# SMPS.net
KiCad netlist of a schematic drawn in Altium Designer
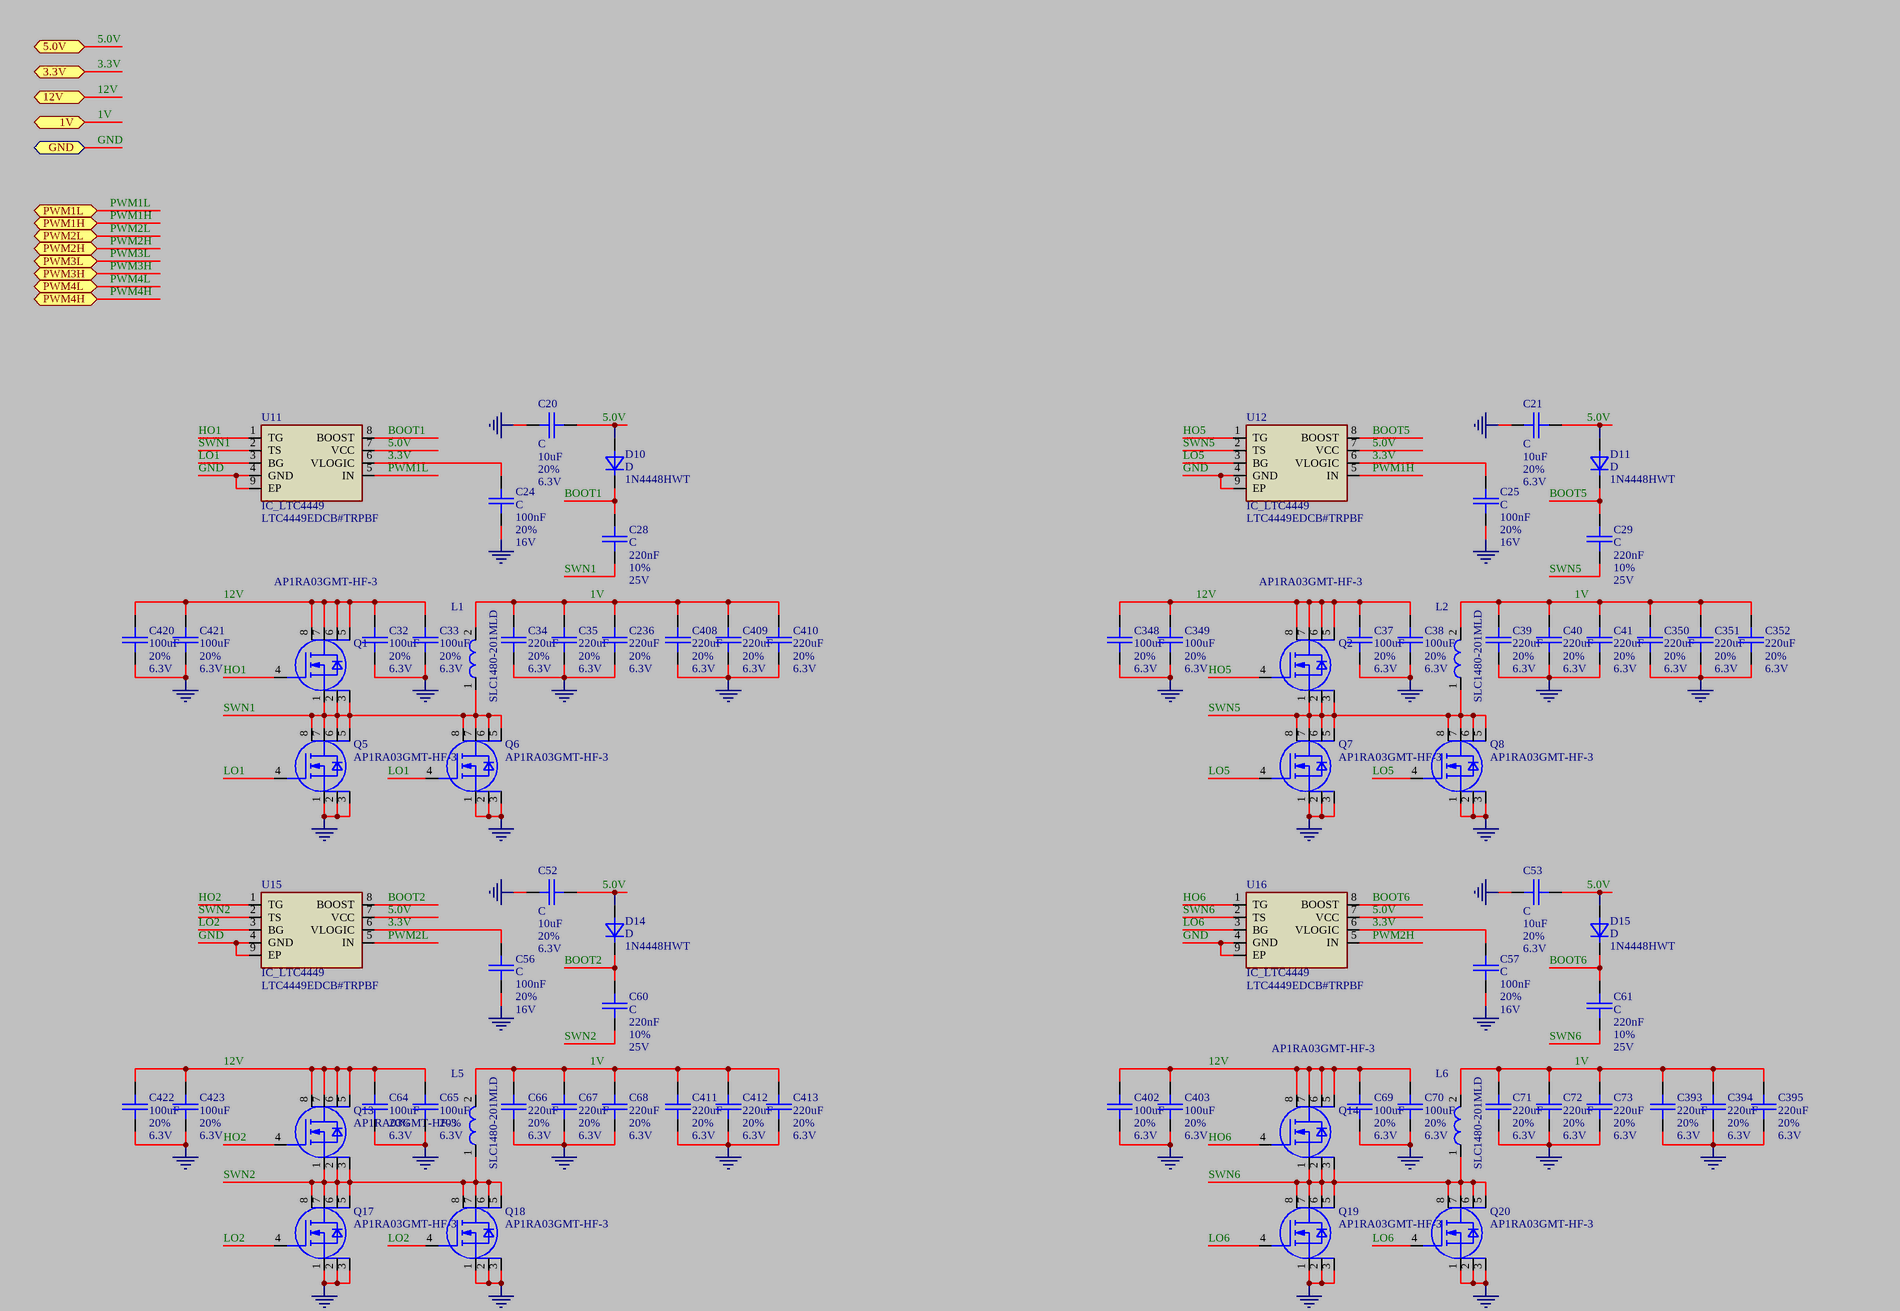
[diagram p0: SMPS.SchDoc, top left]
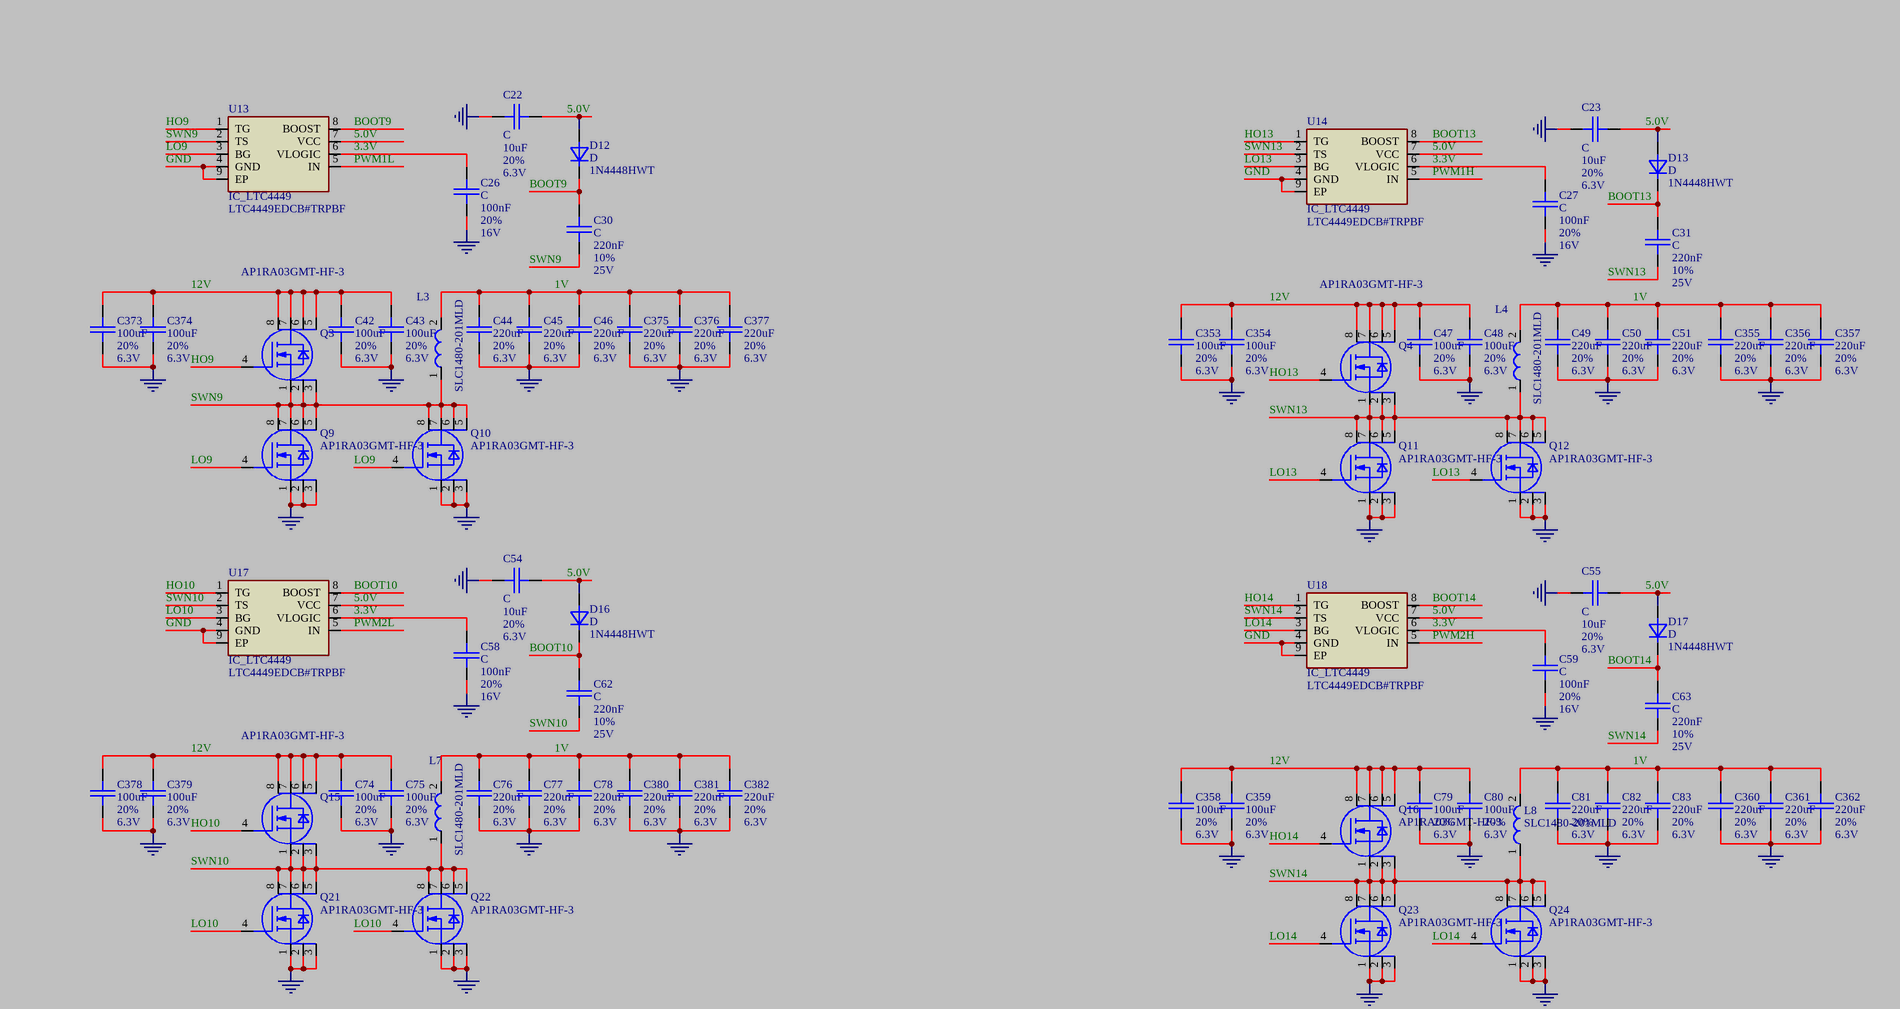
[diagram p1: SMPS.SchDoc, top right]
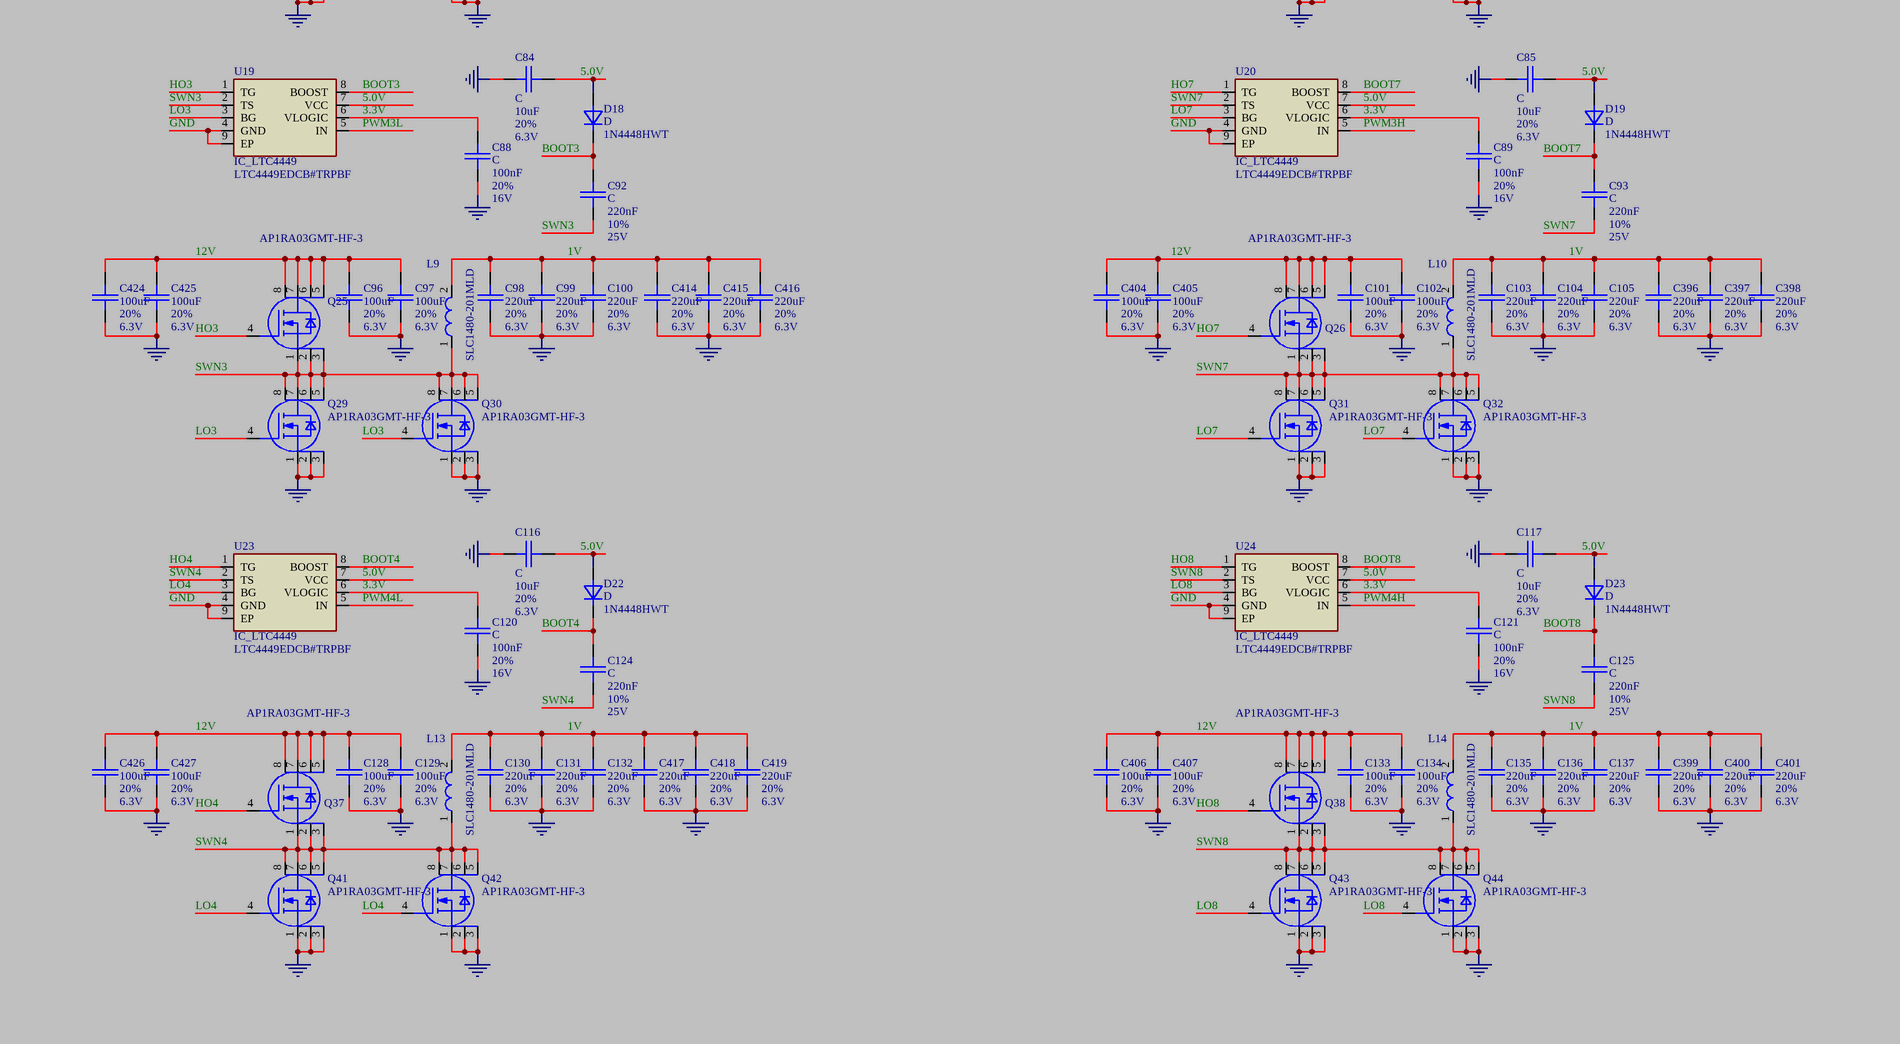
[diagram p2: SMPS.SchDoc, bottom left]
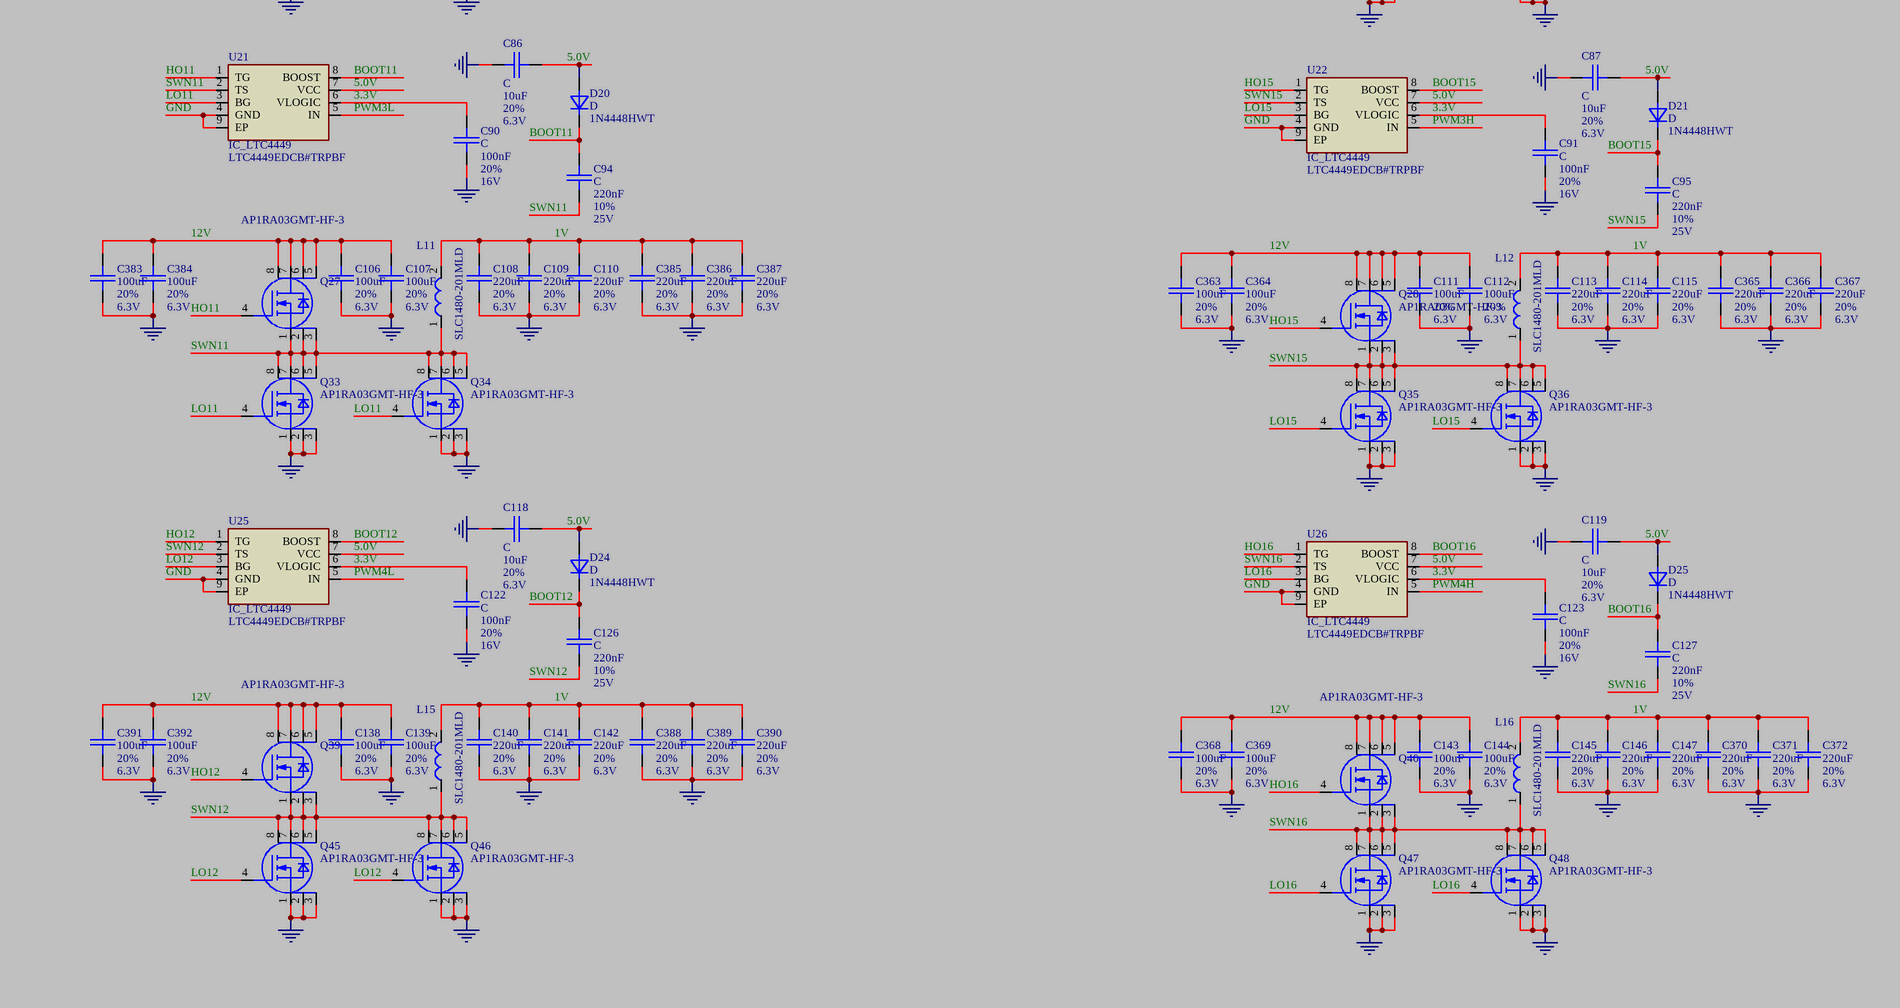
[diagram p3: SMPS.SchDoc, bottom right]

(export (version "E")
  (design (tool "Eeschema 10.0.6"))
  (components
    (comp (ref "C20")
      (value "C")
      (footprint "SMD_0603_CAPC1608X95N")
      (fields
        (field (name "DB_PART_NUMBER") "CAP000043646")
        (field (name "DB_VALUE") "10uF")
        (field (name "DB_TOLERANCE") "20%")
        (field (name "DB_VOLTAGE") "6.3V")
        (field (name "DB_MANUFACTURER_PART") "KEMET    C0603C106M9PAC")
      )
      (libsource (lib "Database_Libs1") (part "C"))
    )
    (comp (ref "C21")
      (value "C")
      (footprint "SMD_0603_CAPC1608X95N")
      (fields
        (field (name "DB_PART_NUMBER") "CAP000043646")
        (field (name "DB_VALUE") "10uF")
        (field (name "DB_TOLERANCE") "20%")
        (field (name "DB_VOLTAGE") "6.3V")
        (field (name "DB_MANUFACTURER_PART") "KEMET    C0603C106M9PAC")
      )
      (libsource (lib "Database_Libs1") (part "C"))
    )
    (comp (ref "C22")
      (value "C")
      (footprint "SMD_0603_CAPC1608X95N")
      (fields
        (field (name "DB_PART_NUMBER") "CAP000043646")
        (field (name "DB_VALUE") "10uF")
        (field (name "DB_TOLERANCE") "20%")
        (field (name "DB_VOLTAGE") "6.3V")
        (field (name "DB_MANUFACTURER_PART") "KEMET    C0603C106M9PAC")
      )
      (libsource (lib "Database_Libs1") (part "C"))
    )
    (comp (ref "C23")
      (value "C")
      (footprint "SMD_0603_CAPC1608X95N")
      (fields
        (field (name "DB_PART_NUMBER") "CAP000043646")
        (field (name "DB_VALUE") "10uF")
        (field (name "DB_TOLERANCE") "20%")
        (field (name "DB_VOLTAGE") "6.3V")
        (field (name "DB_MANUFACTURER_PART") "KEMET    C0603C106M9PAC")
      )
      (libsource (lib "Database_Libs1") (part "C"))
    )
    (comp (ref "C24")
      (value "C")
      (footprint "SMD_0402_CAPC1005X55N")
      (fields
        (field (name "DB_PART_NUMBER") "CAP000022751")
        (field (name "DB_VALUE") "100nF")
        (field (name "DB_TOLERANCE") "20%")
        (field (name "DB_VOLTAGE") "16V")
        (field (name "DB_MANUFACTURER_PART") "KEMET    C0402F104M4RAC")
      )
      (libsource (lib "Database_Libs1") (part "C"))
    )
    (comp (ref "C25")
      (value "C")
      (footprint "SMD_0402_CAPC1005X55N")
      (fields
        (field (name "DB_PART_NUMBER") "CAP000022751")
        (field (name "DB_VALUE") "100nF")
        (field (name "DB_TOLERANCE") "20%")
        (field (name "DB_VOLTAGE") "16V")
        (field (name "DB_MANUFACTURER_PART") "KEMET    C0402F104M4RAC")
      )
      (libsource (lib "Database_Libs1") (part "C"))
    )
    (comp (ref "C26")
      (value "C")
      (footprint "SMD_0402_CAPC1005X55N")
      (fields
        (field (name "DB_PART_NUMBER") "CAP000022751")
        (field (name "DB_VALUE") "100nF")
        (field (name "DB_TOLERANCE") "20%")
        (field (name "DB_VOLTAGE") "16V")
        (field (name "DB_MANUFACTURER_PART") "KEMET    C0402F104M4RAC")
      )
      (libsource (lib "Database_Libs1") (part "C"))
    )
    (comp (ref "C27")
      (value "C")
      (footprint "SMD_0402_CAPC1005X55N")
      (fields
        (field (name "DB_PART_NUMBER") "CAP000022751")
        (field (name "DB_VALUE") "100nF")
        (field (name "DB_TOLERANCE") "20%")
        (field (name "DB_VOLTAGE") "16V")
        (field (name "DB_MANUFACTURER_PART") "KEMET    C0402F104M4RAC")
      )
      (libsource (lib "Database_Libs1") (part "C"))
    )
    (comp (ref "C28")
      (value "C")
      (footprint "SMD_0603_CAPC1608X95N")
      (fields
        (field (name "DB_PART_NUMBER") "CAP000022968")
        (field (name "DB_VALUE") "220nF")
        (field (name "DB_TOLERANCE") "10%")
        (field (name "DB_VOLTAGE") "25V")
        (field (name "DB_MANUFACTURER_PART") "KEMET    C0603F224K3RAC")
      )
      (libsource (lib "Database_Libs1") (part "C"))
    )
    (comp (ref "C29")
      (value "C")
      (footprint "SMD_0603_CAPC1608X95N")
      (fields
        (field (name "DB_PART_NUMBER") "CAP000022968")
        (field (name "DB_VALUE") "220nF")
        (field (name "DB_TOLERANCE") "10%")
        (field (name "DB_VOLTAGE") "25V")
        (field (name "DB_MANUFACTURER_PART") "KEMET    C0603F224K3RAC")
      )
      (libsource (lib "Database_Libs1") (part "C"))
    )
    (comp (ref "C30")
      (value "C")
      (footprint "SMD_0603_CAPC1608X95N")
      (fields
        (field (name "DB_PART_NUMBER") "CAP000022968")
        (field (name "DB_VALUE") "220nF")
        (field (name "DB_TOLERANCE") "10%")
        (field (name "DB_VOLTAGE") "25V")
        (field (name "DB_MANUFACTURER_PART") "KEMET    C0603F224K3RAC")
      )
      (libsource (lib "Database_Libs1") (part "C"))
    )
    (comp (ref "C31")
      (value "C")
      (footprint "SMD_0603_CAPC1608X95N")
      (fields
        (field (name "DB_PART_NUMBER") "CAP000022968")
        (field (name "DB_VALUE") "220nF")
        (field (name "DB_TOLERANCE") "10%")
        (field (name "DB_VOLTAGE") "25V")
        (field (name "DB_MANUFACTURER_PART") "KEMET    C0603F224K3RAC")
      )
      (libsource (lib "Database_Libs1") (part "C"))
    )
    (comp (ref "C32")
      (value "C")
      (footprint "SMD_1210_CAPC3225X270N")
      (fields
        (field (name "DB_PART_NUMBER") "CAP000043701")
        (field (name "DB_VALUE") "100uF")
        (field (name "DB_TOLERANCE") "20%")
        (field (name "DB_VOLTAGE") "6.3V")
        (field (name "DB_MANUFACTURER_PART") "KEMET    C1210C107M9PAC")
      )
      (libsource (lib "Database_Libs1") (part "C"))
    )
    (comp (ref "C33")
      (value "C")
      (footprint "SMD_1210_CAPC3225X270N")
      (fields
        (field (name "DB_PART_NUMBER") "CAP000043701")
        (field (name "DB_VALUE") "100uF")
        (field (name "DB_TOLERANCE") "20%")
        (field (name "DB_VOLTAGE") "6.3V")
        (field (name "DB_MANUFACTURER_PART") "KEMET    C1210C107M9PAC")
      )
      (libsource (lib "Database_Libs1") (part "C"))
    )
    (comp (ref "C34")
      (value "C")
      (footprint "SMD_1210_CAPC3225X279N")
      (fields
        (field (name "DB_PART_NUMBER") "CAP000047355")
        (field (name "DB_VALUE") "220uF")
        (field (name "DB_TOLERANCE") "20%")
        (field (name "DB_VOLTAGE") "6.3V")
        (field (name "DB_MANUFACTURER_PART") "SAMSUNG    CL32A227MQVNNNE")
        (field (name "DB_APPROVED_BY") "VSN")
      )
      (libsource (lib "Database_Libs1") (part "C"))
    )
    (comp (ref "C35")
      (value "C")
      (footprint "SMD_1210_CAPC3225X279N")
      (fields
        (field (name "DB_PART_NUMBER") "CAP000047355")
        (field (name "DB_VALUE") "220uF")
        (field (name "DB_TOLERANCE") "20%")
        (field (name "DB_VOLTAGE") "6.3V")
        (field (name "DB_MANUFACTURER_PART") "SAMSUNG    CL32A227MQVNNNE")
        (field (name "DB_APPROVED_BY") "VSN")
      )
      (libsource (lib "Database_Libs1") (part "C"))
    )
    (comp (ref "C37")
      (value "C")
      (footprint "SMD_1210_CAPC3225X270N")
      (fields
        (field (name "DB_PART_NUMBER") "CAP000043701")
        (field (name "DB_VALUE") "100uF")
        (field (name "DB_TOLERANCE") "20%")
        (field (name "DB_VOLTAGE") "6.3V")
        (field (name "DB_MANUFACTURER_PART") "KEMET    C1210C107M9PAC")
      )
      (libsource (lib "Database_Libs1") (part "C"))
    )
    (comp (ref "C38")
      (value "C")
      (footprint "SMD_1210_CAPC3225X270N")
      (fields
        (field (name "DB_PART_NUMBER") "CAP000043701")
        (field (name "DB_VALUE") "100uF")
        (field (name "DB_TOLERANCE") "20%")
        (field (name "DB_VOLTAGE") "6.3V")
        (field (name "DB_MANUFACTURER_PART") "KEMET    C1210C107M9PAC")
      )
      (libsource (lib "Database_Libs1") (part "C"))
    )
    (comp (ref "C39")
      (value "C")
      (footprint "SMD_1210_CAPC3225X279N")
      (fields
        (field (name "DB_PART_NUMBER") "CAP000047355")
        (field (name "DB_VALUE") "220uF")
        (field (name "DB_TOLERANCE") "20%")
        (field (name "DB_VOLTAGE") "6.3V")
        (field (name "DB_MANUFACTURER_PART") "SAMSUNG    CL32A227MQVNNNE")
        (field (name "DB_APPROVED_BY") "VSN")
      )
      (libsource (lib "Database_Libs1") (part "C"))
    )
    (comp (ref "C40")
      (value "C")
      (footprint "SMD_1210_CAPC3225X279N")
      (fields
        (field (name "DB_PART_NUMBER") "CAP000047355")
        (field (name "DB_VALUE") "220uF")
        (field (name "DB_TOLERANCE") "20%")
        (field (name "DB_VOLTAGE") "6.3V")
        (field (name "DB_MANUFACTURER_PART") "SAMSUNG    CL32A227MQVNNNE")
        (field (name "DB_APPROVED_BY") "VSN")
      )
      (libsource (lib "Database_Libs1") (part "C"))
    )
    (comp (ref "C41")
      (value "C")
      (footprint "SMD_1210_CAPC3225X279N")
      (fields
        (field (name "DB_PART_NUMBER") "CAP000047355")
        (field (name "DB_VALUE") "220uF")
        (field (name "DB_TOLERANCE") "20%")
        (field (name "DB_VOLTAGE") "6.3V")
        (field (name "DB_MANUFACTURER_PART") "SAMSUNG    CL32A227MQVNNNE")
        (field (name "DB_APPROVED_BY") "VSN")
      )
      (libsource (lib "Database_Libs1") (part "C"))
    )
    (comp (ref "C42")
      (value "C")
      (footprint "SMD_1210_CAPC3225X270N")
      (fields
        (field (name "DB_PART_NUMBER") "CAP000043701")
        (field (name "DB_VALUE") "100uF")
        (field (name "DB_TOLERANCE") "20%")
        (field (name "DB_VOLTAGE") "6.3V")
        (field (name "DB_MANUFACTURER_PART") "KEMET    C1210C107M9PAC")
      )
      (libsource (lib "Database_Libs1") (part "C"))
    )
    (comp (ref "C43")
      (value "C")
      (footprint "SMD_1210_CAPC3225X270N")
      (fields
        (field (name "DB_PART_NUMBER") "CAP000043701")
        (field (name "DB_VALUE") "100uF")
        (field (name "DB_TOLERANCE") "20%")
        (field (name "DB_VOLTAGE") "6.3V")
        (field (name "DB_MANUFACTURER_PART") "KEMET    C1210C107M9PAC")
      )
      (libsource (lib "Database_Libs1") (part "C"))
    )
    (comp (ref "C44")
      (value "C")
      (footprint "SMD_1210_CAPC3225X279N")
      (fields
        (field (name "DB_PART_NUMBER") "CAP000047355")
        (field (name "DB_VALUE") "220uF")
        (field (name "DB_TOLERANCE") "20%")
        (field (name "DB_VOLTAGE") "6.3V")
        (field (name "DB_MANUFACTURER_PART") "SAMSUNG    CL32A227MQVNNNE")
        (field (name "DB_APPROVED_BY") "VSN")
      )
      (libsource (lib "Database_Libs1") (part "C"))
    )
    (comp (ref "C45")
      (value "C")
      (footprint "SMD_1210_CAPC3225X279N")
      (fields
        (field (name "DB_PART_NUMBER") "CAP000047355")
        (field (name "DB_VALUE") "220uF")
        (field (name "DB_TOLERANCE") "20%")
        (field (name "DB_VOLTAGE") "6.3V")
        (field (name "DB_MANUFACTURER_PART") "SAMSUNG    CL32A227MQVNNNE")
        (field (name "DB_APPROVED_BY") "VSN")
      )
      (libsource (lib "Database_Libs1") (part "C"))
    )
    (comp (ref "C46")
      (value "C")
      (footprint "SMD_1210_CAPC3225X279N")
      (fields
        (field (name "DB_PART_NUMBER") "CAP000047355")
        (field (name "DB_VALUE") "220uF")
        (field (name "DB_TOLERANCE") "20%")
        (field (name "DB_VOLTAGE") "6.3V")
        (field (name "DB_MANUFACTURER_PART") "SAMSUNG    CL32A227MQVNNNE")
        (field (name "DB_APPROVED_BY") "VSN")
      )
      (libsource (lib "Database_Libs1") (part "C"))
    )
    (comp (ref "C47")
      (value "C")
      (footprint "SMD_1210_CAPC3225X270N")
      (fields
        (field (name "DB_PART_NUMBER") "CAP000043701")
        (field (name "DB_VALUE") "100uF")
        (field (name "DB_TOLERANCE") "20%")
        (field (name "DB_VOLTAGE") "6.3V")
        (field (name "DB_MANUFACTURER_PART") "KEMET    C1210C107M9PAC")
      )
      (libsource (lib "Database_Libs1") (part "C"))
    )
    (comp (ref "C48")
      (value "C")
      (footprint "SMD_1210_CAPC3225X270N")
      (fields
        (field (name "DB_PART_NUMBER") "CAP000043701")
        (field (name "DB_VALUE") "100uF")
        (field (name "DB_TOLERANCE") "20%")
        (field (name "DB_VOLTAGE") "6.3V")
        (field (name "DB_MANUFACTURER_PART") "KEMET    C1210C107M9PAC")
      )
      (libsource (lib "Database_Libs1") (part "C"))
    )
    (comp (ref "C49")
      (value "C")
      (footprint "SMD_1210_CAPC3225X279N")
      (fields
        (field (name "DB_PART_NUMBER") "CAP000047355")
        (field (name "DB_VALUE") "220uF")
        (field (name "DB_TOLERANCE") "20%")
        (field (name "DB_VOLTAGE") "6.3V")
        (field (name "DB_MANUFACTURER_PART") "SAMSUNG    CL32A227MQVNNNE")
        (field (name "DB_APPROVED_BY") "VSN")
      )
      (libsource (lib "Database_Libs1") (part "C"))
    )
    (comp (ref "C50")
      (value "C")
      (footprint "SMD_1210_CAPC3225X279N")
      (fields
        (field (name "DB_PART_NUMBER") "CAP000047355")
        (field (name "DB_VALUE") "220uF")
        (field (name "DB_TOLERANCE") "20%")
        (field (name "DB_VOLTAGE") "6.3V")
        (field (name "DB_MANUFACTURER_PART") "SAMSUNG    CL32A227MQVNNNE")
        (field (name "DB_APPROVED_BY") "VSN")
      )
      (libsource (lib "Database_Libs1") (part "C"))
    )
    (comp (ref "C51")
      (value "C")
      (footprint "SMD_1210_CAPC3225X279N")
      (fields
        (field (name "DB_PART_NUMBER") "CAP000047355")
        (field (name "DB_VALUE") "220uF")
        (field (name "DB_TOLERANCE") "20%")
        (field (name "DB_VOLTAGE") "6.3V")
        (field (name "DB_MANUFACTURER_PART") "SAMSUNG    CL32A227MQVNNNE")
        (field (name "DB_APPROVED_BY") "VSN")
      )
      (libsource (lib "Database_Libs1") (part "C"))
    )
    (comp (ref "C52")
      (value "C")
      (footprint "SMD_0603_CAPC1608X95N")
      (fields
        (field (name "DB_PART_NUMBER") "CAP000043646")
        (field (name "DB_VALUE") "10uF")
        (field (name "DB_TOLERANCE") "20%")
        (field (name "DB_VOLTAGE") "6.3V")
        (field (name "DB_MANUFACTURER_PART") "KEMET    C0603C106M9PAC")
      )
      (libsource (lib "Database_Libs1") (part "C"))
    )
    (comp (ref "C53")
      (value "C")
      (footprint "SMD_0603_CAPC1608X95N")
      (fields
        (field (name "DB_PART_NUMBER") "CAP000043646")
        (field (name "DB_VALUE") "10uF")
        (field (name "DB_TOLERANCE") "20%")
        (field (name "DB_VOLTAGE") "6.3V")
        (field (name "DB_MANUFACTURER_PART") "KEMET    C0603C106M9PAC")
      )
      (libsource (lib "Database_Libs1") (part "C"))
    )
    (comp (ref "C54")
      (value "C")
      (footprint "SMD_0603_CAPC1608X95N")
      (fields
        (field (name "DB_PART_NUMBER") "CAP000043646")
        (field (name "DB_VALUE") "10uF")
        (field (name "DB_TOLERANCE") "20%")
        (field (name "DB_VOLTAGE") "6.3V")
        (field (name "DB_MANUFACTURER_PART") "KEMET    C0603C106M9PAC")
      )
      (libsource (lib "Database_Libs1") (part "C"))
    )
    (comp (ref "C55")
      (value "C")
      (footprint "SMD_0603_CAPC1608X95N")
      (fields
        (field (name "DB_PART_NUMBER") "CAP000043646")
        (field (name "DB_VALUE") "10uF")
        (field (name "DB_TOLERANCE") "20%")
        (field (name "DB_VOLTAGE") "6.3V")
        (field (name "DB_MANUFACTURER_PART") "KEMET    C0603C106M9PAC")
      )
      (libsource (lib "Database_Libs1") (part "C"))
    )
    (comp (ref "C56")
      (value "C")
      (footprint "SMD_0402_CAPC1005X55N")
      (fields
        (field (name "DB_PART_NUMBER") "CAP000022751")
        (field (name "DB_VALUE") "100nF")
        (field (name "DB_TOLERANCE") "20%")
        (field (name "DB_VOLTAGE") "16V")
        (field (name "DB_MANUFACTURER_PART") "KEMET    C0402F104M4RAC")
      )
      (libsource (lib "Database_Libs1") (part "C"))
    )
    (comp (ref "C57")
      (value "C")
      (footprint "SMD_0402_CAPC1005X55N")
      (fields
        (field (name "DB_PART_NUMBER") "CAP000022751")
        (field (name "DB_VALUE") "100nF")
        (field (name "DB_TOLERANCE") "20%")
        (field (name "DB_VOLTAGE") "16V")
        (field (name "DB_MANUFACTURER_PART") "KEMET    C0402F104M4RAC")
      )
      (libsource (lib "Database_Libs1") (part "C"))
    )
    (comp (ref "C58")
      (value "C")
      (footprint "SMD_0402_CAPC1005X55N")
      (fields
        (field (name "DB_PART_NUMBER") "CAP000022751")
        (field (name "DB_VALUE") "100nF")
        (field (name "DB_TOLERANCE") "20%")
        (field (name "DB_VOLTAGE") "16V")
        (field (name "DB_MANUFACTURER_PART") "KEMET    C0402F104M4RAC")
      )
      (libsource (lib "Database_Libs1") (part "C"))
    )
    (comp (ref "C59")
      (value "C")
      (footprint "SMD_0402_CAPC1005X55N")
      (fields
        (field (name "DB_PART_NUMBER") "CAP000022751")
        (field (name "DB_VALUE") "100nF")
        (field (name "DB_TOLERANCE") "20%")
        (field (name "DB_VOLTAGE") "16V")
        (field (name "DB_MANUFACTURER_PART") "KEMET    C0402F104M4RAC")
      )
      (libsource (lib "Database_Libs1") (part "C"))
    )
    (comp (ref "C60")
      (value "C")
      (footprint "SMD_0603_CAPC1608X95N")
      (fields
        (field (name "DB_PART_NUMBER") "CAP000022968")
        (field (name "DB_VALUE") "220nF")
        (field (name "DB_TOLERANCE") "10%")
        (field (name "DB_VOLTAGE") "25V")
        (field (name "DB_MANUFACTURER_PART") "KEMET    C0603F224K3RAC")
      )
      (libsource (lib "Database_Libs1") (part "C"))
    )
    (comp (ref "C61")
      (value "C")
      (footprint "SMD_0603_CAPC1608X95N")
      (fields
        (field (name "DB_PART_NUMBER") "CAP000022968")
        (field (name "DB_VALUE") "220nF")
        (field (name "DB_TOLERANCE") "10%")
        (field (name "DB_VOLTAGE") "25V")
        (field (name "DB_MANUFACTURER_PART") "KEMET    C0603F224K3RAC")
      )
      (libsource (lib "Database_Libs1") (part "C"))
    )
    (comp (ref "C62")
      (value "C")
      (footprint "SMD_0603_CAPC1608X95N")
      (fields
        (field (name "DB_PART_NUMBER") "CAP000022968")
        (field (name "DB_VALUE") "220nF")
        (field (name "DB_TOLERANCE") "10%")
        (field (name "DB_VOLTAGE") "25V")
        (field (name "DB_MANUFACTURER_PART") "KEMET    C0603F224K3RAC")
      )
      (libsource (lib "Database_Libs1") (part "C"))
    )
    (comp (ref "C63")
      (value "C")
      (footprint "SMD_0603_CAPC1608X95N")
      (fields
        (field (name "DB_PART_NUMBER") "CAP000022968")
        (field (name "DB_VALUE") "220nF")
        (field (name "DB_TOLERANCE") "10%")
        (field (name "DB_VOLTAGE") "25V")
        (field (name "DB_MANUFACTURER_PART") "KEMET    C0603F224K3RAC")
      )
      (libsource (lib "Database_Libs1") (part "C"))
    )
    (comp (ref "C64")
      (value "C")
      (footprint "SMD_1210_CAPC3225X270N")
      (fields
        (field (name "DB_PART_NUMBER") "CAP000043701")
        (field (name "DB_VALUE") "100uF")
        (field (name "DB_TOLERANCE") "20%")
        (field (name "DB_VOLTAGE") "6.3V")
        (field (name "DB_MANUFACTURER_PART") "KEMET    C1210C107M9PAC")
      )
      (libsource (lib "Database_Libs1") (part "C"))
    )
    (comp (ref "C65")
      (value "C")
      (footprint "SMD_1210_CAPC3225X270N")
      (fields
        (field (name "DB_PART_NUMBER") "CAP000043701")
        (field (name "DB_VALUE") "100uF")
        (field (name "DB_TOLERANCE") "20%")
        (field (name "DB_VOLTAGE") "6.3V")
        (field (name "DB_MANUFACTURER_PART") "KEMET    C1210C107M9PAC")
      )
      (libsource (lib "Database_Libs1") (part "C"))
    )
    (comp (ref "C66")
      (value "C")
      (footprint "SMD_1210_CAPC3225X279N")
      (fields
        (field (name "DB_PART_NUMBER") "CAP000047355")
        (field (name "DB_VALUE") "220uF")
        (field (name "DB_TOLERANCE") "20%")
        (field (name "DB_VOLTAGE") "6.3V")
        (field (name "DB_MANUFACTURER_PART") "SAMSUNG    CL32A227MQVNNNE")
        (field (name "DB_APPROVED_BY") "VSN")
      )
      (libsource (lib "Database_Libs1") (part "C"))
    )
    (comp (ref "C67")
      (value "C")
      (footprint "SMD_1210_CAPC3225X279N")
      (fields
        (field (name "DB_PART_NUMBER") "CAP000047355")
        (field (name "DB_VALUE") "220uF")
        (field (name "DB_TOLERANCE") "20%")
        (field (name "DB_VOLTAGE") "6.3V")
        (field (name "DB_MANUFACTURER_PART") "SAMSUNG    CL32A227MQVNNNE")
        (field (name "DB_APPROVED_BY") "VSN")
      )
      (libsource (lib "Database_Libs1") (part "C"))
    )
    (comp (ref "C68")
      (value "C")
      (footprint "SMD_1210_CAPC3225X279N")
      (fields
        (field (name "DB_PART_NUMBER") "CAP000047355")
        (field (name "DB_VALUE") "220uF")
        (field (name "DB_TOLERANCE") "20%")
        (field (name "DB_VOLTAGE") "6.3V")
        (field (name "DB_MANUFACTURER_PART") "SAMSUNG    CL32A227MQVNNNE")
        (field (name "DB_APPROVED_BY") "VSN")
      )
      (libsource (lib "Database_Libs1") (part "C"))
    )
    (comp (ref "C69")
      (value "C")
      (footprint "SMD_1210_CAPC3225X270N")
      (fields
        (field (name "DB_PART_NUMBER") "CAP000043701")
        (field (name "DB_VALUE") "100uF")
        (field (name "DB_TOLERANCE") "20%")
        (field (name "DB_VOLTAGE") "6.3V")
        (field (name "DB_MANUFACTURER_PART") "KEMET    C1210C107M9PAC")
      )
      (libsource (lib "Database_Libs1") (part "C"))
    )
    (comp (ref "C70")
      (value "C")
      (footprint "SMD_1210_CAPC3225X270N")
      (fields
        (field (name "DB_PART_NUMBER") "CAP000043701")
        (field (name "DB_VALUE") "100uF")
        (field (name "DB_TOLERANCE") "20%")
        (field (name "DB_VOLTAGE") "6.3V")
        (field (name "DB_MANUFACTURER_PART") "KEMET    C1210C107M9PAC")
      )
      (libsource (lib "Database_Libs1") (part "C"))
    )
    (comp (ref "C71")
      (value "C")
      (footprint "SMD_1210_CAPC3225X279N")
      (fields
        (field (name "DB_PART_NUMBER") "CAP000047355")
        (field (name "DB_VALUE") "220uF")
        (field (name "DB_TOLERANCE") "20%")
        (field (name "DB_VOLTAGE") "6.3V")
        (field (name "DB_MANUFACTURER_PART") "SAMSUNG    CL32A227MQVNNNE")
        (field (name "DB_APPROVED_BY") "VSN")
      )
      (libsource (lib "Database_Libs1") (part "C"))
    )
    (comp (ref "C72")
      (value "C")
      (footprint "SMD_1210_CAPC3225X279N")
      (fields
        (field (name "DB_PART_NUMBER") "CAP000047355")
        (field (name "DB_VALUE") "220uF")
        (field (name "DB_TOLERANCE") "20%")
        (field (name "DB_VOLTAGE") "6.3V")
        (field (name "DB_MANUFACTURER_PART") "SAMSUNG    CL32A227MQVNNNE")
        (field (name "DB_APPROVED_BY") "VSN")
      )
      (libsource (lib "Database_Libs1") (part "C"))
    )
    (comp (ref "C73")
      (value "C")
      (footprint "SMD_1210_CAPC3225X279N")
      (fields
        (field (name "DB_PART_NUMBER") "CAP000047355")
        (field (name "DB_VALUE") "220uF")
        (field (name "DB_TOLERANCE") "20%")
        (field (name "DB_VOLTAGE") "6.3V")
        (field (name "DB_MANUFACTURER_PART") "SAMSUNG    CL32A227MQVNNNE")
        (field (name "DB_APPROVED_BY") "VSN")
      )
      (libsource (lib "Database_Libs1") (part "C"))
    )
    (comp (ref "C74")
      (value "C")
      (footprint "SMD_1210_CAPC3225X270N")
      (fields
        (field (name "DB_PART_NUMBER") "CAP000043701")
        (field (name "DB_VALUE") "100uF")
        (field (name "DB_TOLERANCE") "20%")
        (field (name "DB_VOLTAGE") "6.3V")
        (field (name "DB_MANUFACTURER_PART") "KEMET    C1210C107M9PAC")
      )
      (libsource (lib "Database_Libs1") (part "C"))
    )
    (comp (ref "C75")
      (value "C")
      (footprint "SMD_1210_CAPC3225X270N")
      (fields
        (field (name "DB_PART_NUMBER") "CAP000043701")
        (field (name "DB_VALUE") "100uF")
        (field (name "DB_TOLERANCE") "20%")
        (field (name "DB_VOLTAGE") "6.3V")
        (field (name "DB_MANUFACTURER_PART") "KEMET    C1210C107M9PAC")
      )
      (libsource (lib "Database_Libs1") (part "C"))
    )
    (comp (ref "C76")
      (value "C")
      (footprint "SMD_1210_CAPC3225X279N")
      (fields
        (field (name "DB_PART_NUMBER") "CAP000047355")
        (field (name "DB_VALUE") "220uF")
        (field (name "DB_TOLERANCE") "20%")
        (field (name "DB_VOLTAGE") "6.3V")
        (field (name "DB_MANUFACTURER_PART") "SAMSUNG    CL32A227MQVNNNE")
        (field (name "DB_APPROVED_BY") "VSN")
      )
      (libsource (lib "Database_Libs1") (part "C"))
    )
    (comp (ref "C77")
      (value "C")
      (footprint "SMD_1210_CAPC3225X279N")
      (fields
        (field (name "DB_PART_NUMBER") "CAP000047355")
        (field (name "DB_VALUE") "220uF")
        (field (name "DB_TOLERANCE") "20%")
        (field (name "DB_VOLTAGE") "6.3V")
        (field (name "DB_MANUFACTURER_PART") "SAMSUNG    CL32A227MQVNNNE")
        (field (name "DB_APPROVED_BY") "VSN")
      )
      (libsource (lib "Database_Libs1") (part "C"))
    )
    (comp (ref "C78")
      (value "C")
      (footprint "SMD_1210_CAPC3225X279N")
      (fields
        (field (name "DB_PART_NUMBER") "CAP000047355")
        (field (name "DB_VALUE") "220uF")
        (field (name "DB_TOLERANCE") "20%")
        (field (name "DB_VOLTAGE") "6.3V")
        (field (name "DB_MANUFACTURER_PART") "SAMSUNG    CL32A227MQVNNNE")
        (field (name "DB_APPROVED_BY") "VSN")
      )
      (libsource (lib "Database_Libs1") (part "C"))
    )
    (comp (ref "C79")
      (value "C")
      (footprint "SMD_1210_CAPC3225X270N")
      (fields
        (field (name "DB_PART_NUMBER") "CAP000043701")
        (field (name "DB_VALUE") "100uF")
        (field (name "DB_TOLERANCE") "20%")
        (field (name "DB_VOLTAGE") "6.3V")
        (field (name "DB_MANUFACTURER_PART") "KEMET    C1210C107M9PAC")
      )
      (libsource (lib "Database_Libs1") (part "C"))
    )
    (comp (ref "C80")
      (value "C")
      (footprint "SMD_1210_CAPC3225X270N")
      (fields
        (field (name "DB_PART_NUMBER") "CAP000043701")
        (field (name "DB_VALUE") "100uF")
        (field (name "DB_TOLERANCE") "20%")
        (field (name "DB_VOLTAGE") "6.3V")
        (field (name "DB_MANUFACTURER_PART") "KEMET    C1210C107M9PAC")
      )
      (libsource (lib "Database_Libs1") (part "C"))
    )
    (comp (ref "C81")
      (value "C")
      (footprint "SMD_1210_CAPC3225X279N")
      (fields
        (field (name "DB_PART_NUMBER") "CAP000047355")
        (field (name "DB_VALUE") "220uF")
        (field (name "DB_TOLERANCE") "20%")
        (field (name "DB_VOLTAGE") "6.3V")
        (field (name "DB_MANUFACTURER_PART") "SAMSUNG    CL32A227MQVNNNE")
        (field (name "DB_APPROVED_BY") "VSN")
      )
      (libsource (lib "Database_Libs1") (part "C"))
    )
    (comp (ref "C82")
      (value "C")
      (footprint "SMD_1210_CAPC3225X279N")
      (fields
        (field (name "DB_PART_NUMBER") "CAP000047355")
        (field (name "DB_VALUE") "220uF")
        (field (name "DB_TOLERANCE") "20%")
        (field (name "DB_VOLTAGE") "6.3V")
        (field (name "DB_MANUFACTURER_PART") "SAMSUNG    CL32A227MQVNNNE")
        (field (name "DB_APPROVED_BY") "VSN")
      )
      (libsource (lib "Database_Libs1") (part "C"))
    )
    (comp (ref "C83")
      (value "C")
      (footprint "SMD_1210_CAPC3225X279N")
      (fields
        (field (name "DB_PART_NUMBER") "CAP000047355")
        (field (name "DB_VALUE") "220uF")
        (field (name "DB_TOLERANCE") "20%")
        (field (name "DB_VOLTAGE") "6.3V")
        (field (name "DB_MANUFACTURER_PART") "SAMSUNG    CL32A227MQVNNNE")
        (field (name "DB_APPROVED_BY") "VSN")
      )
      (libsource (lib "Database_Libs1") (part "C"))
    )
    (comp (ref "C84")
      (value "C")
      (footprint "SMD_0603_CAPC1608X95N")
      (fields
        (field (name "DB_PART_NUMBER") "CAP000043646")
        (field (name "DB_VALUE") "10uF")
        (field (name "DB_TOLERANCE") "20%")
        (field (name "DB_VOLTAGE") "6.3V")
        (field (name "DB_MANUFACTURER_PART") "KEMET    C0603C106M9PAC")
      )
      (libsource (lib "Database_Libs1") (part "C"))
    )
    (comp (ref "C85")
      (value "C")
      (footprint "SMD_0603_CAPC1608X95N")
      (fields
        (field (name "DB_PART_NUMBER") "CAP000043646")
        (field (name "DB_VALUE") "10uF")
        (field (name "DB_TOLERANCE") "20%")
        (field (name "DB_VOLTAGE") "6.3V")
        (field (name "DB_MANUFACTURER_PART") "KEMET    C0603C106M9PAC")
      )
      (libsource (lib "Database_Libs1") (part "C"))
    )
    (comp (ref "C86")
      (value "C")
      (footprint "SMD_0603_CAPC1608X95N")
      (fields
        (field (name "DB_PART_NUMBER") "CAP000043646")
        (field (name "DB_VALUE") "10uF")
        (field (name "DB_TOLERANCE") "20%")
        (field (name "DB_VOLTAGE") "6.3V")
        (field (name "DB_MANUFACTURER_PART") "KEMET    C0603C106M9PAC")
      )
      (libsource (lib "Database_Libs1") (part "C"))
    )
    (comp (ref "C87")
      (value "C")
      (footprint "SMD_0603_CAPC1608X95N")
      (fields
        (field (name "DB_PART_NUMBER") "CAP000043646")
        (field (name "DB_VALUE") "10uF")
        (field (name "DB_TOLERANCE") "20%")
        (field (name "DB_VOLTAGE") "6.3V")
        (field (name "DB_MANUFACTURER_PART") "KEMET    C0603C106M9PAC")
      )
      (libsource (lib "Database_Libs1") (part "C"))
    )
    (comp (ref "C88")
      (value "C")
      (footprint "SMD_0402_CAPC1005X55N")
      (fields
        (field (name "DB_PART_NUMBER") "CAP000022751")
        (field (name "DB_VALUE") "100nF")
        (field (name "DB_TOLERANCE") "20%")
        (field (name "DB_VOLTAGE") "16V")
        (field (name "DB_MANUFACTURER_PART") "KEMET    C0402F104M4RAC")
      )
      (libsource (lib "Database_Libs1") (part "C"))
    )
    (comp (ref "C89")
      (value "C")
      (footprint "SMD_0402_CAPC1005X55N")
      (fields
        (field (name "DB_PART_NUMBER") "CAP000022751")
        (field (name "DB_VALUE") "100nF")
        (field (name "DB_TOLERANCE") "20%")
        (field (name "DB_VOLTAGE") "16V")
        (field (name "DB_MANUFACTURER_PART") "KEMET    C0402F104M4RAC")
      )
      (libsource (lib "Database_Libs1") (part "C"))
    )
    (comp (ref "C90")
      (value "C")
      (footprint "SMD_0402_CAPC1005X55N")
      (fields
        (field (name "DB_PART_NUMBER") "CAP000022751")
        (field (name "DB_VALUE") "100nF")
        (field (name "DB_TOLERANCE") "20%")
        (field (name "DB_VOLTAGE") "16V")
        (field (name "DB_MANUFACTURER_PART") "KEMET    C0402F104M4RAC")
      )
      (libsource (lib "Database_Libs1") (part "C"))
    )
    (comp (ref "C91")
      (value "C")
      (footprint "SMD_0402_CAPC1005X55N")
      (fields
        (field (name "DB_PART_NUMBER") "CAP000022751")
        (field (name "DB_VALUE") "100nF")
        (field (name "DB_TOLERANCE") "20%")
        (field (name "DB_VOLTAGE") "16V")
        (field (name "DB_MANUFACTURER_PART") "KEMET    C0402F104M4RAC")
      )
      (libsource (lib "Database_Libs1") (part "C"))
    )
    (comp (ref "C92")
      (value "C")
      (footprint "SMD_0603_CAPC1608X95N")
      (fields
        (field (name "DB_PART_NUMBER") "CAP000022968")
        (field (name "DB_VALUE") "220nF")
        (field (name "DB_TOLERANCE") "10%")
        (field (name "DB_VOLTAGE") "25V")
        (field (name "DB_MANUFACTURER_PART") "KEMET    C0603F224K3RAC")
      )
      (libsource (lib "Database_Libs1") (part "C"))
    )
    (comp (ref "C93")
      (value "C")
      (footprint "SMD_0603_CAPC1608X95N")
      (fields
        (field (name "DB_PART_NUMBER") "CAP000022968")
        (field (name "DB_VALUE") "220nF")
        (field (name "DB_TOLERANCE") "10%")
        (field (name "DB_VOLTAGE") "25V")
        (field (name "DB_MANUFACTURER_PART") "KEMET    C0603F224K3RAC")
      )
      (libsource (lib "Database_Libs1") (part "C"))
    )
    (comp (ref "C94")
      (value "C")
      (footprint "SMD_0603_CAPC1608X95N")
      (fields
        (field (name "DB_PART_NUMBER") "CAP000022968")
        (field (name "DB_VALUE") "220nF")
        (field (name "DB_TOLERANCE") "10%")
        (field (name "DB_VOLTAGE") "25V")
        (field (name "DB_MANUFACTURER_PART") "KEMET    C0603F224K3RAC")
      )
      (libsource (lib "Database_Libs1") (part "C"))
    )
    (comp (ref "C95")
      (value "C")
      (footprint "SMD_0603_CAPC1608X95N")
      (fields
        (field (name "DB_PART_NUMBER") "CAP000022968")
        (field (name "DB_VALUE") "220nF")
        (field (name "DB_TOLERANCE") "10%")
        (field (name "DB_VOLTAGE") "25V")
        (field (name "DB_MANUFACTURER_PART") "KEMET    C0603F224K3RAC")
      )
      (libsource (lib "Database_Libs1") (part "C"))
    )
    (comp (ref "C96")
      (value "C")
      (footprint "SMD_1210_CAPC3225X270N")
      (fields
        (field (name "DB_PART_NUMBER") "CAP000043701")
        (field (name "DB_VALUE") "100uF")
        (field (name "DB_TOLERANCE") "20%")
        (field (name "DB_VOLTAGE") "6.3V")
        (field (name "DB_MANUFACTURER_PART") "KEMET    C1210C107M9PAC")
      )
      (libsource (lib "Database_Libs1") (part "C"))
    )
    (comp (ref "C97")
      (value "C")
      (footprint "SMD_1210_CAPC3225X270N")
      (fields
        (field (name "DB_PART_NUMBER") "CAP000043701")
        (field (name "DB_VALUE") "100uF")
        (field (name "DB_TOLERANCE") "20%")
        (field (name "DB_VOLTAGE") "6.3V")
        (field (name "DB_MANUFACTURER_PART") "KEMET    C1210C107M9PAC")
      )
      (libsource (lib "Database_Libs1") (part "C"))
    )
    (comp (ref "C98")
      (value "C")
      (footprint "SMD_1210_CAPC3225X279N")
      (fields
        (field (name "DB_PART_NUMBER") "CAP000047355")
        (field (name "DB_VALUE") "220uF")
        (field (name "DB_TOLERANCE") "20%")
        (field (name "DB_VOLTAGE") "6.3V")
        (field (name "DB_MANUFACTURER_PART") "SAMSUNG    CL32A227MQVNNNE")
        (field (name "DB_APPROVED_BY") "VSN")
      )
      (libsource (lib "Database_Libs1") (part "C"))
    )
    (comp (ref "C99")
      (value "C")
      (footprint "SMD_1210_CAPC3225X279N")
      (fields
        (field (name "DB_PART_NUMBER") "CAP000047355")
        (field (name "DB_VALUE") "220uF")
        (field (name "DB_TOLERANCE") "20%")
        (field (name "DB_VOLTAGE") "6.3V")
        (field (name "DB_MANUFACTURER_PART") "SAMSUNG    CL32A227MQVNNNE")
        (field (name "DB_APPROVED_BY") "VSN")
      )
      (libsource (lib "Database_Libs1") (part "C"))
    )
    (comp (ref "C100")
      (value "C")
      (footprint "SMD_1210_CAPC3225X279N")
      (fields
        (field (name "DB_PART_NUMBER") "CAP000047355")
        (field (name "DB_VALUE") "220uF")
        (field (name "DB_TOLERANCE") "20%")
        (field (name "DB_VOLTAGE") "6.3V")
        (field (name "DB_MANUFACTURER_PART") "SAMSUNG    CL32A227MQVNNNE")
        (field (name "DB_APPROVED_BY") "VSN")
      )
      (libsource (lib "Database_Libs1") (part "C"))
    )
    (comp (ref "C101")
      (value "C")
      (footprint "SMD_1210_CAPC3225X270N")
      (fields
        (field (name "DB_PART_NUMBER") "CAP000043701")
        (field (name "DB_VALUE") "100uF")
        (field (name "DB_TOLERANCE") "20%")
        (field (name "DB_VOLTAGE") "6.3V")
        (field (name "DB_MANUFACTURER_PART") "KEMET    C1210C107M9PAC")
      )
      (libsource (lib "Database_Libs1") (part "C"))
    )
    (comp (ref "C102")
      (value "C")
      (footprint "SMD_1210_CAPC3225X270N")
      (fields
        (field (name "DB_PART_NUMBER") "CAP000043701")
        (field (name "DB_VALUE") "100uF")
        (field (name "DB_TOLERANCE") "20%")
        (field (name "DB_VOLTAGE") "6.3V")
        (field (name "DB_MANUFACTURER_PART") "KEMET    C1210C107M9PAC")
      )
      (libsource (lib "Database_Libs1") (part "C"))
    )
    (comp (ref "C103")
      (value "C")
      (footprint "SMD_1210_CAPC3225X279N")
      (fields
        (field (name "DB_PART_NUMBER") "CAP000047355")
        (field (name "DB_VALUE") "220uF")
        (field (name "DB_TOLERANCE") "20%")
        (field (name "DB_VOLTAGE") "6.3V")
        (field (name "DB_MANUFACTURER_PART") "SAMSUNG    CL32A227MQVNNNE")
        (field (name "DB_APPROVED_BY") "VSN")
      )
      (libsource (lib "Database_Libs1") (part "C"))
    )
    (comp (ref "C104")
      (value "C")
      (footprint "SMD_1210_CAPC3225X279N")
      (fields
        (field (name "DB_PART_NUMBER") "CAP000047355")
        (field (name "DB_VALUE") "220uF")
        (field (name "DB_TOLERANCE") "20%")
        (field (name "DB_VOLTAGE") "6.3V")
        (field (name "DB_MANUFACTURER_PART") "SAMSUNG    CL32A227MQVNNNE")
        (field (name "DB_APPROVED_BY") "VSN")
      )
      (libsource (lib "Database_Libs1") (part "C"))
    )
    (comp (ref "C105")
      (value "C")
      (footprint "SMD_1210_CAPC3225X279N")
      (fields
        (field (name "DB_PART_NUMBER") "CAP000047355")
        (field (name "DB_VALUE") "220uF")
        (field (name "DB_TOLERANCE") "20%")
        (field (name "DB_VOLTAGE") "6.3V")
        (field (name "DB_MANUFACTURER_PART") "SAMSUNG    CL32A227MQVNNNE")
        (field (name "DB_APPROVED_BY") "VSN")
      )
      (libsource (lib "Database_Libs1") (part "C"))
    )
    (comp (ref "C106")
      (value "C")
      (footprint "SMD_1210_CAPC3225X270N")
      (fields
        (field (name "DB_PART_NUMBER") "CAP000043701")
        (field (name "DB_VALUE") "100uF")
        (field (name "DB_TOLERANCE") "20%")
        (field (name "DB_VOLTAGE") "6.3V")
        (field (name "DB_MANUFACTURER_PART") "KEMET    C1210C107M9PAC")
      )
      (libsource (lib "Database_Libs1") (part "C"))
    )
    (comp (ref "C107")
      (value "C")
      (footprint "SMD_1210_CAPC3225X270N")
      (fields
        (field (name "DB_PART_NUMBER") "CAP000043701")
        (field (name "DB_VALUE") "100uF")
        (field (name "DB_TOLERANCE") "20%")
        (field (name "DB_VOLTAGE") "6.3V")
        (field (name "DB_MANUFACTURER_PART") "KEMET    C1210C107M9PAC")
      )
      (libsource (lib "Database_Libs1") (part "C"))
    )
    (comp (ref "C108")
      (value "C")
      (footprint "SMD_1210_CAPC3225X279N")
      (fields
        (field (name "DB_PART_NUMBER") "CAP000047355")
        (field (name "DB_VALUE") "220uF")
        (field (name "DB_TOLERANCE") "20%")
        (field (name "DB_VOLTAGE") "6.3V")
        (field (name "DB_MANUFACTURER_PART") "SAMSUNG    CL32A227MQVNNNE")
        (field (name "DB_APPROVED_BY") "VSN")
      )
      (libsource (lib "Database_Libs1") (part "C"))
    )
    (comp (ref "C109")
      (value "C")
      (footprint "SMD_1210_CAPC3225X279N")
      (fields
        (field (name "DB_PART_NUMBER") "CAP000047355")
        (field (name "DB_VALUE") "220uF")
        (field (name "DB_TOLERANCE") "20%")
        (field (name "DB_VOLTAGE") "6.3V")
        (field (name "DB_MANUFACTURER_PART") "SAMSUNG    CL32A227MQVNNNE")
        (field (name "DB_APPROVED_BY") "VSN")
      )
      (libsource (lib "Database_Libs1") (part "C"))
    )
    (comp (ref "C110")
      (value "C")
      (footprint "SMD_1210_CAPC3225X279N")
      (fields
        (field (name "DB_PART_NUMBER") "CAP000047355")
        (field (name "DB_VALUE") "220uF")
        (field (name "DB_TOLERANCE") "20%")
        (field (name "DB_VOLTAGE") "6.3V")
        (field (name "DB_MANUFACTURER_PART") "SAMSUNG    CL32A227MQVNNNE")
        (field (name "DB_APPROVED_BY") "VSN")
      )
      (libsource (lib "Database_Libs1") (part "C"))
    )
    (comp (ref "C111")
      (value "C")
      (footprint "SMD_1210_CAPC3225X270N")
      (fields
        (field (name "DB_PART_NUMBER") "CAP000043701")
        (field (name "DB_VALUE") "100uF")
        (field (name "DB_TOLERANCE") "20%")
        (field (name "DB_VOLTAGE") "6.3V")
        (field (name "DB_MANUFACTURER_PART") "KEMET    C1210C107M9PAC")
      )
      (libsource (lib "Database_Libs1") (part "C"))
    )
    (comp (ref "C112")
      (value "C")
      (footprint "SMD_1210_CAPC3225X270N")
      (fields
        (field (name "DB_PART_NUMBER") "CAP000043701")
        (field (name "DB_VALUE") "100uF")
        (field (name "DB_TOLERANCE") "20%")
        (field (name "DB_VOLTAGE") "6.3V")
        (field (name "DB_MANUFACTURER_PART") "KEMET    C1210C107M9PAC")
      )
      (libsource (lib "Database_Libs1") (part "C"))
    )
    (comp (ref "C113")
      (value "C")
      (footprint "SMD_1210_CAPC3225X279N")
      (fields
        (field (name "DB_PART_NUMBER") "CAP000047355")
        (field (name "DB_VALUE") "220uF")
        (field (name "DB_TOLERANCE") "20%")
        (field (name "DB_VOLTAGE") "6.3V")
        (field (name "DB_MANUFACTURER_PART") "SAMSUNG    CL32A227MQVNNNE")
        (field (name "DB_APPROVED_BY") "VSN")
      )
      (libsource (lib "Database_Libs1") (part "C"))
    )
    (comp (ref "C114")
      (value "C")
      (footprint "SMD_1210_CAPC3225X279N")
      (fields
        (field (name "DB_PART_NUMBER") "CAP000047355")
        (field (name "DB_VALUE") "220uF")
        (field (name "DB_TOLERANCE") "20%")
        (field (name "DB_VOLTAGE") "6.3V")
        (field (name "DB_MANUFACTURER_PART") "SAMSUNG    CL32A227MQVNNNE")
        (field (name "DB_APPROVED_BY") "VSN")
      )
      (libsource (lib "Database_Libs1") (part "C"))
    )
    (comp (ref "C115")
      (value "C")
      (footprint "SMD_1210_CAPC3225X279N")
      (fields
        (field (name "DB_PART_NUMBER") "CAP000047355")
        (field (name "DB_VALUE") "220uF")
        (field (name "DB_TOLERANCE") "20%")
        (field (name "DB_VOLTAGE") "6.3V")
        (field (name "DB_MANUFACTURER_PART") "SAMSUNG    CL32A227MQVNNNE")
        (field (name "DB_APPROVED_BY") "VSN")
      )
      (libsource (lib "Database_Libs1") (part "C"))
    )
    (comp (ref "C116")
      (value "C")
      (footprint "SMD_0603_CAPC1608X95N")
      (fields
        (field (name "DB_PART_NUMBER") "CAP000043646")
        (field (name "DB_VALUE") "10uF")
        (field (name "DB_TOLERANCE") "20%")
        (field (name "DB_VOLTAGE") "6.3V")
        (field (name "DB_MANUFACTURER_PART") "KEMET    C0603C106M9PAC")
      )
      (libsource (lib "Database_Libs1") (part "C"))
    )
    (comp (ref "C117")
      (value "C")
      (footprint "SMD_0603_CAPC1608X95N")
      (fields
        (field (name "DB_PART_NUMBER") "CAP000043646")
        (field (name "DB_VALUE") "10uF")
        (field (name "DB_TOLERANCE") "20%")
        (field (name "DB_VOLTAGE") "6.3V")
        (field (name "DB_MANUFACTURER_PART") "KEMET    C0603C106M9PAC")
      )
      (libsource (lib "Database_Libs1") (part "C"))
    )
    (comp (ref "C118")
      (value "C")
      (footprint "SMD_0603_CAPC1608X95N")
      (fields
        (field (name "DB_PART_NUMBER") "CAP000043646")
        (field (name "DB_VALUE") "10uF")
        (field (name "DB_TOLERANCE") "20%")
        (field (name "DB_VOLTAGE") "6.3V")
        (field (name "DB_MANUFACTURER_PART") "KEMET    C0603C106M9PAC")
      )
      (libsource (lib "Database_Libs1") (part "C"))
    )
    (comp (ref "C119")
      (value "C")
      (footprint "SMD_0603_CAPC1608X95N")
      (fields
        (field (name "DB_PART_NUMBER") "CAP000043646")
        (field (name "DB_VALUE") "10uF")
        (field (name "DB_TOLERANCE") "20%")
        (field (name "DB_VOLTAGE") "6.3V")
        (field (name "DB_MANUFACTURER_PART") "KEMET    C0603C106M9PAC")
      )
      (libsource (lib "Database_Libs1") (part "C"))
    )
    (comp (ref "C120")
      (value "C")
      (footprint "SMD_0402_CAPC1005X55N")
      (fields
        (field (name "DB_PART_NUMBER") "CAP000022751")
        (field (name "DB_VALUE") "100nF")
        (field (name "DB_TOLERANCE") "20%")
        (field (name "DB_VOLTAGE") "16V")
        (field (name "DB_MANUFACTURER_PART") "KEMET    C0402F104M4RAC")
      )
      (libsource (lib "Database_Libs1") (part "C"))
    )
    (comp (ref "C121")
      (value "C")
      (footprint "SMD_0402_CAPC1005X55N")
      (fields
        (field (name "DB_PART_NUMBER") "CAP000022751")
        (field (name "DB_VALUE") "100nF")
        (field (name "DB_TOLERANCE") "20%")
        (field (name "DB_VOLTAGE") "16V")
        (field (name "DB_MANUFACTURER_PART") "KEMET    C0402F104M4RAC")
      )
      (libsource (lib "Database_Libs1") (part "C"))
    )
    (comp (ref "C122")
      (value "C")
      (footprint "SMD_0402_CAPC1005X55N")
      (fields
        (field (name "DB_PART_NUMBER") "CAP000022751")
        (field (name "DB_VALUE") "100nF")
        (field (name "DB_TOLERANCE") "20%")
        (field (name "DB_VOLTAGE") "16V")
        (field (name "DB_MANUFACTURER_PART") "KEMET    C0402F104M4RAC")
      )
      (libsource (lib "Database_Libs1") (part "C"))
    )
    (comp (ref "C123")
      (value "C")
      (footprint "SMD_0402_CAPC1005X55N")
      (fields
        (field (name "DB_PART_NUMBER") "CAP000022751")
        (field (name "DB_VALUE") "100nF")
        (field (name "DB_TOLERANCE") "20%")
        (field (name "DB_VOLTAGE") "16V")
        (field (name "DB_MANUFACTURER_PART") "KEMET    C0402F104M4RAC")
      )
      (libsource (lib "Database_Libs1") (part "C"))
    )
    (comp (ref "C124")
      (value "C")
      (footprint "SMD_0603_CAPC1608X95N")
      (fields
        (field (name "DB_PART_NUMBER") "CAP000022968")
        (field (name "DB_VALUE") "220nF")
        (field (name "DB_TOLERANCE") "10%")
        (field (name "DB_VOLTAGE") "25V")
        (field (name "DB_MANUFACTURER_PART") "KEMET    C0603F224K3RAC")
      )
      (libsource (lib "Database_Libs1") (part "C"))
    )
    (comp (ref "C125")
      (value "C")
      (footprint "SMD_0603_CAPC1608X95N")
      (fields
        (field (name "DB_PART_NUMBER") "CAP000022968")
        (field (name "DB_VALUE") "220nF")
        (field (name "DB_TOLERANCE") "10%")
        (field (name "DB_VOLTAGE") "25V")
        (field (name "DB_MANUFACTURER_PART") "KEMET    C0603F224K3RAC")
      )
      (libsource (lib "Database_Libs1") (part "C"))
    )
    (comp (ref "C126")
      (value "C")
      (footprint "SMD_0603_CAPC1608X95N")
      (fields
        (field (name "DB_PART_NUMBER") "CAP000022968")
        (field (name "DB_VALUE") "220nF")
        (field (name "DB_TOLERANCE") "10%")
        (field (name "DB_VOLTAGE") "25V")
        (field (name "DB_MANUFACTURER_PART") "KEMET    C0603F224K3RAC")
      )
      (libsource (lib "Database_Libs1") (part "C"))
    )
    (comp (ref "C127")
      (value "C")
      (footprint "SMD_0603_CAPC1608X95N")
      (fields
        (field (name "DB_PART_NUMBER") "CAP000022968")
        (field (name "DB_VALUE") "220nF")
        (field (name "DB_TOLERANCE") "10%")
        (field (name "DB_VOLTAGE") "25V")
        (field (name "DB_MANUFACTURER_PART") "KEMET    C0603F224K3RAC")
      )
      (libsource (lib "Database_Libs1") (part "C"))
    )
    (comp (ref "C128")
      (value "C")
      (footprint "SMD_1210_CAPC3225X270N")
      (fields
        (field (name "DB_PART_NUMBER") "CAP000043701")
        (field (name "DB_VALUE") "100uF")
        (field (name "DB_TOLERANCE") "20%")
        (field (name "DB_VOLTAGE") "6.3V")
        (field (name "DB_MANUFACTURER_PART") "KEMET    C1210C107M9PAC")
      )
      (libsource (lib "Database_Libs1") (part "C"))
    )
    (comp (ref "C129")
      (value "C")
      (footprint "SMD_1210_CAPC3225X270N")
      (fields
        (field (name "DB_PART_NUMBER") "CAP000043701")
        (field (name "DB_VALUE") "100uF")
        (field (name "DB_TOLERANCE") "20%")
        (field (name "DB_VOLTAGE") "6.3V")
        (field (name "DB_MANUFACTURER_PART") "KEMET    C1210C107M9PAC")
      )
      (libsource (lib "Database_Libs1") (part "C"))
    )
    (comp (ref "C130")
      (value "C")
      (footprint "SMD_1210_CAPC3225X279N")
      (fields
        (field (name "DB_PART_NUMBER") "CAP000047355")
        (field (name "DB_VALUE") "220uF")
        (field (name "DB_TOLERANCE") "20%")
        (field (name "DB_VOLTAGE") "6.3V")
        (field (name "DB_MANUFACTURER_PART") "SAMSUNG    CL32A227MQVNNNE")
        (field (name "DB_APPROVED_BY") "VSN")
      )
      (libsource (lib "Database_Libs1") (part "C"))
    )
    (comp (ref "C131")
      (value "C")
      (footprint "SMD_1210_CAPC3225X279N")
      (fields
        (field (name "DB_PART_NUMBER") "CAP000047355")
        (field (name "DB_VALUE") "220uF")
        (field (name "DB_TOLERANCE") "20%")
        (field (name "DB_VOLTAGE") "6.3V")
        (field (name "DB_MANUFACTURER_PART") "SAMSUNG    CL32A227MQVNNNE")
        (field (name "DB_APPROVED_BY") "VSN")
      )
      (libsource (lib "Database_Libs1") (part "C"))
    )
    (comp (ref "C132")
      (value "C")
      (footprint "SMD_1210_CAPC3225X279N")
      (fields
        (field (name "DB_PART_NUMBER") "CAP000047355")
        (field (name "DB_VALUE") "220uF")
        (field (name "DB_TOLERANCE") "20%")
        (field (name "DB_VOLTAGE") "6.3V")
        (field (name "DB_MANUFACTURER_PART") "SAMSUNG    CL32A227MQVNNNE")
        (field (name "DB_APPROVED_BY") "VSN")
      )
      (libsource (lib "Database_Libs1") (part "C"))
    )
    (comp (ref "C133")
      (value "C")
      (footprint "SMD_1210_CAPC3225X270N")
      (fields
        (field (name "DB_PART_NUMBER") "CAP000043701")
        (field (name "DB_VALUE") "100uF")
        (field (name "DB_TOLERANCE") "20%")
        (field (name "DB_VOLTAGE") "6.3V")
        (field (name "DB_MANUFACTURER_PART") "KEMET    C1210C107M9PAC")
      )
      (libsource (lib "Database_Libs1") (part "C"))
    )
    (comp (ref "C134")
      (value "C")
      (footprint "SMD_1210_CAPC3225X270N")
      (fields
        (field (name "DB_PART_NUMBER") "CAP000043701")
        (field (name "DB_VALUE") "100uF")
        (field (name "DB_TOLERANCE") "20%")
        (field (name "DB_VOLTAGE") "6.3V")
        (field (name "DB_MANUFACTURER_PART") "KEMET    C1210C107M9PAC")
      )
      (libsource (lib "Database_Libs1") (part "C"))
    )
    (comp (ref "C135")
      (value "C")
      (footprint "SMD_1210_CAPC3225X279N")
      (fields
        (field (name "DB_PART_NUMBER") "CAP000047355")
        (field (name "DB_VALUE") "220uF")
        (field (name "DB_TOLERANCE") "20%")
        (field (name "DB_VOLTAGE") "6.3V")
        (field (name "DB_MANUFACTURER_PART") "SAMSUNG    CL32A227MQVNNNE")
        (field (name "DB_APPROVED_BY") "VSN")
      )
      (libsource (lib "Database_Libs1") (part "C"))
    )
    (comp (ref "C136")
      (value "C")
      (footprint "SMD_1210_CAPC3225X279N")
      (fields
        (field (name "DB_PART_NUMBER") "CAP000047355")
        (field (name "DB_VALUE") "220uF")
        (field (name "DB_TOLERANCE") "20%")
        (field (name "DB_VOLTAGE") "6.3V")
        (field (name "DB_MANUFACTURER_PART") "SAMSUNG    CL32A227MQVNNNE")
        (field (name "DB_APPROVED_BY") "VSN")
      )
      (libsource (lib "Database_Libs1") (part "C"))
    )
    (comp (ref "C137")
      (value "C")
      (footprint "SMD_1210_CAPC3225X279N")
      (fields
        (field (name "DB_PART_NUMBER") "CAP000047355")
        (field (name "DB_VALUE") "220uF")
        (field (name "DB_TOLERANCE") "20%")
        (field (name "DB_VOLTAGE") "6.3V")
        (field (name "DB_MANUFACTURER_PART") "SAMSUNG    CL32A227MQVNNNE")
        (field (name "DB_APPROVED_BY") "VSN")
      )
      (libsource (lib "Database_Libs1") (part "C"))
    )
    (comp (ref "C138")
      (value "C")
      (footprint "SMD_1210_CAPC3225X270N")
      (fields
        (field (name "DB_PART_NUMBER") "CAP000043701")
        (field (name "DB_VALUE") "100uF")
        (field (name "DB_TOLERANCE") "20%")
        (field (name "DB_VOLTAGE") "6.3V")
        (field (name "DB_MANUFACTURER_PART") "KEMET    C1210C107M9PAC")
      )
      (libsource (lib "Database_Libs1") (part "C"))
    )
    (comp (ref "C139")
      (value "C")
      (footprint "SMD_1210_CAPC3225X270N")
      (fields
        (field (name "DB_PART_NUMBER") "CAP000043701")
        (field (name "DB_VALUE") "100uF")
        (field (name "DB_TOLERANCE") "20%")
        (field (name "DB_VOLTAGE") "6.3V")
        (field (name "DB_MANUFACTURER_PART") "KEMET    C1210C107M9PAC")
      )
      (libsource (lib "Database_Libs1") (part "C"))
    )
    (comp (ref "C140")
      (value "C")
      (footprint "SMD_1210_CAPC3225X279N")
      (fields
        (field (name "DB_PART_NUMBER") "CAP000047355")
        (field (name "DB_VALUE") "220uF")
        (field (name "DB_TOLERANCE") "20%")
        (field (name "DB_VOLTAGE") "6.3V")
        (field (name "DB_MANUFACTURER_PART") "SAMSUNG    CL32A227MQVNNNE")
        (field (name "DB_APPROVED_BY") "VSN")
      )
      (libsource (lib "Database_Libs1") (part "C"))
    )
    (comp (ref "C141")
      (value "C")
      (footprint "SMD_1210_CAPC3225X279N")
      (fields
        (field (name "DB_PART_NUMBER") "CAP000047355")
        (field (name "DB_VALUE") "220uF")
        (field (name "DB_TOLERANCE") "20%")
        (field (name "DB_VOLTAGE") "6.3V")
        (field (name "DB_MANUFACTURER_PART") "SAMSUNG    CL32A227MQVNNNE")
        (field (name "DB_APPROVED_BY") "VSN")
      )
      (libsource (lib "Database_Libs1") (part "C"))
    )
    (comp (ref "C142")
      (value "C")
      (footprint "SMD_1210_CAPC3225X279N")
      (fields
        (field (name "DB_PART_NUMBER") "CAP000047355")
        (field (name "DB_VALUE") "220uF")
        (field (name "DB_TOLERANCE") "20%")
        (field (name "DB_VOLTAGE") "6.3V")
        (field (name "DB_MANUFACTURER_PART") "SAMSUNG    CL32A227MQVNNNE")
        (field (name "DB_APPROVED_BY") "VSN")
      )
      (libsource (lib "Database_Libs1") (part "C"))
    )
    (comp (ref "C143")
      (value "C")
      (footprint "SMD_1210_CAPC3225X270N")
      (fields
        (field (name "DB_PART_NUMBER") "CAP000043701")
        (field (name "DB_VALUE") "100uF")
        (field (name "DB_TOLERANCE") "20%")
        (field (name "DB_VOLTAGE") "6.3V")
        (field (name "DB_MANUFACTURER_PART") "KEMET    C1210C107M9PAC")
      )
      (libsource (lib "Database_Libs1") (part "C"))
    )
    (comp (ref "C144")
      (value "C")
      (footprint "SMD_1210_CAPC3225X270N")
      (fields
        (field (name "DB_PART_NUMBER") "CAP000043701")
        (field (name "DB_VALUE") "100uF")
        (field (name "DB_TOLERANCE") "20%")
        (field (name "DB_VOLTAGE") "6.3V")
        (field (name "DB_MANUFACTURER_PART") "KEMET    C1210C107M9PAC")
      )
      (libsource (lib "Database_Libs1") (part "C"))
    )
    (comp (ref "C145")
      (value "C")
      (footprint "SMD_1210_CAPC3225X279N")
      (fields
        (field (name "DB_PART_NUMBER") "CAP000047355")
        (field (name "DB_VALUE") "220uF")
        (field (name "DB_TOLERANCE") "20%")
        (field (name "DB_VOLTAGE") "6.3V")
        (field (name "DB_MANUFACTURER_PART") "SAMSUNG    CL32A227MQVNNNE")
        (field (name "DB_APPROVED_BY") "VSN")
      )
      (libsource (lib "Database_Libs1") (part "C"))
    )
    (comp (ref "C146")
      (value "C")
      (footprint "SMD_1210_CAPC3225X279N")
      (fields
        (field (name "DB_PART_NUMBER") "CAP000047355")
        (field (name "DB_VALUE") "220uF")
        (field (name "DB_TOLERANCE") "20%")
        (field (name "DB_VOLTAGE") "6.3V")
        (field (name "DB_MANUFACTURER_PART") "SAMSUNG    CL32A227MQVNNNE")
        (field (name "DB_APPROVED_BY") "VSN")
      )
      (libsource (lib "Database_Libs1") (part "C"))
    )
    (comp (ref "C147")
      (value "C")
      (footprint "SMD_1210_CAPC3225X279N")
      (fields
        (field (name "DB_PART_NUMBER") "CAP000047355")
        (field (name "DB_VALUE") "220uF")
        (field (name "DB_TOLERANCE") "20%")
        (field (name "DB_VOLTAGE") "6.3V")
        (field (name "DB_MANUFACTURER_PART") "SAMSUNG    CL32A227MQVNNNE")
        (field (name "DB_APPROVED_BY") "VSN")
      )
      (libsource (lib "Database_Libs1") (part "C"))
    )
    (comp (ref "C236")
      (value "C")
      (footprint "SMD_1210_CAPC3225X279N")
      (fields
        (field (name "DB_PART_NUMBER") "CAP000047355")
        (field (name "DB_VALUE") "220uF")
        (field (name "DB_TOLERANCE") "20%")
        (field (name "DB_VOLTAGE") "6.3V")
        (field (name "DB_MANUFACTURER_PART") "SAMSUNG    CL32A227MQVNNNE")
        (field (name "DB_APPROVED_BY") "VSN")
      )
      (libsource (lib "Database_Libs1") (part "C"))
    )
    (comp (ref "C348")
      (value "C")
      (footprint "SMD_1210_CAPC3225X270N")
      (fields
        (field (name "DB_PART_NUMBER") "CAP000043701")
        (field (name "DB_VALUE") "100uF")
        (field (name "DB_TOLERANCE") "20%")
        (field (name "DB_VOLTAGE") "6.3V")
        (field (name "DB_MANUFACTURER_PART") "KEMET    C1210C107M9PAC")
      )
      (libsource (lib "Database_Libs1") (part "C"))
    )
    (comp (ref "C349")
      (value "C")
      (footprint "SMD_1210_CAPC3225X270N")
      (fields
        (field (name "DB_PART_NUMBER") "CAP000043701")
        (field (name "DB_VALUE") "100uF")
        (field (name "DB_TOLERANCE") "20%")
        (field (name "DB_VOLTAGE") "6.3V")
        (field (name "DB_MANUFACTURER_PART") "KEMET    C1210C107M9PAC")
      )
      (libsource (lib "Database_Libs1") (part "C"))
    )
    (comp (ref "C350")
      (value "C")
      (footprint "SMD_1210_CAPC3225X279N")
      (fields
        (field (name "DB_PART_NUMBER") "CAP000047355")
        (field (name "DB_VALUE") "220uF")
        (field (name "DB_TOLERANCE") "20%")
        (field (name "DB_VOLTAGE") "6.3V")
        (field (name "DB_MANUFACTURER_PART") "SAMSUNG    CL32A227MQVNNNE")
        (field (name "DB_APPROVED_BY") "VSN")
      )
      (libsource (lib "Database_Libs1") (part "C"))
    )
    (comp (ref "C351")
      (value "C")
      (footprint "SMD_1210_CAPC3225X279N")
      (fields
        (field (name "DB_PART_NUMBER") "CAP000047355")
        (field (name "DB_VALUE") "220uF")
        (field (name "DB_TOLERANCE") "20%")
        (field (name "DB_VOLTAGE") "6.3V")
        (field (name "DB_MANUFACTURER_PART") "SAMSUNG    CL32A227MQVNNNE")
        (field (name "DB_APPROVED_BY") "VSN")
      )
      (libsource (lib "Database_Libs1") (part "C"))
    )
    (comp (ref "C352")
      (value "C")
      (footprint "SMD_1210_CAPC3225X279N")
      (fields
        (field (name "DB_PART_NUMBER") "CAP000047355")
        (field (name "DB_VALUE") "220uF")
        (field (name "DB_TOLERANCE") "20%")
        (field (name "DB_VOLTAGE") "6.3V")
        (field (name "DB_MANUFACTURER_PART") "SAMSUNG    CL32A227MQVNNNE")
        (field (name "DB_APPROVED_BY") "VSN")
      )
      (libsource (lib "Database_Libs1") (part "C"))
    )
    (comp (ref "C353")
      (value "C")
      (footprint "SMD_1210_CAPC3225X270N")
      (fields
        (field (name "DB_PART_NUMBER") "CAP000043701")
        (field (name "DB_VALUE") "100uF")
        (field (name "DB_TOLERANCE") "20%")
        (field (name "DB_VOLTAGE") "6.3V")
        (field (name "DB_MANUFACTURER_PART") "KEMET    C1210C107M9PAC")
      )
      (libsource (lib "Database_Libs1") (part "C"))
    )
    (comp (ref "C354")
      (value "C")
      (footprint "SMD_1210_CAPC3225X270N")
      (fields
        (field (name "DB_PART_NUMBER") "CAP000043701")
        (field (name "DB_VALUE") "100uF")
        (field (name "DB_TOLERANCE") "20%")
        (field (name "DB_VOLTAGE") "6.3V")
        (field (name "DB_MANUFACTURER_PART") "KEMET    C1210C107M9PAC")
      )
      (libsource (lib "Database_Libs1") (part "C"))
    )
    (comp (ref "C355")
      (value "C")
      (footprint "SMD_1210_CAPC3225X279N")
      (fields
        (field (name "DB_PART_NUMBER") "CAP000047355")
        (field (name "DB_VALUE") "220uF")
        (field (name "DB_TOLERANCE") "20%")
        (field (name "DB_VOLTAGE") "6.3V")
        (field (name "DB_MANUFACTURER_PART") "SAMSUNG    CL32A227MQVNNNE")
        (field (name "DB_APPROVED_BY") "VSN")
      )
      (libsource (lib "Database_Libs1") (part "C"))
    )
    (comp (ref "C356")
      (value "C")
      (footprint "SMD_1210_CAPC3225X279N")
      (fields
        (field (name "DB_PART_NUMBER") "CAP000047355")
        (field (name "DB_VALUE") "220uF")
        (field (name "DB_TOLERANCE") "20%")
        (field (name "DB_VOLTAGE") "6.3V")
        (field (name "DB_MANUFACTURER_PART") "SAMSUNG    CL32A227MQVNNNE")
        (field (name "DB_APPROVED_BY") "VSN")
      )
      (libsource (lib "Database_Libs1") (part "C"))
    )
    (comp (ref "C357")
      (value "C")
      (footprint "SMD_1210_CAPC3225X279N")
      (fields
        (field (name "DB_PART_NUMBER") "CAP000047355")
        (field (name "DB_VALUE") "220uF")
        (field (name "DB_TOLERANCE") "20%")
        (field (name "DB_VOLTAGE") "6.3V")
        (field (name "DB_MANUFACTURER_PART") "SAMSUNG    CL32A227MQVNNNE")
        (field (name "DB_APPROVED_BY") "VSN")
      )
      (libsource (lib "Database_Libs1") (part "C"))
    )
    (comp (ref "C358")
      (value "C")
      (footprint "SMD_1210_CAPC3225X270N")
      (fields
        (field (name "DB_PART_NUMBER") "CAP000043701")
        (field (name "DB_VALUE") "100uF")
        (field (name "DB_TOLERANCE") "20%")
        (field (name "DB_VOLTAGE") "6.3V")
        (field (name "DB_MANUFACTURER_PART") "KEMET    C1210C107M9PAC")
      )
      (libsource (lib "Database_Libs1") (part "C"))
    )
    (comp (ref "C359")
      (value "C")
      (footprint "SMD_1210_CAPC3225X270N")
      (fields
        (field (name "DB_PART_NUMBER") "CAP000043701")
        (field (name "DB_VALUE") "100uF")
        (field (name "DB_TOLERANCE") "20%")
        (field (name "DB_VOLTAGE") "6.3V")
        (field (name "DB_MANUFACTURER_PART") "KEMET    C1210C107M9PAC")
      )
      (libsource (lib "Database_Libs1") (part "C"))
    )
    (comp (ref "C360")
      (value "C")
      (footprint "SMD_1210_CAPC3225X279N")
      (fields
        (field (name "DB_PART_NUMBER") "CAP000047355")
        (field (name "DB_VALUE") "220uF")
        (field (name "DB_TOLERANCE") "20%")
        (field (name "DB_VOLTAGE") "6.3V")
        (field (name "DB_MANUFACTURER_PART") "SAMSUNG    CL32A227MQVNNNE")
        (field (name "DB_APPROVED_BY") "VSN")
      )
      (libsource (lib "Database_Libs1") (part "C"))
    )
    (comp (ref "C361")
      (value "C")
      (footprint "SMD_1210_CAPC3225X279N")
      (fields
        (field (name "DB_PART_NUMBER") "CAP000047355")
        (field (name "DB_VALUE") "220uF")
        (field (name "DB_TOLERANCE") "20%")
        (field (name "DB_VOLTAGE") "6.3V")
        (field (name "DB_MANUFACTURER_PART") "SAMSUNG    CL32A227MQVNNNE")
        (field (name "DB_APPROVED_BY") "VSN")
      )
      (libsource (lib "Database_Libs1") (part "C"))
    )
    (comp (ref "C362")
      (value "C")
      (footprint "SMD_1210_CAPC3225X279N")
      (fields
        (field (name "DB_PART_NUMBER") "CAP000047355")
        (field (name "DB_VALUE") "220uF")
        (field (name "DB_TOLERANCE") "20%")
        (field (name "DB_VOLTAGE") "6.3V")
        (field (name "DB_MANUFACTURER_PART") "SAMSUNG    CL32A227MQVNNNE")
        (field (name "DB_APPROVED_BY") "VSN")
      )
      (libsource (lib "Database_Libs1") (part "C"))
    )
    (comp (ref "C363")
      (value "C")
      (footprint "SMD_1210_CAPC3225X270N")
      (fields
        (field (name "DB_PART_NUMBER") "CAP000043701")
        (field (name "DB_VALUE") "100uF")
        (field (name "DB_TOLERANCE") "20%")
        (field (name "DB_VOLTAGE") "6.3V")
        (field (name "DB_MANUFACTURER_PART") "KEMET    C1210C107M9PAC")
      )
      (libsource (lib "Database_Libs1") (part "C"))
    )
    (comp (ref "C364")
      (value "C")
      (footprint "SMD_1210_CAPC3225X270N")
      (fields
        (field (name "DB_PART_NUMBER") "CAP000043701")
        (field (name "DB_VALUE") "100uF")
        (field (name "DB_TOLERANCE") "20%")
        (field (name "DB_VOLTAGE") "6.3V")
        (field (name "DB_MANUFACTURER_PART") "KEMET    C1210C107M9PAC")
      )
      (libsource (lib "Database_Libs1") (part "C"))
    )
    (comp (ref "C365")
      (value "C")
      (footprint "SMD_1210_CAPC3225X279N")
      (fields
        (field (name "DB_PART_NUMBER") "CAP000047355")
        (field (name "DB_VALUE") "220uF")
        (field (name "DB_TOLERANCE") "20%")
        (field (name "DB_VOLTAGE") "6.3V")
        (field (name "DB_MANUFACTURER_PART") "SAMSUNG    CL32A227MQVNNNE")
        (field (name "DB_APPROVED_BY") "VSN")
      )
      (libsource (lib "Database_Libs1") (part "C"))
    )
    (comp (ref "C366")
      (value "C")
      (footprint "SMD_1210_CAPC3225X279N")
      (fields
        (field (name "DB_PART_NUMBER") "CAP000047355")
        (field (name "DB_VALUE") "220uF")
        (field (name "DB_TOLERANCE") "20%")
        (field (name "DB_VOLTAGE") "6.3V")
        (field (name "DB_MANUFACTURER_PART") "SAMSUNG    CL32A227MQVNNNE")
        (field (name "DB_APPROVED_BY") "VSN")
      )
      (libsource (lib "Database_Libs1") (part "C"))
    )
    (comp (ref "C367")
      (value "C")
      (footprint "SMD_1210_CAPC3225X279N")
      (fields
        (field (name "DB_PART_NUMBER") "CAP000047355")
        (field (name "DB_VALUE") "220uF")
        (field (name "DB_TOLERANCE") "20%")
        (field (name "DB_VOLTAGE") "6.3V")
        (field (name "DB_MANUFACTURER_PART") "SAMSUNG    CL32A227MQVNNNE")
        (field (name "DB_APPROVED_BY") "VSN")
      )
      (libsource (lib "Database_Libs1") (part "C"))
    )
    (comp (ref "C368")
      (value "C")
      (footprint "SMD_1210_CAPC3225X270N")
      (fields
        (field (name "DB_PART_NUMBER") "CAP000043701")
        (field (name "DB_VALUE") "100uF")
        (field (name "DB_TOLERANCE") "20%")
        (field (name "DB_VOLTAGE") "6.3V")
        (field (name "DB_MANUFACTURER_PART") "KEMET    C1210C107M9PAC")
      )
      (libsource (lib "Database_Libs1") (part "C"))
    )
    (comp (ref "C369")
      (value "C")
      (footprint "SMD_1210_CAPC3225X270N")
      (fields
        (field (name "DB_PART_NUMBER") "CAP000043701")
        (field (name "DB_VALUE") "100uF")
        (field (name "DB_TOLERANCE") "20%")
        (field (name "DB_VOLTAGE") "6.3V")
        (field (name "DB_MANUFACTURER_PART") "KEMET    C1210C107M9PAC")
      )
      (libsource (lib "Database_Libs1") (part "C"))
    )
    (comp (ref "C370")
      (value "C")
      (footprint "SMD_1210_CAPC3225X279N")
      (fields
        (field (name "DB_PART_NUMBER") "CAP000047355")
        (field (name "DB_VALUE") "220uF")
        (field (name "DB_TOLERANCE") "20%")
        (field (name "DB_VOLTAGE") "6.3V")
        (field (name "DB_MANUFACTURER_PART") "SAMSUNG    CL32A227MQVNNNE")
        (field (name "DB_APPROVED_BY") "VSN")
      )
      (libsource (lib "Database_Libs1") (part "C"))
    )
    (comp (ref "C371")
      (value "C")
      (footprint "SMD_1210_CAPC3225X279N")
      (fields
        (field (name "DB_PART_NUMBER") "CAP000047355")
        (field (name "DB_VALUE") "220uF")
        (field (name "DB_TOLERANCE") "20%")
        (field (name "DB_VOLTAGE") "6.3V")
        (field (name "DB_MANUFACTURER_PART") "SAMSUNG    CL32A227MQVNNNE")
        (field (name "DB_APPROVED_BY") "VSN")
      )
      (libsource (lib "Database_Libs1") (part "C"))
    )
    (comp (ref "C372")
      (value "C")
      (footprint "SMD_1210_CAPC3225X279N")
      (fields
        (field (name "DB_PART_NUMBER") "CAP000047355")
        (field (name "DB_VALUE") "220uF")
        (field (name "DB_TOLERANCE") "20%")
        (field (name "DB_VOLTAGE") "6.3V")
        (field (name "DB_MANUFACTURER_PART") "SAMSUNG    CL32A227MQVNNNE")
        (field (name "DB_APPROVED_BY") "VSN")
      )
      (libsource (lib "Database_Libs1") (part "C"))
    )
    (comp (ref "C373")
      (value "C")
      (footprint "SMD_1210_CAPC3225X270N")
      (fields
        (field (name "DB_PART_NUMBER") "CAP000043701")
        (field (name "DB_VALUE") "100uF")
        (field (name "DB_TOLERANCE") "20%")
        (field (name "DB_VOLTAGE") "6.3V")
        (field (name "DB_MANUFACTURER_PART") "KEMET    C1210C107M9PAC")
      )
      (libsource (lib "Database_Libs1") (part "C"))
    )
    (comp (ref "C374")
      (value "C")
      (footprint "SMD_1210_CAPC3225X270N")
      (fields
        (field (name "DB_PART_NUMBER") "CAP000043701")
        (field (name "DB_VALUE") "100uF")
        (field (name "DB_TOLERANCE") "20%")
        (field (name "DB_VOLTAGE") "6.3V")
        (field (name "DB_MANUFACTURER_PART") "KEMET    C1210C107M9PAC")
      )
      (libsource (lib "Database_Libs1") (part "C"))
    )
    (comp (ref "C375")
      (value "C")
      (footprint "SMD_1210_CAPC3225X279N")
      (fields
        (field (name "DB_PART_NUMBER") "CAP000047355")
        (field (name "DB_VALUE") "220uF")
        (field (name "DB_TOLERANCE") "20%")
        (field (name "DB_VOLTAGE") "6.3V")
        (field (name "DB_MANUFACTURER_PART") "SAMSUNG    CL32A227MQVNNNE")
        (field (name "DB_APPROVED_BY") "VSN")
      )
      (libsource (lib "Database_Libs1") (part "C"))
    )
    (comp (ref "C376")
      (value "C")
      (footprint "SMD_1210_CAPC3225X279N")
      (fields
        (field (name "DB_PART_NUMBER") "CAP000047355")
        (field (name "DB_VALUE") "220uF")
        (field (name "DB_TOLERANCE") "20%")
        (field (name "DB_VOLTAGE") "6.3V")
        (field (name "DB_MANUFACTURER_PART") "SAMSUNG    CL32A227MQVNNNE")
        (field (name "DB_APPROVED_BY") "VSN")
      )
      (libsource (lib "Database_Libs1") (part "C"))
    )
    (comp (ref "C377")
      (value "C")
      (footprint "SMD_1210_CAPC3225X279N")
      (fields
        (field (name "DB_PART_NUMBER") "CAP000047355")
        (field (name "DB_VALUE") "220uF")
        (field (name "DB_TOLERANCE") "20%")
        (field (name "DB_VOLTAGE") "6.3V")
        (field (name "DB_MANUFACTURER_PART") "SAMSUNG    CL32A227MQVNNNE")
        (field (name "DB_APPROVED_BY") "VSN")
      )
      (libsource (lib "Database_Libs1") (part "C"))
    )
    (comp (ref "C378")
      (value "C")
      (footprint "SMD_1210_CAPC3225X270N")
      (fields
        (field (name "DB_PART_NUMBER") "CAP000043701")
        (field (name "DB_VALUE") "100uF")
        (field (name "DB_TOLERANCE") "20%")
        (field (name "DB_VOLTAGE") "6.3V")
        (field (name "DB_MANUFACTURER_PART") "KEMET    C1210C107M9PAC")
      )
      (libsource (lib "Database_Libs1") (part "C"))
    )
    (comp (ref "C379")
      (value "C")
      (footprint "SMD_1210_CAPC3225X270N")
      (fields
        (field (name "DB_PART_NUMBER") "CAP000043701")
        (field (name "DB_VALUE") "100uF")
        (field (name "DB_TOLERANCE") "20%")
        (field (name "DB_VOLTAGE") "6.3V")
        (field (name "DB_MANUFACTURER_PART") "KEMET    C1210C107M9PAC")
      )
      (libsource (lib "Database_Libs1") (part "C"))
    )
    (comp (ref "C380")
      (value "C")
      (footprint "SMD_1210_CAPC3225X279N")
      (fields
        (field (name "DB_PART_NUMBER") "CAP000047355")
        (field (name "DB_VALUE") "220uF")
        (field (name "DB_TOLERANCE") "20%")
        (field (name "DB_VOLTAGE") "6.3V")
        (field (name "DB_MANUFACTURER_PART") "SAMSUNG    CL32A227MQVNNNE")
        (field (name "DB_APPROVED_BY") "VSN")
      )
      (libsource (lib "Database_Libs1") (part "C"))
    )
    (comp (ref "C381")
      (value "C")
      (footprint "SMD_1210_CAPC3225X279N")
      (fields
        (field (name "DB_PART_NUMBER") "CAP000047355")
        (field (name "DB_VALUE") "220uF")
        (field (name "DB_TOLERANCE") "20%")
        (field (name "DB_VOLTAGE") "6.3V")
        (field (name "DB_MANUFACTURER_PART") "SAMSUNG    CL32A227MQVNNNE")
        (field (name "DB_APPROVED_BY") "VSN")
      )
      (libsource (lib "Database_Libs1") (part "C"))
    )
    (comp (ref "C382")
      (value "C")
      (footprint "SMD_1210_CAPC3225X279N")
      (fields
        (field (name "DB_PART_NUMBER") "CAP000047355")
        (field (name "DB_VALUE") "220uF")
        (field (name "DB_TOLERANCE") "20%")
        (field (name "DB_VOLTAGE") "6.3V")
        (field (name "DB_MANUFACTURER_PART") "SAMSUNG    CL32A227MQVNNNE")
        (field (name "DB_APPROVED_BY") "VSN")
      )
      (libsource (lib "Database_Libs1") (part "C"))
    )
    (comp (ref "C383")
      (value "C")
      (footprint "SMD_1210_CAPC3225X270N")
      (fields
        (field (name "DB_PART_NUMBER") "CAP000043701")
        (field (name "DB_VALUE") "100uF")
        (field (name "DB_TOLERANCE") "20%")
        (field (name "DB_VOLTAGE") "6.3V")
        (field (name "DB_MANUFACTURER_PART") "KEMET    C1210C107M9PAC")
      )
      (libsource (lib "Database_Libs1") (part "C"))
    )
    (comp (ref "C384")
      (value "C")
      (footprint "SMD_1210_CAPC3225X270N")
      (fields
        (field (name "DB_PART_NUMBER") "CAP000043701")
        (field (name "DB_VALUE") "100uF")
        (field (name "DB_TOLERANCE") "20%")
        (field (name "DB_VOLTAGE") "6.3V")
        (field (name "DB_MANUFACTURER_PART") "KEMET    C1210C107M9PAC")
      )
      (libsource (lib "Database_Libs1") (part "C"))
    )
    (comp (ref "C385")
      (value "C")
      (footprint "SMD_1210_CAPC3225X279N")
      (fields
        (field (name "DB_PART_NUMBER") "CAP000047355")
        (field (name "DB_VALUE") "220uF")
        (field (name "DB_TOLERANCE") "20%")
        (field (name "DB_VOLTAGE") "6.3V")
        (field (name "DB_MANUFACTURER_PART") "SAMSUNG    CL32A227MQVNNNE")
        (field (name "DB_APPROVED_BY") "VSN")
      )
      (libsource (lib "Database_Libs1") (part "C"))
    )
    (comp (ref "C386")
      (value "C")
      (footprint "SMD_1210_CAPC3225X279N")
      (fields
        (field (name "DB_PART_NUMBER") "CAP000047355")
        (field (name "DB_VALUE") "220uF")
        (field (name "DB_TOLERANCE") "20%")
        (field (name "DB_VOLTAGE") "6.3V")
        (field (name "DB_MANUFACTURER_PART") "SAMSUNG    CL32A227MQVNNNE")
        (field (name "DB_APPROVED_BY") "VSN")
      )
      (libsource (lib "Database_Libs1") (part "C"))
    )
    (comp (ref "C387")
      (value "C")
      (footprint "SMD_1210_CAPC3225X279N")
      (fields
        (field (name "DB_PART_NUMBER") "CAP000047355")
        (field (name "DB_VALUE") "220uF")
        (field (name "DB_TOLERANCE") "20%")
        (field (name "DB_VOLTAGE") "6.3V")
        (field (name "DB_MANUFACTURER_PART") "SAMSUNG    CL32A227MQVNNNE")
        (field (name "DB_APPROVED_BY") "VSN")
      )
      (libsource (lib "Database_Libs1") (part "C"))
    )
    (comp (ref "C388")
      (value "C")
      (footprint "SMD_1210_CAPC3225X279N")
      (fields
        (field (name "DB_PART_NUMBER") "CAP000047355")
        (field (name "DB_VALUE") "220uF")
        (field (name "DB_TOLERANCE") "20%")
        (field (name "DB_VOLTAGE") "6.3V")
        (field (name "DB_MANUFACTURER_PART") "SAMSUNG    CL32A227MQVNNNE")
        (field (name "DB_APPROVED_BY") "VSN")
      )
      (libsource (lib "Database_Libs1") (part "C"))
    )
    (comp (ref "C389")
      (value "C")
      (footprint "SMD_1210_CAPC3225X279N")
      (fields
        (field (name "DB_PART_NUMBER") "CAP000047355")
        (field (name "DB_VALUE") "220uF")
        (field (name "DB_TOLERANCE") "20%")
        (field (name "DB_VOLTAGE") "6.3V")
        (field (name "DB_MANUFACTURER_PART") "SAMSUNG    CL32A227MQVNNNE")
        (field (name "DB_APPROVED_BY") "VSN")
      )
      (libsource (lib "Database_Libs1") (part "C"))
    )
    (comp (ref "C390")
      (value "C")
      (footprint "SMD_1210_CAPC3225X279N")
      (fields
        (field (name "DB_PART_NUMBER") "CAP000047355")
        (field (name "DB_VALUE") "220uF")
        (field (name "DB_TOLERANCE") "20%")
        (field (name "DB_VOLTAGE") "6.3V")
        (field (name "DB_MANUFACTURER_PART") "SAMSUNG    CL32A227MQVNNNE")
        (field (name "DB_APPROVED_BY") "VSN")
      )
      (libsource (lib "Database_Libs1") (part "C"))
    )
    (comp (ref "C391")
      (value "C")
      (footprint "SMD_1210_CAPC3225X270N")
      (fields
        (field (name "DB_PART_NUMBER") "CAP000043701")
        (field (name "DB_VALUE") "100uF")
        (field (name "DB_TOLERANCE") "20%")
        (field (name "DB_VOLTAGE") "6.3V")
        (field (name "DB_MANUFACTURER_PART") "KEMET    C1210C107M9PAC")
      )
      (libsource (lib "Database_Libs1") (part "C"))
    )
    (comp (ref "C392")
      (value "C")
      (footprint "SMD_1210_CAPC3225X270N")
      (fields
        (field (name "DB_PART_NUMBER") "CAP000043701")
        (field (name "DB_VALUE") "100uF")
        (field (name "DB_TOLERANCE") "20%")
        (field (name "DB_VOLTAGE") "6.3V")
        (field (name "DB_MANUFACTURER_PART") "KEMET    C1210C107M9PAC")
      )
      (libsource (lib "Database_Libs1") (part "C"))
    )
    (comp (ref "C393")
      (value "C")
      (footprint "SMD_1210_CAPC3225X279N")
      (fields
        (field (name "DB_PART_NUMBER") "CAP000047355")
        (field (name "DB_VALUE") "220uF")
        (field (name "DB_TOLERANCE") "20%")
        (field (name "DB_VOLTAGE") "6.3V")
        (field (name "DB_MANUFACTURER_PART") "SAMSUNG    CL32A227MQVNNNE")
        (field (name "DB_APPROVED_BY") "VSN")
      )
      (libsource (lib "Database_Libs1") (part "C"))
    )
    (comp (ref "C394")
      (value "C")
      (footprint "SMD_1210_CAPC3225X279N")
      (fields
        (field (name "DB_PART_NUMBER") "CAP000047355")
        (field (name "DB_VALUE") "220uF")
        (field (name "DB_TOLERANCE") "20%")
        (field (name "DB_VOLTAGE") "6.3V")
        (field (name "DB_MANUFACTURER_PART") "SAMSUNG    CL32A227MQVNNNE")
        (field (name "DB_APPROVED_BY") "VSN")
      )
      (libsource (lib "Database_Libs1") (part "C"))
    )
    (comp (ref "C395")
      (value "C")
      (footprint "SMD_1210_CAPC3225X279N")
      (fields
        (field (name "DB_PART_NUMBER") "CAP000047355")
        (field (name "DB_VALUE") "220uF")
        (field (name "DB_TOLERANCE") "20%")
        (field (name "DB_VOLTAGE") "6.3V")
        (field (name "DB_MANUFACTURER_PART") "SAMSUNG    CL32A227MQVNNNE")
        (field (name "DB_APPROVED_BY") "VSN")
      )
      (libsource (lib "Database_Libs1") (part "C"))
    )
    (comp (ref "C396")
      (value "C")
      (footprint "SMD_1210_CAPC3225X279N")
      (fields
        (field (name "DB_PART_NUMBER") "CAP000047355")
        (field (name "DB_VALUE") "220uF")
        (field (name "DB_TOLERANCE") "20%")
        (field (name "DB_VOLTAGE") "6.3V")
        (field (name "DB_MANUFACTURER_PART") "SAMSUNG    CL32A227MQVNNNE")
        (field (name "DB_APPROVED_BY") "VSN")
      )
      (libsource (lib "Database_Libs1") (part "C"))
    )
    (comp (ref "C397")
      (value "C")
      (footprint "SMD_1210_CAPC3225X279N")
      (fields
        (field (name "DB_PART_NUMBER") "CAP000047355")
        (field (name "DB_VALUE") "220uF")
        (field (name "DB_TOLERANCE") "20%")
        (field (name "DB_VOLTAGE") "6.3V")
        (field (name "DB_MANUFACTURER_PART") "SAMSUNG    CL32A227MQVNNNE")
        (field (name "DB_APPROVED_BY") "VSN")
      )
      (libsource (lib "Database_Libs1") (part "C"))
    )
    (comp (ref "C398")
      (value "C")
      (footprint "SMD_1210_CAPC3225X279N")
      (fields
        (field (name "DB_PART_NUMBER") "CAP000047355")
        (field (name "DB_VALUE") "220uF")
        (field (name "DB_TOLERANCE") "20%")
        (field (name "DB_VOLTAGE") "6.3V")
        (field (name "DB_MANUFACTURER_PART") "SAMSUNG    CL32A227MQVNNNE")
        (field (name "DB_APPROVED_BY") "VSN")
      )
      (libsource (lib "Database_Libs1") (part "C"))
    )
    (comp (ref "C399")
      (value "C")
      (footprint "SMD_1210_CAPC3225X279N")
      (fields
        (field (name "DB_PART_NUMBER") "CAP000047355")
        (field (name "DB_VALUE") "220uF")
        (field (name "DB_TOLERANCE") "20%")
        (field (name "DB_VOLTAGE") "6.3V")
        (field (name "DB_MANUFACTURER_PART") "SAMSUNG    CL32A227MQVNNNE")
        (field (name "DB_APPROVED_BY") "VSN")
      )
      (libsource (lib "Database_Libs1") (part "C"))
    )
    (comp (ref "C400")
      (value "C")
      (footprint "SMD_1210_CAPC3225X279N")
      (fields
        (field (name "DB_PART_NUMBER") "CAP000047355")
        (field (name "DB_VALUE") "220uF")
        (field (name "DB_TOLERANCE") "20%")
        (field (name "DB_VOLTAGE") "6.3V")
        (field (name "DB_MANUFACTURER_PART") "SAMSUNG    CL32A227MQVNNNE")
        (field (name "DB_APPROVED_BY") "VSN")
      )
      (libsource (lib "Database_Libs1") (part "C"))
    )
    (comp (ref "C401")
      (value "C")
      (footprint "SMD_1210_CAPC3225X279N")
      (fields
        (field (name "DB_PART_NUMBER") "CAP000047355")
        (field (name "DB_VALUE") "220uF")
        (field (name "DB_TOLERANCE") "20%")
        (field (name "DB_VOLTAGE") "6.3V")
        (field (name "DB_MANUFACTURER_PART") "SAMSUNG    CL32A227MQVNNNE")
        (field (name "DB_APPROVED_BY") "VSN")
      )
      (libsource (lib "Database_Libs1") (part "C"))
    )
    (comp (ref "C402")
      (value "C")
      (footprint "SMD_1210_CAPC3225X270N")
      (fields
        (field (name "DB_PART_NUMBER") "CAP000043701")
        (field (name "DB_VALUE") "100uF")
        (field (name "DB_TOLERANCE") "20%")
        (field (name "DB_VOLTAGE") "6.3V")
        (field (name "DB_MANUFACTURER_PART") "KEMET    C1210C107M9PAC")
      )
      (libsource (lib "Database_Libs1") (part "C"))
    )
    (comp (ref "C403")
      (value "C")
      (footprint "SMD_1210_CAPC3225X270N")
      (fields
        (field (name "DB_PART_NUMBER") "CAP000043701")
        (field (name "DB_VALUE") "100uF")
        (field (name "DB_TOLERANCE") "20%")
        (field (name "DB_VOLTAGE") "6.3V")
        (field (name "DB_MANUFACTURER_PART") "KEMET    C1210C107M9PAC")
      )
      (libsource (lib "Database_Libs1") (part "C"))
    )
    (comp (ref "C404")
      (value "C")
      (footprint "SMD_1210_CAPC3225X270N")
      (fields
        (field (name "DB_PART_NUMBER") "CAP000043701")
        (field (name "DB_VALUE") "100uF")
        (field (name "DB_TOLERANCE") "20%")
        (field (name "DB_VOLTAGE") "6.3V")
        (field (name "DB_MANUFACTURER_PART") "KEMET    C1210C107M9PAC")
      )
      (libsource (lib "Database_Libs1") (part "C"))
    )
    (comp (ref "C405")
      (value "C")
      (footprint "SMD_1210_CAPC3225X270N")
      (fields
        (field (name "DB_PART_NUMBER") "CAP000043701")
        (field (name "DB_VALUE") "100uF")
        (field (name "DB_TOLERANCE") "20%")
        (field (name "DB_VOLTAGE") "6.3V")
        (field (name "DB_MANUFACTURER_PART") "KEMET    C1210C107M9PAC")
      )
      (libsource (lib "Database_Libs1") (part "C"))
    )
    (comp (ref "C406")
      (value "C")
      (footprint "SMD_1210_CAPC3225X270N")
      (fields
        (field (name "DB_PART_NUMBER") "CAP000043701")
        (field (name "DB_VALUE") "100uF")
        (field (name "DB_TOLERANCE") "20%")
        (field (name "DB_VOLTAGE") "6.3V")
        (field (name "DB_MANUFACTURER_PART") "KEMET    C1210C107M9PAC")
      )
      (libsource (lib "Database_Libs1") (part "C"))
    )
    (comp (ref "C407")
      (value "C")
      (footprint "SMD_1210_CAPC3225X270N")
      (fields
        (field (name "DB_PART_NUMBER") "CAP000043701")
        (field (name "DB_VALUE") "100uF")
        (field (name "DB_TOLERANCE") "20%")
        (field (name "DB_VOLTAGE") "6.3V")
        (field (name "DB_MANUFACTURER_PART") "KEMET    C1210C107M9PAC")
      )
      (libsource (lib "Database_Libs1") (part "C"))
    )
    (comp (ref "C408")
      (value "C")
      (footprint "SMD_1210_CAPC3225X279N")
      (fields
        (field (name "DB_PART_NUMBER") "CAP000047355")
        (field (name "DB_VALUE") "220uF")
        (field (name "DB_TOLERANCE") "20%")
        (field (name "DB_VOLTAGE") "6.3V")
        (field (name "DB_MANUFACTURER_PART") "SAMSUNG    CL32A227MQVNNNE")
        (field (name "DB_APPROVED_BY") "VSN")
      )
      (libsource (lib "Database_Libs1") (part "C"))
    )
    (comp (ref "C409")
      (value "C")
      (footprint "SMD_1210_CAPC3225X279N")
      (fields
        (field (name "DB_PART_NUMBER") "CAP000047355")
        (field (name "DB_VALUE") "220uF")
        (field (name "DB_TOLERANCE") "20%")
        (field (name "DB_VOLTAGE") "6.3V")
        (field (name "DB_MANUFACTURER_PART") "SAMSUNG    CL32A227MQVNNNE")
        (field (name "DB_APPROVED_BY") "VSN")
      )
      (libsource (lib "Database_Libs1") (part "C"))
    )
    (comp (ref "C410")
      (value "C")
      (footprint "SMD_1210_CAPC3225X279N")
      (fields
        (field (name "DB_PART_NUMBER") "CAP000047355")
        (field (name "DB_VALUE") "220uF")
        (field (name "DB_TOLERANCE") "20%")
        (field (name "DB_VOLTAGE") "6.3V")
        (field (name "DB_MANUFACTURER_PART") "SAMSUNG    CL32A227MQVNNNE")
        (field (name "DB_APPROVED_BY") "VSN")
      )
      (libsource (lib "Database_Libs1") (part "C"))
    )
    (comp (ref "C411")
      (value "C")
      (footprint "SMD_1210_CAPC3225X279N")
      (fields
        (field (name "DB_PART_NUMBER") "CAP000047355")
        (field (name "DB_VALUE") "220uF")
        (field (name "DB_TOLERANCE") "20%")
        (field (name "DB_VOLTAGE") "6.3V")
        (field (name "DB_MANUFACTURER_PART") "SAMSUNG    CL32A227MQVNNNE")
        (field (name "DB_APPROVED_BY") "VSN")
      )
      (libsource (lib "Database_Libs1") (part "C"))
    )
    (comp (ref "C412")
      (value "C")
      (footprint "SMD_1210_CAPC3225X279N")
      (fields
        (field (name "DB_PART_NUMBER") "CAP000047355")
        (field (name "DB_VALUE") "220uF")
        (field (name "DB_TOLERANCE") "20%")
        (field (name "DB_VOLTAGE") "6.3V")
        (field (name "DB_MANUFACTURER_PART") "SAMSUNG    CL32A227MQVNNNE")
        (field (name "DB_APPROVED_BY") "VSN")
      )
      (libsource (lib "Database_Libs1") (part "C"))
    )
    (comp (ref "C413")
      (value "C")
      (footprint "SMD_1210_CAPC3225X279N")
      (fields
        (field (name "DB_PART_NUMBER") "CAP000047355")
        (field (name "DB_VALUE") "220uF")
        (field (name "DB_TOLERANCE") "20%")
        (field (name "DB_VOLTAGE") "6.3V")
        (field (name "DB_MANUFACTURER_PART") "SAMSUNG    CL32A227MQVNNNE")
        (field (name "DB_APPROVED_BY") "VSN")
      )
      (libsource (lib "Database_Libs1") (part "C"))
    )
    (comp (ref "C414")
      (value "C")
      (footprint "SMD_1210_CAPC3225X279N")
      (fields
        (field (name "DB_PART_NUMBER") "CAP000047355")
        (field (name "DB_VALUE") "220uF")
        (field (name "DB_TOLERANCE") "20%")
        (field (name "DB_VOLTAGE") "6.3V")
        (field (name "DB_MANUFACTURER_PART") "SAMSUNG    CL32A227MQVNNNE")
        (field (name "DB_APPROVED_BY") "VSN")
      )
      (libsource (lib "Database_Libs1") (part "C"))
    )
    (comp (ref "C415")
      (value "C")
      (footprint "SMD_1210_CAPC3225X279N")
      (fields
        (field (name "DB_PART_NUMBER") "CAP000047355")
        (field (name "DB_VALUE") "220uF")
        (field (name "DB_TOLERANCE") "20%")
        (field (name "DB_VOLTAGE") "6.3V")
        (field (name "DB_MANUFACTURER_PART") "SAMSUNG    CL32A227MQVNNNE")
        (field (name "DB_APPROVED_BY") "VSN")
      )
      (libsource (lib "Database_Libs1") (part "C"))
    )
    (comp (ref "C416")
      (value "C")
      (footprint "SMD_1210_CAPC3225X279N")
      (fields
        (field (name "DB_PART_NUMBER") "CAP000047355")
        (field (name "DB_VALUE") "220uF")
        (field (name "DB_TOLERANCE") "20%")
        (field (name "DB_VOLTAGE") "6.3V")
        (field (name "DB_MANUFACTURER_PART") "SAMSUNG    CL32A227MQVNNNE")
        (field (name "DB_APPROVED_BY") "VSN")
      )
      (libsource (lib "Database_Libs1") (part "C"))
    )
    (comp (ref "C417")
      (value "C")
      (footprint "SMD_1210_CAPC3225X279N")
      (fields
        (field (name "DB_PART_NUMBER") "CAP000047355")
        (field (name "DB_VALUE") "220uF")
        (field (name "DB_TOLERANCE") "20%")
        (field (name "DB_VOLTAGE") "6.3V")
        (field (name "DB_MANUFACTURER_PART") "SAMSUNG    CL32A227MQVNNNE")
        (field (name "DB_APPROVED_BY") "VSN")
      )
      (libsource (lib "Database_Libs1") (part "C"))
    )
    (comp (ref "C418")
      (value "C")
      (footprint "SMD_1210_CAPC3225X279N")
      (fields
        (field (name "DB_PART_NUMBER") "CAP000047355")
        (field (name "DB_VALUE") "220uF")
        (field (name "DB_TOLERANCE") "20%")
        (field (name "DB_VOLTAGE") "6.3V")
        (field (name "DB_MANUFACTURER_PART") "SAMSUNG    CL32A227MQVNNNE")
        (field (name "DB_APPROVED_BY") "VSN")
      )
      (libsource (lib "Database_Libs1") (part "C"))
    )
    (comp (ref "C419")
      (value "C")
      (footprint "SMD_1210_CAPC3225X279N")
      (fields
        (field (name "DB_PART_NUMBER") "CAP000047355")
        (field (name "DB_VALUE") "220uF")
        (field (name "DB_TOLERANCE") "20%")
        (field (name "DB_VOLTAGE") "6.3V")
        (field (name "DB_MANUFACTURER_PART") "SAMSUNG    CL32A227MQVNNNE")
        (field (name "DB_APPROVED_BY") "VSN")
      )
      (libsource (lib "Database_Libs1") (part "C"))
    )
    (comp (ref "C420")
      (value "C")
      (footprint "SMD_1210_CAPC3225X270N")
      (fields
        (field (name "DB_PART_NUMBER") "CAP000043701")
        (field (name "DB_VALUE") "100uF")
        (field (name "DB_TOLERANCE") "20%")
        (field (name "DB_VOLTAGE") "6.3V")
        (field (name "DB_MANUFACTURER_PART") "KEMET    C1210C107M9PAC")
      )
      (libsource (lib "Database_Libs1") (part "C"))
    )
    (comp (ref "C421")
      (value "C")
      (footprint "SMD_1210_CAPC3225X270N")
      (fields
        (field (name "DB_PART_NUMBER") "CAP000043701")
        (field (name "DB_VALUE") "100uF")
        (field (name "DB_TOLERANCE") "20%")
        (field (name "DB_VOLTAGE") "6.3V")
        (field (name "DB_MANUFACTURER_PART") "KEMET    C1210C107M9PAC")
      )
      (libsource (lib "Database_Libs1") (part "C"))
    )
    (comp (ref "C422")
      (value "C")
      (footprint "SMD_1210_CAPC3225X270N")
      (fields
        (field (name "DB_PART_NUMBER") "CAP000043701")
        (field (name "DB_VALUE") "100uF")
        (field (name "DB_TOLERANCE") "20%")
        (field (name "DB_VOLTAGE") "6.3V")
        (field (name "DB_MANUFACTURER_PART") "KEMET    C1210C107M9PAC")
      )
      (libsource (lib "Database_Libs1") (part "C"))
    )
    (comp (ref "C423")
      (value "C")
      (footprint "SMD_1210_CAPC3225X270N")
      (fields
        (field (name "DB_PART_NUMBER") "CAP000043701")
        (field (name "DB_VALUE") "100uF")
        (field (name "DB_TOLERANCE") "20%")
        (field (name "DB_VOLTAGE") "6.3V")
        (field (name "DB_MANUFACTURER_PART") "KEMET    C1210C107M9PAC")
      )
      (libsource (lib "Database_Libs1") (part "C"))
    )
    (comp (ref "C424")
      (value "C")
      (footprint "SMD_1210_CAPC3225X270N")
      (fields
        (field (name "DB_PART_NUMBER") "CAP000043701")
        (field (name "DB_VALUE") "100uF")
        (field (name "DB_TOLERANCE") "20%")
        (field (name "DB_VOLTAGE") "6.3V")
        (field (name "DB_MANUFACTURER_PART") "KEMET    C1210C107M9PAC")
      )
      (libsource (lib "Database_Libs1") (part "C"))
    )
    (comp (ref "C425")
      (value "C")
      (footprint "SMD_1210_CAPC3225X270N")
      (fields
        (field (name "DB_PART_NUMBER") "CAP000043701")
        (field (name "DB_VALUE") "100uF")
        (field (name "DB_TOLERANCE") "20%")
        (field (name "DB_VOLTAGE") "6.3V")
        (field (name "DB_MANUFACTURER_PART") "KEMET    C1210C107M9PAC")
      )
      (libsource (lib "Database_Libs1") (part "C"))
    )
    (comp (ref "C426")
      (value "C")
      (footprint "SMD_1210_CAPC3225X270N")
      (fields
        (field (name "DB_PART_NUMBER") "CAP000043701")
        (field (name "DB_VALUE") "100uF")
        (field (name "DB_TOLERANCE") "20%")
        (field (name "DB_VOLTAGE") "6.3V")
        (field (name "DB_MANUFACTURER_PART") "KEMET    C1210C107M9PAC")
      )
      (libsource (lib "Database_Libs1") (part "C"))
    )
    (comp (ref "C427")
      (value "C")
      (footprint "SMD_1210_CAPC3225X270N")
      (fields
        (field (name "DB_PART_NUMBER") "CAP000043701")
        (field (name "DB_VALUE") "100uF")
        (field (name "DB_TOLERANCE") "20%")
        (field (name "DB_VOLTAGE") "6.3V")
        (field (name "DB_MANUFACTURER_PART") "KEMET    C1210C107M9PAC")
      )
      (libsource (lib "Database_Libs1") (part "C"))
    )
    (comp (ref "D10")
      (value "D")
      (footprint "SMD_SOD523_SOD1608X65N")
      (fields
        (field (name "DB_PART_NUMBER") "DDE000001203")
        (field (name "DB_VALUE") "1N4448HWT")
        (field (name "DB_MANUFACTURER_PART") "Diodes        1N4448HWT")
      )
      (libsource (lib "Database_Libs1") (part "D"))
    )
    (comp (ref "D11")
      (value "D")
      (footprint "SMD_SOD523_SOD1608X65N")
      (fields
        (field (name "DB_PART_NUMBER") "DDE000001203")
        (field (name "DB_VALUE") "1N4448HWT")
        (field (name "DB_MANUFACTURER_PART") "Diodes        1N4448HWT")
      )
      (libsource (lib "Database_Libs1") (part "D"))
    )
    (comp (ref "D12")
      (value "D")
      (footprint "SMD_SOD523_SOD1608X65N")
      (fields
        (field (name "DB_PART_NUMBER") "DDE000001203")
        (field (name "DB_VALUE") "1N4448HWT")
        (field (name "DB_MANUFACTURER_PART") "Diodes        1N4448HWT")
      )
      (libsource (lib "Database_Libs1") (part "D"))
    )
    (comp (ref "D13")
      (value "D")
      (footprint "SMD_SOD523_SOD1608X65N")
      (fields
        (field (name "DB_PART_NUMBER") "DDE000001203")
        (field (name "DB_VALUE") "1N4448HWT")
        (field (name "DB_MANUFACTURER_PART") "Diodes        1N4448HWT")
      )
      (libsource (lib "Database_Libs1") (part "D"))
    )
    (comp (ref "D14")
      (value "D")
      (footprint "SMD_SOD523_SOD1608X65N")
      (fields
        (field (name "DB_PART_NUMBER") "DDE000001203")
        (field (name "DB_VALUE") "1N4448HWT")
        (field (name "DB_MANUFACTURER_PART") "Diodes        1N4448HWT")
      )
      (libsource (lib "Database_Libs1") (part "D"))
    )
    (comp (ref "D15")
      (value "D")
      (footprint "SMD_SOD523_SOD1608X65N")
      (fields
        (field (name "DB_PART_NUMBER") "DDE000001203")
        (field (name "DB_VALUE") "1N4448HWT")
        (field (name "DB_MANUFACTURER_PART") "Diodes        1N4448HWT")
      )
      (libsource (lib "Database_Libs1") (part "D"))
    )
    (comp (ref "D16")
      (value "D")
      (footprint "SMD_SOD523_SOD1608X65N")
      (fields
        (field (name "DB_PART_NUMBER") "DDE000001203")
        (field (name "DB_VALUE") "1N4448HWT")
        (field (name "DB_MANUFACTURER_PART") "Diodes        1N4448HWT")
      )
      (libsource (lib "Database_Libs1") (part "D"))
    )
    (comp (ref "D17")
      (value "D")
      (footprint "SMD_SOD523_SOD1608X65N")
      (fields
        (field (name "DB_PART_NUMBER") "DDE000001203")
        (field (name "DB_VALUE") "1N4448HWT")
        (field (name "DB_MANUFACTURER_PART") "Diodes        1N4448HWT")
      )
      (libsource (lib "Database_Libs1") (part "D"))
    )
    (comp (ref "D18")
      (value "D")
      (footprint "SMD_SOD523_SOD1608X65N")
      (fields
        (field (name "DB_PART_NUMBER") "DDE000001203")
        (field (name "DB_VALUE") "1N4448HWT")
        (field (name "DB_MANUFACTURER_PART") "Diodes        1N4448HWT")
      )
      (libsource (lib "Database_Libs1") (part "D"))
    )
    (comp (ref "D19")
      (value "D")
      (footprint "SMD_SOD523_SOD1608X65N")
      (fields
        (field (name "DB_PART_NUMBER") "DDE000001203")
        (field (name "DB_VALUE") "1N4448HWT")
        (field (name "DB_MANUFACTURER_PART") "Diodes        1N4448HWT")
      )
      (libsource (lib "Database_Libs1") (part "D"))
    )
    (comp (ref "D20")
      (value "D")
      (footprint "SMD_SOD523_SOD1608X65N")
      (fields
        (field (name "DB_PART_NUMBER") "DDE000001203")
        (field (name "DB_VALUE") "1N4448HWT")
        (field (name "DB_MANUFACTURER_PART") "Diodes        1N4448HWT")
      )
      (libsource (lib "Database_Libs1") (part "D"))
    )
    (comp (ref "D21")
      (value "D")
      (footprint "SMD_SOD523_SOD1608X65N")
      (fields
        (field (name "DB_PART_NUMBER") "DDE000001203")
        (field (name "DB_VALUE") "1N4448HWT")
        (field (name "DB_MANUFACTURER_PART") "Diodes        1N4448HWT")
      )
      (libsource (lib "Database_Libs1") (part "D"))
    )
    (comp (ref "D22")
      (value "D")
      (footprint "SMD_SOD523_SOD1608X65N")
      (fields
        (field (name "DB_PART_NUMBER") "DDE000001203")
        (field (name "DB_VALUE") "1N4448HWT")
        (field (name "DB_MANUFACTURER_PART") "Diodes        1N4448HWT")
      )
      (libsource (lib "Database_Libs1") (part "D"))
    )
    (comp (ref "D23")
      (value "D")
      (footprint "SMD_SOD523_SOD1608X65N")
      (fields
        (field (name "DB_PART_NUMBER") "DDE000001203")
        (field (name "DB_VALUE") "1N4448HWT")
        (field (name "DB_MANUFACTURER_PART") "Diodes        1N4448HWT")
      )
      (libsource (lib "Database_Libs1") (part "D"))
    )
    (comp (ref "D24")
      (value "D")
      (footprint "SMD_SOD523_SOD1608X65N")
      (fields
        (field (name "DB_PART_NUMBER") "DDE000001203")
        (field (name "DB_VALUE") "1N4448HWT")
        (field (name "DB_MANUFACTURER_PART") "Diodes        1N4448HWT")
      )
      (libsource (lib "Database_Libs1") (part "D"))
    )
    (comp (ref "D25")
      (value "D")
      (footprint "SMD_SOD523_SOD1608X65N")
      (fields
        (field (name "DB_PART_NUMBER") "DDE000001203")
        (field (name "DB_VALUE") "1N4448HWT")
        (field (name "DB_MANUFACTURER_PART") "Diodes        1N4448HWT")
      )
      (libsource (lib "Database_Libs1") (part "D"))
    )
    (comp (ref "L1")
      (value "SLC1480-201MLD")
      (footprint "SMT_INDM135130X800N")
      (libsource (lib "EPIQ_DND_CIS_Library") (part "L"))
    )
    (comp (ref "L2")
      (value "SLC1480-201MLD")
      (footprint "SMT_INDM135130X800N")
      (libsource (lib "EPIQ_DND_CIS_Library") (part "L"))
    )
    (comp (ref "L3")
      (value "SLC1480-201MLD")
      (footprint "SMT_INDM135130X800N")
      (libsource (lib "EPIQ_DND_CIS_Library") (part "L"))
    )
    (comp (ref "L4")
      (value "SLC1480-201MLD")
      (footprint "SMT_INDM135130X800N")
      (libsource (lib "EPIQ_DND_CIS_Library") (part "L"))
    )
    (comp (ref "L5")
      (value "SLC1480-201MLD")
      (footprint "SMT_INDM135130X800N")
      (libsource (lib "EPIQ_DND_CIS_Library") (part "L"))
    )
    (comp (ref "L6")
      (value "SLC1480-201MLD")
      (footprint "SMT_INDM135130X800N")
      (libsource (lib "EPIQ_DND_CIS_Library") (part "L"))
    )
    (comp (ref "L7")
      (value "SLC1480-201MLD")
      (footprint "SMT_INDM135130X800N")
      (libsource (lib "EPIQ_DND_CIS_Library") (part "L"))
    )
    (comp (ref "L8")
      (value "SLC1480-201MLD")
      (footprint "SMT_INDM135130X800N")
      (libsource (lib "EPIQ_DND_CIS_Library") (part "L"))
    )
    (comp (ref "L9")
      (value "SLC1480-201MLD")
      (footprint "SMT_INDM135130X800N")
      (libsource (lib "EPIQ_DND_CIS_Library") (part "L"))
    )
    (comp (ref "L10")
      (value "SLC1480-201MLD")
      (footprint "SMT_INDM135130X800N")
      (libsource (lib "EPIQ_DND_CIS_Library") (part "L"))
    )
    (comp (ref "L11")
      (value "SLC1480-201MLD")
      (footprint "SMT_INDM135130X800N")
      (libsource (lib "EPIQ_DND_CIS_Library") (part "L"))
    )
    (comp (ref "L12")
      (value "SLC1480-201MLD")
      (footprint "SMT_INDM135130X800N")
      (libsource (lib "EPIQ_DND_CIS_Library") (part "L"))
    )
    (comp (ref "L13")
      (value "SLC1480-201MLD")
      (footprint "SMT_INDM135130X800N")
      (libsource (lib "EPIQ_DND_CIS_Library") (part "L"))
    )
    (comp (ref "L14")
      (value "SLC1480-201MLD")
      (footprint "SMT_INDM135130X800N")
      (libsource (lib "EPIQ_DND_CIS_Library") (part "L"))
    )
    (comp (ref "L15")
      (value "SLC1480-201MLD")
      (footprint "SMT_INDM135130X800N")
      (libsource (lib "EPIQ_DND_CIS_Library") (part "L"))
    )
    (comp (ref "L16")
      (value "SLC1480-201MLD")
      (footprint "SMT_INDM135130X800N")
      (libsource (lib "EPIQ_DND_CIS_Library") (part "L"))
    )
    (comp (ref "Q1")
      (value "MOS_N_D1_S1S2S3G4D5D6D7D8")
      (footprint "SMD_SOIC127P600X110-9AN")
      (fields
        (field (name "DB_PART_NUMBER") "TRA000001604")
        (field (name "DB_VALUE") "AP1RA03GMT-HF-3")
        (field (name "DB_MANUFACTURER_PART") "ADVANCED POWER ELECTRONICS CORP      AP1RA03GMT-HF-3")
        (field (name "DB_APPROVED_BY") "VSN")
      )
      (libsource (lib "Database_Libs1") (part "MOS_N_D1_S1S2S3G4D5D6D7D8"))
    )
    (comp (ref "Q2")
      (value "MOS_N_D1_S1S2S3G4D5D6D7D8")
      (footprint "SMD_SOIC127P600X110-9AN")
      (fields
        (field (name "DB_PART_NUMBER") "TRA000001604")
        (field (name "DB_VALUE") "AP1RA03GMT-HF-3")
        (field (name "DB_MANUFACTURER_PART") "ADVANCED POWER ELECTRONICS CORP      AP1RA03GMT-HF-3")
        (field (name "DB_APPROVED_BY") "VSN")
      )
      (libsource (lib "Database_Libs1") (part "MOS_N_D1_S1S2S3G4D5D6D7D8"))
    )
    (comp (ref "Q3")
      (value "MOS_N_D1_S1S2S3G4D5D6D7D8")
      (footprint "SMD_SOIC127P600X110-9AN")
      (fields
        (field (name "DB_PART_NUMBER") "TRA000001604")
        (field (name "DB_VALUE") "AP1RA03GMT-HF-3")
        (field (name "DB_MANUFACTURER_PART") "ADVANCED POWER ELECTRONICS CORP      AP1RA03GMT-HF-3")
        (field (name "DB_APPROVED_BY") "VSN")
      )
      (libsource (lib "Database_Libs1") (part "MOS_N_D1_S1S2S3G4D5D6D7D8"))
    )
    (comp (ref "Q4")
      (value "MOS_N_D1_S1S2S3G4D5D6D7D8")
      (footprint "SMD_SOIC127P600X110-9AN")
      (fields
        (field (name "DB_PART_NUMBER") "TRA000001604")
        (field (name "DB_VALUE") "AP1RA03GMT-HF-3")
        (field (name "DB_MANUFACTURER_PART") "ADVANCED POWER ELECTRONICS CORP      AP1RA03GMT-HF-3")
        (field (name "DB_APPROVED_BY") "VSN")
      )
      (libsource (lib "Database_Libs1") (part "MOS_N_D1_S1S2S3G4D5D6D7D8"))
    )
    (comp (ref "Q5")
      (value "MOS_N_D1_S1S2S3G4D5D6D7D8")
      (footprint "SMD_SOIC127P600X110-9AN")
      (fields
        (field (name "DB_PART_NUMBER") "TRA000001604")
        (field (name "DB_VALUE") "AP1RA03GMT-HF-3")
        (field (name "DB_MANUFACTURER_PART") "ADVANCED POWER ELECTRONICS CORP      AP1RA03GMT-HF-3")
        (field (name "DB_APPROVED_BY") "VSN")
      )
      (libsource (lib "Database_Libs1") (part "MOS_N_D1_S1S2S3G4D5D6D7D8"))
    )
    (comp (ref "Q6")
      (value "MOS_N_D1_S1S2S3G4D5D6D7D8")
      (footprint "SMD_SOIC127P600X110-9AN")
      (fields
        (field (name "DB_PART_NUMBER") "TRA000001604")
        (field (name "DB_VALUE") "AP1RA03GMT-HF-3")
        (field (name "DB_MANUFACTURER_PART") "ADVANCED POWER ELECTRONICS CORP      AP1RA03GMT-HF-3")
        (field (name "DB_APPROVED_BY") "VSN")
      )
      (libsource (lib "Database_Libs1") (part "MOS_N_D1_S1S2S3G4D5D6D7D8"))
    )
    (comp (ref "Q7")
      (value "MOS_N_D1_S1S2S3G4D5D6D7D8")
      (footprint "SMD_SOIC127P600X110-9AN")
      (fields
        (field (name "DB_PART_NUMBER") "TRA000001604")
        (field (name "DB_VALUE") "AP1RA03GMT-HF-3")
        (field (name "DB_MANUFACTURER_PART") "ADVANCED POWER ELECTRONICS CORP      AP1RA03GMT-HF-3")
        (field (name "DB_APPROVED_BY") "VSN")
      )
      (libsource (lib "Database_Libs1") (part "MOS_N_D1_S1S2S3G4D5D6D7D8"))
    )
    (comp (ref "Q8")
      (value "MOS_N_D1_S1S2S3G4D5D6D7D8")
      (footprint "SMD_SOIC127P600X110-9AN")
      (fields
        (field (name "DB_PART_NUMBER") "TRA000001604")
        (field (name "DB_VALUE") "AP1RA03GMT-HF-3")
        (field (name "DB_MANUFACTURER_PART") "ADVANCED POWER ELECTRONICS CORP      AP1RA03GMT-HF-3")
        (field (name "DB_APPROVED_BY") "VSN")
      )
      (libsource (lib "Database_Libs1") (part "MOS_N_D1_S1S2S3G4D5D6D7D8"))
    )
    (comp (ref "Q9")
      (value "MOS_N_D1_S1S2S3G4D5D6D7D8")
      (footprint "SMD_SOIC127P600X110-9AN")
      (fields
        (field (name "DB_PART_NUMBER") "TRA000001604")
        (field (name "DB_VALUE") "AP1RA03GMT-HF-3")
        (field (name "DB_MANUFACTURER_PART") "ADVANCED POWER ELECTRONICS CORP      AP1RA03GMT-HF-3")
        (field (name "DB_APPROVED_BY") "VSN")
      )
      (libsource (lib "Database_Libs1") (part "MOS_N_D1_S1S2S3G4D5D6D7D8"))
    )
    (comp (ref "Q10")
      (value "MOS_N_D1_S1S2S3G4D5D6D7D8")
      (footprint "SMD_SOIC127P600X110-9AN")
      (fields
        (field (name "DB_PART_NUMBER") "TRA000001604")
        (field (name "DB_VALUE") "AP1RA03GMT-HF-3")
        (field (name "DB_MANUFACTURER_PART") "ADVANCED POWER ELECTRONICS CORP      AP1RA03GMT-HF-3")
        (field (name "DB_APPROVED_BY") "VSN")
      )
      (libsource (lib "Database_Libs1") (part "MOS_N_D1_S1S2S3G4D5D6D7D8"))
    )
    (comp (ref "Q11")
      (value "MOS_N_D1_S1S2S3G4D5D6D7D8")
      (footprint "SMD_SOIC127P600X110-9AN")
      (fields
        (field (name "DB_PART_NUMBER") "TRA000001604")
        (field (name "DB_VALUE") "AP1RA03GMT-HF-3")
        (field (name "DB_MANUFACTURER_PART") "ADVANCED POWER ELECTRONICS CORP      AP1RA03GMT-HF-3")
        (field (name "DB_APPROVED_BY") "VSN")
      )
      (libsource (lib "Database_Libs1") (part "MOS_N_D1_S1S2S3G4D5D6D7D8"))
    )
    (comp (ref "Q12")
      (value "MOS_N_D1_S1S2S3G4D5D6D7D8")
      (footprint "SMD_SOIC127P600X110-9AN")
      (fields
        (field (name "DB_PART_NUMBER") "TRA000001604")
        (field (name "DB_VALUE") "AP1RA03GMT-HF-3")
        (field (name "DB_MANUFACTURER_PART") "ADVANCED POWER ELECTRONICS CORP      AP1RA03GMT-HF-3")
        (field (name "DB_APPROVED_BY") "VSN")
      )
      (libsource (lib "Database_Libs1") (part "MOS_N_D1_S1S2S3G4D5D6D7D8"))
    )
    (comp (ref "Q13")
      (value "MOS_N_D1_S1S2S3G4D5D6D7D8")
      (footprint "SMD_SOIC127P600X110-9AN")
      (fields
        (field (name "DB_PART_NUMBER") "TRA000001604")
        (field (name "DB_VALUE") "AP1RA03GMT-HF-3")
        (field (name "DB_MANUFACTURER_PART") "ADVANCED POWER ELECTRONICS CORP      AP1RA03GMT-HF-3")
        (field (name "DB_APPROVED_BY") "VSN")
      )
      (libsource (lib "Database_Libs1") (part "MOS_N_D1_S1S2S3G4D5D6D7D8"))
    )
    (comp (ref "Q14")
      (value "MOS_N_D1_S1S2S3G4D5D6D7D8")
      (footprint "SMD_SOIC127P600X110-9AN")
      (fields
        (field (name "DB_PART_NUMBER") "TRA000001604")
        (field (name "DB_VALUE") "AP1RA03GMT-HF-3")
        (field (name "DB_MANUFACTURER_PART") "ADVANCED POWER ELECTRONICS CORP      AP1RA03GMT-HF-3")
        (field (name "DB_APPROVED_BY") "VSN")
      )
      (libsource (lib "Database_Libs1") (part "MOS_N_D1_S1S2S3G4D5D6D7D8"))
    )
    (comp (ref "Q15")
      (value "MOS_N_D1_S1S2S3G4D5D6D7D8")
      (footprint "SMD_SOIC127P600X110-9AN")
      (fields
        (field (name "DB_PART_NUMBER") "TRA000001604")
        (field (name "DB_VALUE") "AP1RA03GMT-HF-3")
        (field (name "DB_MANUFACTURER_PART") "ADVANCED POWER ELECTRONICS CORP      AP1RA03GMT-HF-3")
        (field (name "DB_APPROVED_BY") "VSN")
      )
      (libsource (lib "Database_Libs1") (part "MOS_N_D1_S1S2S3G4D5D6D7D8"))
    )
    (comp (ref "Q16")
      (value "MOS_N_D1_S1S2S3G4D5D6D7D8")
      (footprint "SMD_SOIC127P600X110-9AN")
      (fields
        (field (name "DB_PART_NUMBER") "TRA000001604")
        (field (name "DB_VALUE") "AP1RA03GMT-HF-3")
        (field (name "DB_MANUFACTURER_PART") "ADVANCED POWER ELECTRONICS CORP      AP1RA03GMT-HF-3")
        (field (name "DB_APPROVED_BY") "VSN")
      )
      (libsource (lib "Database_Libs1") (part "MOS_N_D1_S1S2S3G4D5D6D7D8"))
    )
    (comp (ref "Q17")
      (value "MOS_N_D1_S1S2S3G4D5D6D7D8")
      (footprint "SMD_SOIC127P600X110-9AN")
      (fields
        (field (name "DB_PART_NUMBER") "TRA000001604")
        (field (name "DB_VALUE") "AP1RA03GMT-HF-3")
        (field (name "DB_MANUFACTURER_PART") "ADVANCED POWER ELECTRONICS CORP      AP1RA03GMT-HF-3")
        (field (name "DB_APPROVED_BY") "VSN")
      )
      (libsource (lib "Database_Libs1") (part "MOS_N_D1_S1S2S3G4D5D6D7D8"))
    )
    (comp (ref "Q18")
      (value "MOS_N_D1_S1S2S3G4D5D6D7D8")
      (footprint "SMD_SOIC127P600X110-9AN")
      (fields
        (field (name "DB_PART_NUMBER") "TRA000001604")
        (field (name "DB_VALUE") "AP1RA03GMT-HF-3")
        (field (name "DB_MANUFACTURER_PART") "ADVANCED POWER ELECTRONICS CORP      AP1RA03GMT-HF-3")
        (field (name "DB_APPROVED_BY") "VSN")
      )
      (libsource (lib "Database_Libs1") (part "MOS_N_D1_S1S2S3G4D5D6D7D8"))
    )
    (comp (ref "Q19")
      (value "MOS_N_D1_S1S2S3G4D5D6D7D8")
      (footprint "SMD_SOIC127P600X110-9AN")
      (fields
        (field (name "DB_PART_NUMBER") "TRA000001604")
        (field (name "DB_VALUE") "AP1RA03GMT-HF-3")
        (field (name "DB_MANUFACTURER_PART") "ADVANCED POWER ELECTRONICS CORP      AP1RA03GMT-HF-3")
        (field (name "DB_APPROVED_BY") "VSN")
      )
      (libsource (lib "Database_Libs1") (part "MOS_N_D1_S1S2S3G4D5D6D7D8"))
    )
    (comp (ref "Q20")
      (value "MOS_N_D1_S1S2S3G4D5D6D7D8")
      (footprint "SMD_SOIC127P600X110-9AN")
      (fields
        (field (name "DB_PART_NUMBER") "TRA000001604")
        (field (name "DB_VALUE") "AP1RA03GMT-HF-3")
        (field (name "DB_MANUFACTURER_PART") "ADVANCED POWER ELECTRONICS CORP      AP1RA03GMT-HF-3")
        (field (name "DB_APPROVED_BY") "VSN")
      )
      (libsource (lib "Database_Libs1") (part "MOS_N_D1_S1S2S3G4D5D6D7D8"))
    )
    (comp (ref "Q21")
      (value "MOS_N_D1_S1S2S3G4D5D6D7D8")
      (footprint "SMD_SOIC127P600X110-9AN")
      (fields
        (field (name "DB_PART_NUMBER") "TRA000001604")
        (field (name "DB_VALUE") "AP1RA03GMT-HF-3")
        (field (name "DB_MANUFACTURER_PART") "ADVANCED POWER ELECTRONICS CORP      AP1RA03GMT-HF-3")
        (field (name "DB_APPROVED_BY") "VSN")
      )
      (libsource (lib "Database_Libs1") (part "MOS_N_D1_S1S2S3G4D5D6D7D8"))
    )
    (comp (ref "Q22")
      (value "MOS_N_D1_S1S2S3G4D5D6D7D8")
      (footprint "SMD_SOIC127P600X110-9AN")
      (fields
        (field (name "DB_PART_NUMBER") "TRA000001604")
        (field (name "DB_VALUE") "AP1RA03GMT-HF-3")
        (field (name "DB_MANUFACTURER_PART") "ADVANCED POWER ELECTRONICS CORP      AP1RA03GMT-HF-3")
        (field (name "DB_APPROVED_BY") "VSN")
      )
      (libsource (lib "Database_Libs1") (part "MOS_N_D1_S1S2S3G4D5D6D7D8"))
    )
    (comp (ref "Q23")
      (value "MOS_N_D1_S1S2S3G4D5D6D7D8")
      (footprint "SMD_SOIC127P600X110-9AN")
      (fields
        (field (name "DB_PART_NUMBER") "TRA000001604")
        (field (name "DB_VALUE") "AP1RA03GMT-HF-3")
        (field (name "DB_MANUFACTURER_PART") "ADVANCED POWER ELECTRONICS CORP      AP1RA03GMT-HF-3")
        (field (name "DB_APPROVED_BY") "VSN")
      )
      (libsource (lib "Database_Libs1") (part "MOS_N_D1_S1S2S3G4D5D6D7D8"))
    )
    (comp (ref "Q24")
      (value "MOS_N_D1_S1S2S3G4D5D6D7D8")
      (footprint "SMD_SOIC127P600X110-9AN")
      (fields
        (field (name "DB_PART_NUMBER") "TRA000001604")
        (field (name "DB_VALUE") "AP1RA03GMT-HF-3")
        (field (name "DB_MANUFACTURER_PART") "ADVANCED POWER ELECTRONICS CORP      AP1RA03GMT-HF-3")
        (field (name "DB_APPROVED_BY") "VSN")
      )
      (libsource (lib "Database_Libs1") (part "MOS_N_D1_S1S2S3G4D5D6D7D8"))
    )
    (comp (ref "Q25")
      (value "MOS_N_D1_S1S2S3G4D5D6D7D8")
      (footprint "SMD_SOIC127P600X110-9AN")
      (fields
        (field (name "DB_PART_NUMBER") "TRA000001604")
        (field (name "DB_VALUE") "AP1RA03GMT-HF-3")
        (field (name "DB_MANUFACTURER_PART") "ADVANCED POWER ELECTRONICS CORP      AP1RA03GMT-HF-3")
        (field (name "DB_APPROVED_BY") "VSN")
      )
      (libsource (lib "Database_Libs1") (part "MOS_N_D1_S1S2S3G4D5D6D7D8"))
    )
    (comp (ref "Q26")
      (value "MOS_N_D1_S1S2S3G4D5D6D7D8")
      (footprint "SMD_SOIC127P600X110-9AN")
      (fields
        (field (name "DB_PART_NUMBER") "TRA000001604")
        (field (name "DB_VALUE") "AP1RA03GMT-HF-3")
        (field (name "DB_MANUFACTURER_PART") "ADVANCED POWER ELECTRONICS CORP      AP1RA03GMT-HF-3")
        (field (name "DB_APPROVED_BY") "VSN")
      )
      (libsource (lib "Database_Libs1") (part "MOS_N_D1_S1S2S3G4D5D6D7D8"))
    )
    (comp (ref "Q27")
      (value "MOS_N_D1_S1S2S3G4D5D6D7D8")
      (footprint "SMD_SOIC127P600X110-9AN")
      (fields
        (field (name "DB_PART_NUMBER") "TRA000001604")
        (field (name "DB_VALUE") "AP1RA03GMT-HF-3")
        (field (name "DB_MANUFACTURER_PART") "ADVANCED POWER ELECTRONICS CORP      AP1RA03GMT-HF-3")
        (field (name "DB_APPROVED_BY") "VSN")
      )
      (libsource (lib "Database_Libs1") (part "MOS_N_D1_S1S2S3G4D5D6D7D8"))
    )
    (comp (ref "Q28")
      (value "MOS_N_D1_S1S2S3G4D5D6D7D8")
      (footprint "SMD_SOIC127P600X110-9AN")
      (fields
        (field (name "DB_PART_NUMBER") "TRA000001604")
        (field (name "DB_VALUE") "AP1RA03GMT-HF-3")
        (field (name "DB_MANUFACTURER_PART") "ADVANCED POWER ELECTRONICS CORP      AP1RA03GMT-HF-3")
        (field (name "DB_APPROVED_BY") "VSN")
      )
      (libsource (lib "Database_Libs1") (part "MOS_N_D1_S1S2S3G4D5D6D7D8"))
    )
    (comp (ref "Q29")
      (value "MOS_N_D1_S1S2S3G4D5D6D7D8")
      (footprint "SMD_SOIC127P600X110-9AN")
      (fields
        (field (name "DB_PART_NUMBER") "TRA000001604")
        (field (name "DB_VALUE") "AP1RA03GMT-HF-3")
        (field (name "DB_MANUFACTURER_PART") "ADVANCED POWER ELECTRONICS CORP      AP1RA03GMT-HF-3")
        (field (name "DB_APPROVED_BY") "VSN")
      )
      (libsource (lib "Database_Libs1") (part "MOS_N_D1_S1S2S3G4D5D6D7D8"))
    )
    (comp (ref "Q30")
      (value "MOS_N_D1_S1S2S3G4D5D6D7D8")
      (footprint "SMD_SOIC127P600X110-9AN")
      (fields
        (field (name "DB_PART_NUMBER") "TRA000001604")
        (field (name "DB_VALUE") "AP1RA03GMT-HF-3")
        (field (name "DB_MANUFACTURER_PART") "ADVANCED POWER ELECTRONICS CORP      AP1RA03GMT-HF-3")
        (field (name "DB_APPROVED_BY") "VSN")
      )
      (libsource (lib "Database_Libs1") (part "MOS_N_D1_S1S2S3G4D5D6D7D8"))
    )
    (comp (ref "Q31")
      (value "MOS_N_D1_S1S2S3G4D5D6D7D8")
      (footprint "SMD_SOIC127P600X110-9AN")
      (fields
        (field (name "DB_PART_NUMBER") "TRA000001604")
        (field (name "DB_VALUE") "AP1RA03GMT-HF-3")
        (field (name "DB_MANUFACTURER_PART") "ADVANCED POWER ELECTRONICS CORP      AP1RA03GMT-HF-3")
        (field (name "DB_APPROVED_BY") "VSN")
      )
      (libsource (lib "Database_Libs1") (part "MOS_N_D1_S1S2S3G4D5D6D7D8"))
    )
    (comp (ref "Q32")
      (value "MOS_N_D1_S1S2S3G4D5D6D7D8")
      (footprint "SMD_SOIC127P600X110-9AN")
      (fields
        (field (name "DB_PART_NUMBER") "TRA000001604")
        (field (name "DB_VALUE") "AP1RA03GMT-HF-3")
        (field (name "DB_MANUFACTURER_PART") "ADVANCED POWER ELECTRONICS CORP      AP1RA03GMT-HF-3")
        (field (name "DB_APPROVED_BY") "VSN")
      )
      (libsource (lib "Database_Libs1") (part "MOS_N_D1_S1S2S3G4D5D6D7D8"))
    )
    (comp (ref "Q33")
      (value "MOS_N_D1_S1S2S3G4D5D6D7D8")
      (footprint "SMD_SOIC127P600X110-9AN")
      (fields
        (field (name "DB_PART_NUMBER") "TRA000001604")
        (field (name "DB_VALUE") "AP1RA03GMT-HF-3")
        (field (name "DB_MANUFACTURER_PART") "ADVANCED POWER ELECTRONICS CORP      AP1RA03GMT-HF-3")
        (field (name "DB_APPROVED_BY") "VSN")
      )
      (libsource (lib "Database_Libs1") (part "MOS_N_D1_S1S2S3G4D5D6D7D8"))
    )
    (comp (ref "Q34")
      (value "MOS_N_D1_S1S2S3G4D5D6D7D8")
      (footprint "SMD_SOIC127P600X110-9AN")
      (fields
        (field (name "DB_PART_NUMBER") "TRA000001604")
        (field (name "DB_VALUE") "AP1RA03GMT-HF-3")
        (field (name "DB_MANUFACTURER_PART") "ADVANCED POWER ELECTRONICS CORP      AP1RA03GMT-HF-3")
        (field (name "DB_APPROVED_BY") "VSN")
      )
      (libsource (lib "Database_Libs1") (part "MOS_N_D1_S1S2S3G4D5D6D7D8"))
    )
    (comp (ref "Q35")
      (value "MOS_N_D1_S1S2S3G4D5D6D7D8")
      (footprint "SMD_SOIC127P600X110-9AN")
      (fields
        (field (name "DB_PART_NUMBER") "TRA000001604")
        (field (name "DB_VALUE") "AP1RA03GMT-HF-3")
        (field (name "DB_MANUFACTURER_PART") "ADVANCED POWER ELECTRONICS CORP      AP1RA03GMT-HF-3")
        (field (name "DB_APPROVED_BY") "VSN")
      )
      (libsource (lib "Database_Libs1") (part "MOS_N_D1_S1S2S3G4D5D6D7D8"))
    )
    (comp (ref "Q36")
      (value "MOS_N_D1_S1S2S3G4D5D6D7D8")
      (footprint "SMD_SOIC127P600X110-9AN")
      (fields
        (field (name "DB_PART_NUMBER") "TRA000001604")
        (field (name "DB_VALUE") "AP1RA03GMT-HF-3")
        (field (name "DB_MANUFACTURER_PART") "ADVANCED POWER ELECTRONICS CORP      AP1RA03GMT-HF-3")
        (field (name "DB_APPROVED_BY") "VSN")
      )
      (libsource (lib "Database_Libs1") (part "MOS_N_D1_S1S2S3G4D5D6D7D8"))
    )
    (comp (ref "Q37")
      (value "MOS_N_D1_S1S2S3G4D5D6D7D8")
      (footprint "SMD_SOIC127P600X110-9AN")
      (fields
        (field (name "DB_PART_NUMBER") "TRA000001604")
        (field (name "DB_VALUE") "AP1RA03GMT-HF-3")
        (field (name "DB_MANUFACTURER_PART") "ADVANCED POWER ELECTRONICS CORP      AP1RA03GMT-HF-3")
        (field (name "DB_APPROVED_BY") "VSN")
      )
      (libsource (lib "Database_Libs1") (part "MOS_N_D1_S1S2S3G4D5D6D7D8"))
    )
    (comp (ref "Q38")
      (value "MOS_N_D1_S1S2S3G4D5D6D7D8")
      (footprint "SMD_SOIC127P600X110-9AN")
      (fields
        (field (name "DB_PART_NUMBER") "TRA000001604")
        (field (name "DB_VALUE") "AP1RA03GMT-HF-3")
        (field (name "DB_MANUFACTURER_PART") "ADVANCED POWER ELECTRONICS CORP      AP1RA03GMT-HF-3")
        (field (name "DB_APPROVED_BY") "VSN")
      )
      (libsource (lib "Database_Libs1") (part "MOS_N_D1_S1S2S3G4D5D6D7D8"))
    )
    (comp (ref "Q39")
      (value "MOS_N_D1_S1S2S3G4D5D6D7D8")
      (footprint "SMD_SOIC127P600X110-9AN")
      (fields
        (field (name "DB_PART_NUMBER") "TRA000001604")
        (field (name "DB_VALUE") "AP1RA03GMT-HF-3")
        (field (name "DB_MANUFACTURER_PART") "ADVANCED POWER ELECTRONICS CORP      AP1RA03GMT-HF-3")
        (field (name "DB_APPROVED_BY") "VSN")
      )
      (libsource (lib "Database_Libs1") (part "MOS_N_D1_S1S2S3G4D5D6D7D8"))
    )
    (comp (ref "Q40")
      (value "MOS_N_D1_S1S2S3G4D5D6D7D8")
      (footprint "SMD_SOIC127P600X110-9AN")
      (fields
        (field (name "DB_PART_NUMBER") "TRA000001604")
        (field (name "DB_VALUE") "AP1RA03GMT-HF-3")
        (field (name "DB_MANUFACTURER_PART") "ADVANCED POWER ELECTRONICS CORP      AP1RA03GMT-HF-3")
        (field (name "DB_APPROVED_BY") "VSN")
      )
      (libsource (lib "Database_Libs1") (part "MOS_N_D1_S1S2S3G4D5D6D7D8"))
    )
    (comp (ref "Q41")
      (value "MOS_N_D1_S1S2S3G4D5D6D7D8")
      (footprint "SMD_SOIC127P600X110-9AN")
      (fields
        (field (name "DB_PART_NUMBER") "TRA000001604")
        (field (name "DB_VALUE") "AP1RA03GMT-HF-3")
        (field (name "DB_MANUFACTURER_PART") "ADVANCED POWER ELECTRONICS CORP      AP1RA03GMT-HF-3")
        (field (name "DB_APPROVED_BY") "VSN")
      )
      (libsource (lib "Database_Libs1") (part "MOS_N_D1_S1S2S3G4D5D6D7D8"))
    )
    (comp (ref "Q42")
      (value "MOS_N_D1_S1S2S3G4D5D6D7D8")
      (footprint "SMD_SOIC127P600X110-9AN")
      (fields
        (field (name "DB_PART_NUMBER") "TRA000001604")
        (field (name "DB_VALUE") "AP1RA03GMT-HF-3")
        (field (name "DB_MANUFACTURER_PART") "ADVANCED POWER ELECTRONICS CORP      AP1RA03GMT-HF-3")
        (field (name "DB_APPROVED_BY") "VSN")
      )
      (libsource (lib "Database_Libs1") (part "MOS_N_D1_S1S2S3G4D5D6D7D8"))
    )
    (comp (ref "Q43")
      (value "MOS_N_D1_S1S2S3G4D5D6D7D8")
      (footprint "SMD_SOIC127P600X110-9AN")
      (fields
        (field (name "DB_PART_NUMBER") "TRA000001604")
        (field (name "DB_VALUE") "AP1RA03GMT-HF-3")
        (field (name "DB_MANUFACTURER_PART") "ADVANCED POWER ELECTRONICS CORP      AP1RA03GMT-HF-3")
        (field (name "DB_APPROVED_BY") "VSN")
      )
      (libsource (lib "Database_Libs1") (part "MOS_N_D1_S1S2S3G4D5D6D7D8"))
    )
    (comp (ref "Q44")
      (value "MOS_N_D1_S1S2S3G4D5D6D7D8")
      (footprint "SMD_SOIC127P600X110-9AN")
      (fields
        (field (name "DB_PART_NUMBER") "TRA000001604")
        (field (name "DB_VALUE") "AP1RA03GMT-HF-3")
        (field (name "DB_MANUFACTURER_PART") "ADVANCED POWER ELECTRONICS CORP      AP1RA03GMT-HF-3")
        (field (name "DB_APPROVED_BY") "VSN")
      )
      (libsource (lib "Database_Libs1") (part "MOS_N_D1_S1S2S3G4D5D6D7D8"))
    )
    (comp (ref "Q45")
      (value "MOS_N_D1_S1S2S3G4D5D6D7D8")
      (footprint "SMD_SOIC127P600X110-9AN")
      (fields
        (field (name "DB_PART_NUMBER") "TRA000001604")
        (field (name "DB_VALUE") "AP1RA03GMT-HF-3")
        (field (name "DB_MANUFACTURER_PART") "ADVANCED POWER ELECTRONICS CORP      AP1RA03GMT-HF-3")
        (field (name "DB_APPROVED_BY") "VSN")
      )
      (libsource (lib "Database_Libs1") (part "MOS_N_D1_S1S2S3G4D5D6D7D8"))
    )
    (comp (ref "Q46")
      (value "MOS_N_D1_S1S2S3G4D5D6D7D8")
      (footprint "SMD_SOIC127P600X110-9AN")
      (fields
        (field (name "DB_PART_NUMBER") "TRA000001604")
        (field (name "DB_VALUE") "AP1RA03GMT-HF-3")
        (field (name "DB_MANUFACTURER_PART") "ADVANCED POWER ELECTRONICS CORP      AP1RA03GMT-HF-3")
        (field (name "DB_APPROVED_BY") "VSN")
      )
      (libsource (lib "Database_Libs1") (part "MOS_N_D1_S1S2S3G4D5D6D7D8"))
    )
    (comp (ref "Q47")
      (value "MOS_N_D1_S1S2S3G4D5D6D7D8")
      (footprint "SMD_SOIC127P600X110-9AN")
      (fields
        (field (name "DB_PART_NUMBER") "TRA000001604")
        (field (name "DB_VALUE") "AP1RA03GMT-HF-3")
        (field (name "DB_MANUFACTURER_PART") "ADVANCED POWER ELECTRONICS CORP      AP1RA03GMT-HF-3")
        (field (name "DB_APPROVED_BY") "VSN")
      )
      (libsource (lib "Database_Libs1") (part "MOS_N_D1_S1S2S3G4D5D6D7D8"))
    )
    (comp (ref "Q48")
      (value "MOS_N_D1_S1S2S3G4D5D6D7D8")
      (footprint "SMD_SOIC127P600X110-9AN")
      (fields
        (field (name "DB_PART_NUMBER") "TRA000001604")
        (field (name "DB_VALUE") "AP1RA03GMT-HF-3")
        (field (name "DB_MANUFACTURER_PART") "ADVANCED POWER ELECTRONICS CORP      AP1RA03GMT-HF-3")
        (field (name "DB_APPROVED_BY") "VSN")
      )
      (libsource (lib "Database_Libs1") (part "MOS_N_D1_S1S2S3G4D5D6D7D8"))
    )
    (comp (ref "U11")
      (value "IC_LTC4449")
      (footprint "SMD_SON45P300X200X80-9N")
      (fields
        (field (name "DB_PART_NUMBER") "DRV000000079")
        (field (name "DB_VALUE") "LTC4449EDCB#TRPBF")
        (field (name "DB_MANUFACTURER_PART") "LINEAR       LTC4449EDCB#TRPBF")
        (field (name "DB_APPROVED_BY") "VSN")
      )
      (libsource (lib "Database_Libs1") (part "IC_LTC4449"))
    )
    (comp (ref "U12")
      (value "IC_LTC4449")
      (footprint "SMD_SON45P300X200X80-9N")
      (fields
        (field (name "DB_PART_NUMBER") "DRV000000079")
        (field (name "DB_VALUE") "LTC4449EDCB#TRPBF")
        (field (name "DB_MANUFACTURER_PART") "LINEAR       LTC4449EDCB#TRPBF")
        (field (name "DB_APPROVED_BY") "VSN")
      )
      (libsource (lib "Database_Libs1") (part "IC_LTC4449"))
    )
    (comp (ref "U13")
      (value "IC_LTC4449")
      (footprint "SMD_SON45P300X200X80-9N")
      (fields
        (field (name "DB_PART_NUMBER") "DRV000000079")
        (field (name "DB_VALUE") "LTC4449EDCB#TRPBF")
        (field (name "DB_MANUFACTURER_PART") "LINEAR       LTC4449EDCB#TRPBF")
        (field (name "DB_APPROVED_BY") "VSN")
      )
      (libsource (lib "Database_Libs1") (part "IC_LTC4449"))
    )
    (comp (ref "U14")
      (value "IC_LTC4449")
      (footprint "SMD_SON45P300X200X80-9N")
      (fields
        (field (name "DB_PART_NUMBER") "DRV000000079")
        (field (name "DB_VALUE") "LTC4449EDCB#TRPBF")
        (field (name "DB_MANUFACTURER_PART") "LINEAR       LTC4449EDCB#TRPBF")
        (field (name "DB_APPROVED_BY") "VSN")
      )
      (libsource (lib "Database_Libs1") (part "IC_LTC4449"))
    )
    (comp (ref "U15")
      (value "IC_LTC4449")
      (footprint "SMD_SON45P300X200X80-9N")
      (fields
        (field (name "DB_PART_NUMBER") "DRV000000079")
        (field (name "DB_VALUE") "LTC4449EDCB#TRPBF")
        (field (name "DB_MANUFACTURER_PART") "LINEAR       LTC4449EDCB#TRPBF")
        (field (name "DB_APPROVED_BY") "VSN")
      )
      (libsource (lib "Database_Libs1") (part "IC_LTC4449"))
    )
    (comp (ref "U16")
      (value "IC_LTC4449")
      (footprint "SMD_SON45P300X200X80-9N")
      (fields
        (field (name "DB_PART_NUMBER") "DRV000000079")
        (field (name "DB_VALUE") "LTC4449EDCB#TRPBF")
        (field (name "DB_MANUFACTURER_PART") "LINEAR       LTC4449EDCB#TRPBF")
        (field (name "DB_APPROVED_BY") "VSN")
      )
      (libsource (lib "Database_Libs1") (part "IC_LTC4449"))
    )
    (comp (ref "U17")
      (value "IC_LTC4449")
      (footprint "SMD_SON45P300X200X80-9N")
      (fields
        (field (name "DB_PART_NUMBER") "DRV000000079")
        (field (name "DB_VALUE") "LTC4449EDCB#TRPBF")
        (field (name "DB_MANUFACTURER_PART") "LINEAR       LTC4449EDCB#TRPBF")
        (field (name "DB_APPROVED_BY") "VSN")
      )
      (libsource (lib "Database_Libs1") (part "IC_LTC4449"))
    )
    (comp (ref "U18")
      (value "IC_LTC4449")
      (footprint "SMD_SON45P300X200X80-9N")
      (fields
        (field (name "DB_PART_NUMBER") "DRV000000079")
        (field (name "DB_VALUE") "LTC4449EDCB#TRPBF")
        (field (name "DB_MANUFACTURER_PART") "LINEAR       LTC4449EDCB#TRPBF")
        (field (name "DB_APPROVED_BY") "VSN")
      )
      (libsource (lib "Database_Libs1") (part "IC_LTC4449"))
    )
    (comp (ref "U19")
      (value "IC_LTC4449")
      (footprint "SMD_SON45P300X200X80-9N")
      (fields
        (field (name "DB_PART_NUMBER") "DRV000000079")
        (field (name "DB_VALUE") "LTC4449EDCB#TRPBF")
        (field (name "DB_MANUFACTURER_PART") "LINEAR       LTC4449EDCB#TRPBF")
        (field (name "DB_APPROVED_BY") "VSN")
      )
      (libsource (lib "Database_Libs1") (part "IC_LTC4449"))
    )
    (comp (ref "U20")
      (value "IC_LTC4449")
      (footprint "SMD_SON45P300X200X80-9N")
      (fields
        (field (name "DB_PART_NUMBER") "DRV000000079")
        (field (name "DB_VALUE") "LTC4449EDCB#TRPBF")
        (field (name "DB_MANUFACTURER_PART") "LINEAR       LTC4449EDCB#TRPBF")
        (field (name "DB_APPROVED_BY") "VSN")
      )
      (libsource (lib "Database_Libs1") (part "IC_LTC4449"))
    )
    (comp (ref "U21")
      (value "IC_LTC4449")
      (footprint "SMD_SON45P300X200X80-9N")
      (fields
        (field (name "DB_PART_NUMBER") "DRV000000079")
        (field (name "DB_VALUE") "LTC4449EDCB#TRPBF")
        (field (name "DB_MANUFACTURER_PART") "LINEAR       LTC4449EDCB#TRPBF")
        (field (name "DB_APPROVED_BY") "VSN")
      )
      (libsource (lib "Database_Libs1") (part "IC_LTC4449"))
    )
    (comp (ref "U22")
      (value "IC_LTC4449")
      (footprint "SMD_SON45P300X200X80-9N")
      (fields
        (field (name "DB_PART_NUMBER") "DRV000000079")
        (field (name "DB_VALUE") "LTC4449EDCB#TRPBF")
        (field (name "DB_MANUFACTURER_PART") "LINEAR       LTC4449EDCB#TRPBF")
        (field (name "DB_APPROVED_BY") "VSN")
      )
      (libsource (lib "Database_Libs1") (part "IC_LTC4449"))
    )
    (comp (ref "U23")
      (value "IC_LTC4449")
      (footprint "SMD_SON45P300X200X80-9N")
      (fields
        (field (name "DB_PART_NUMBER") "DRV000000079")
        (field (name "DB_VALUE") "LTC4449EDCB#TRPBF")
        (field (name "DB_MANUFACTURER_PART") "LINEAR       LTC4449EDCB#TRPBF")
        (field (name "DB_APPROVED_BY") "VSN")
      )
      (libsource (lib "Database_Libs1") (part "IC_LTC4449"))
    )
    (comp (ref "U24")
      (value "IC_LTC4449")
      (footprint "SMD_SON45P300X200X80-9N")
      (fields
        (field (name "DB_PART_NUMBER") "DRV000000079")
        (field (name "DB_VALUE") "LTC4449EDCB#TRPBF")
        (field (name "DB_MANUFACTURER_PART") "LINEAR       LTC4449EDCB#TRPBF")
        (field (name "DB_APPROVED_BY") "VSN")
      )
      (libsource (lib "Database_Libs1") (part "IC_LTC4449"))
    )
    (comp (ref "U25")
      (value "IC_LTC4449")
      (footprint "SMD_SON45P300X200X80-9N")
      (fields
        (field (name "DB_PART_NUMBER") "DRV000000079")
        (field (name "DB_VALUE") "LTC4449EDCB#TRPBF")
        (field (name "DB_MANUFACTURER_PART") "LINEAR       LTC4449EDCB#TRPBF")
        (field (name "DB_APPROVED_BY") "VSN")
      )
      (libsource (lib "Database_Libs1") (part "IC_LTC4449"))
    )
    (comp (ref "U26")
      (value "IC_LTC4449")
      (footprint "SMD_SON45P300X200X80-9N")
      (fields
        (field (name "DB_PART_NUMBER") "DRV000000079")
        (field (name "DB_VALUE") "LTC4449EDCB#TRPBF")
        (field (name "DB_MANUFACTURER_PART") "LINEAR       LTC4449EDCB#TRPBF")
        (field (name "DB_APPROVED_BY") "VSN")
      )
      (libsource (lib "Database_Libs1") (part "IC_LTC4449"))
    )
  )
  (nets
    (net (code "1") (name "/1V") (class "Default")
      (node (ref "C100") (pin "2") (pinfunction "2_2") (pintype "passive"))
      (node (ref "C103") (pin "2") (pinfunction "2_2") (pintype "passive"))
      (node (ref "C104") (pin "2") (pinfunction "2_2") (pintype "passive"))
      (node (ref "C105") (pin "2") (pinfunction "2_2") (pintype "passive"))
      (node (ref "C108") (pin "2") (pinfunction "2_2") (pintype "passive"))
      (node (ref "C109") (pin "2") (pinfunction "2_2") (pintype "passive"))
      (node (ref "C110") (pin "2") (pinfunction "2_2") (pintype "passive"))
      (node (ref "C113") (pin "2") (pinfunction "2_2") (pintype "passive"))
      (node (ref "C114") (pin "2") (pinfunction "2_2") (pintype "passive"))
      (node (ref "C115") (pin "2") (pinfunction "2_2") (pintype "passive"))
      (node (ref "C130") (pin "2") (pinfunction "2_2") (pintype "passive"))
      (node (ref "C131") (pin "2") (pinfunction "2_2") (pintype "passive"))
      (node (ref "C132") (pin "2") (pinfunction "2_2") (pintype "passive"))
      (node (ref "C135") (pin "2") (pinfunction "2_2") (pintype "passive"))
      (node (ref "C136") (pin "2") (pinfunction "2_2") (pintype "passive"))
      (node (ref "C137") (pin "2") (pinfunction "2_2") (pintype "passive"))
      (node (ref "C140") (pin "2") (pinfunction "2_2") (pintype "passive"))
      (node (ref "C141") (pin "2") (pinfunction "2_2") (pintype "passive"))
      (node (ref "C142") (pin "2") (pinfunction "2_2") (pintype "passive"))
      (node (ref "C145") (pin "2") (pinfunction "2_2") (pintype "passive"))
      (node (ref "C146") (pin "2") (pinfunction "2_2") (pintype "passive"))
      (node (ref "C147") (pin "2") (pinfunction "2_2") (pintype "passive"))
      (node (ref "C236") (pin "2") (pinfunction "2_2") (pintype "passive"))
      (node (ref "C34") (pin "2") (pinfunction "2_2") (pintype "passive"))
      (node (ref "C35") (pin "2") (pinfunction "2_2") (pintype "passive"))
      (node (ref "C350") (pin "2") (pinfunction "2_2") (pintype "passive"))
      (node (ref "C351") (pin "2") (pinfunction "2_2") (pintype "passive"))
      (node (ref "C352") (pin "2") (pinfunction "2_2") (pintype "passive"))
      (node (ref "C355") (pin "2") (pinfunction "2_2") (pintype "passive"))
      (node (ref "C356") (pin "2") (pinfunction "2_2") (pintype "passive"))
      (node (ref "C357") (pin "2") (pinfunction "2_2") (pintype "passive"))
      (node (ref "C360") (pin "2") (pinfunction "2_2") (pintype "passive"))
      (node (ref "C361") (pin "2") (pinfunction "2_2") (pintype "passive"))
      (node (ref "C362") (pin "2") (pinfunction "2_2") (pintype "passive"))
      (node (ref "C365") (pin "2") (pinfunction "2_2") (pintype "passive"))
      (node (ref "C366") (pin "2") (pinfunction "2_2") (pintype "passive"))
      (node (ref "C367") (pin "2") (pinfunction "2_2") (pintype "passive"))
      (node (ref "C370") (pin "2") (pinfunction "2_2") (pintype "passive"))
      (node (ref "C371") (pin "2") (pinfunction "2_2") (pintype "passive"))
      (node (ref "C372") (pin "2") (pinfunction "2_2") (pintype "passive"))
      (node (ref "C375") (pin "2") (pinfunction "2_2") (pintype "passive"))
      (node (ref "C376") (pin "2") (pinfunction "2_2") (pintype "passive"))
      (node (ref "C377") (pin "2") (pinfunction "2_2") (pintype "passive"))
      (node (ref "C380") (pin "2") (pinfunction "2_2") (pintype "passive"))
      (node (ref "C381") (pin "2") (pinfunction "2_2") (pintype "passive"))
      (node (ref "C382") (pin "2") (pinfunction "2_2") (pintype "passive"))
      (node (ref "C385") (pin "2") (pinfunction "2_2") (pintype "passive"))
      (node (ref "C386") (pin "2") (pinfunction "2_2") (pintype "passive"))
      (node (ref "C387") (pin "2") (pinfunction "2_2") (pintype "passive"))
      (node (ref "C388") (pin "2") (pinfunction "2_2") (pintype "passive"))
      (node (ref "C389") (pin "2") (pinfunction "2_2") (pintype "passive"))
      (node (ref "C39") (pin "2") (pinfunction "2_2") (pintype "passive"))
      (node (ref "C390") (pin "2") (pinfunction "2_2") (pintype "passive"))
      (node (ref "C393") (pin "2") (pinfunction "2_2") (pintype "passive"))
      (node (ref "C394") (pin "2") (pinfunction "2_2") (pintype "passive"))
      (node (ref "C395") (pin "2") (pinfunction "2_2") (pintype "passive"))
      (node (ref "C396") (pin "2") (pinfunction "2_2") (pintype "passive"))
      (node (ref "C397") (pin "2") (pinfunction "2_2") (pintype "passive"))
      (node (ref "C398") (pin "2") (pinfunction "2_2") (pintype "passive"))
      (node (ref "C399") (pin "2") (pinfunction "2_2") (pintype "passive"))
      (node (ref "C40") (pin "2") (pinfunction "2_2") (pintype "passive"))
      (node (ref "C400") (pin "2") (pinfunction "2_2") (pintype "passive"))
      (node (ref "C401") (pin "2") (pinfunction "2_2") (pintype "passive"))
      (node (ref "C408") (pin "2") (pinfunction "2_2") (pintype "passive"))
      (node (ref "C409") (pin "2") (pinfunction "2_2") (pintype "passive"))
      (node (ref "C41") (pin "2") (pinfunction "2_2") (pintype "passive"))
      (node (ref "C410") (pin "2") (pinfunction "2_2") (pintype "passive"))
      (node (ref "C411") (pin "2") (pinfunction "2_2") (pintype "passive"))
      (node (ref "C412") (pin "2") (pinfunction "2_2") (pintype "passive"))
      (node (ref "C413") (pin "2") (pinfunction "2_2") (pintype "passive"))
      (node (ref "C414") (pin "2") (pinfunction "2_2") (pintype "passive"))
      (node (ref "C415") (pin "2") (pinfunction "2_2") (pintype "passive"))
      (node (ref "C416") (pin "2") (pinfunction "2_2") (pintype "passive"))
      (node (ref "C417") (pin "2") (pinfunction "2_2") (pintype "passive"))
      (node (ref "C418") (pin "2") (pinfunction "2_2") (pintype "passive"))
      (node (ref "C419") (pin "2") (pinfunction "2_2") (pintype "passive"))
      (node (ref "C44") (pin "2") (pinfunction "2_2") (pintype "passive"))
      (node (ref "C45") (pin "2") (pinfunction "2_2") (pintype "passive"))
      (node (ref "C46") (pin "2") (pinfunction "2_2") (pintype "passive"))
      (node (ref "C49") (pin "2") (pinfunction "2_2") (pintype "passive"))
      (node (ref "C50") (pin "2") (pinfunction "2_2") (pintype "passive"))
      (node (ref "C51") (pin "2") (pinfunction "2_2") (pintype "passive"))
      (node (ref "C66") (pin "2") (pinfunction "2_2") (pintype "passive"))
      (node (ref "C67") (pin "2") (pinfunction "2_2") (pintype "passive"))
      (node (ref "C68") (pin "2") (pinfunction "2_2") (pintype "passive"))
      (node (ref "C71") (pin "2") (pinfunction "2_2") (pintype "passive"))
      (node (ref "C72") (pin "2") (pinfunction "2_2") (pintype "passive"))
      (node (ref "C73") (pin "2") (pinfunction "2_2") (pintype "passive"))
      (node (ref "C76") (pin "2") (pinfunction "2_2") (pintype "passive"))
      (node (ref "C77") (pin "2") (pinfunction "2_2") (pintype "passive"))
      (node (ref "C78") (pin "2") (pinfunction "2_2") (pintype "passive"))
      (node (ref "C81") (pin "2") (pinfunction "2_2") (pintype "passive"))
      (node (ref "C82") (pin "2") (pinfunction "2_2") (pintype "passive"))
      (node (ref "C83") (pin "2") (pinfunction "2_2") (pintype "passive"))
      (node (ref "C98") (pin "2") (pinfunction "2_2") (pintype "passive"))
      (node (ref "C99") (pin "2") (pinfunction "2_2") (pintype "passive"))
      (node (ref "L1") (pin "2") (pinfunction "2_2") (pintype "passive"))
      (node (ref "L10") (pin "2") (pinfunction "2_2") (pintype "passive"))
      (node (ref "L11") (pin "2") (pinfunction "2_2") (pintype "passive"))
      (node (ref "L12") (pin "2") (pinfunction "2_2") (pintype "passive"))
      (node (ref "L13") (pin "2") (pinfunction "2_2") (pintype "passive"))
      (node (ref "L14") (pin "2") (pinfunction "2_2") (pintype "passive"))
      (node (ref "L15") (pin "2") (pinfunction "2_2") (pintype "passive"))
      (node (ref "L16") (pin "2") (pinfunction "2_2") (pintype "passive"))
      (node (ref "L2") (pin "2") (pinfunction "2_2") (pintype "passive"))
      (node (ref "L3") (pin "2") (pinfunction "2_2") (pintype "passive"))
      (node (ref "L4") (pin "2") (pinfunction "2_2") (pintype "passive"))
      (node (ref "L5") (pin "2") (pinfunction "2_2") (pintype "passive"))
      (node (ref "L6") (pin "2") (pinfunction "2_2") (pintype "passive"))
      (node (ref "L7") (pin "2") (pinfunction "2_2") (pintype "passive"))
      (node (ref "L8") (pin "2") (pinfunction "2_2") (pintype "passive"))
      (node (ref "L9") (pin "2") (pinfunction "2_2") (pintype "passive"))
    )
    (net (code "2") (name "/3.3V") (class "Default")
      (node (ref "C120") (pin "1") (pinfunction "1_1") (pintype "passive"))
      (node (ref "C121") (pin "1") (pinfunction "1_1") (pintype "passive"))
      (node (ref "C122") (pin "1") (pinfunction "1_1") (pintype "passive"))
      (node (ref "C123") (pin "1") (pinfunction "1_1") (pintype "passive"))
      (node (ref "C24") (pin "1") (pinfunction "1_1") (pintype "passive"))
      (node (ref "C25") (pin "1") (pinfunction "1_1") (pintype "passive"))
      (node (ref "C26") (pin "1") (pinfunction "1_1") (pintype "passive"))
      (node (ref "C27") (pin "1") (pinfunction "1_1") (pintype "passive"))
      (node (ref "C56") (pin "1") (pinfunction "1_1") (pintype "passive"))
      (node (ref "C57") (pin "1") (pinfunction "1_1") (pintype "passive"))
      (node (ref "C58") (pin "1") (pinfunction "1_1") (pintype "passive"))
      (node (ref "C59") (pin "1") (pinfunction "1_1") (pintype "passive"))
      (node (ref "C88") (pin "1") (pinfunction "1_1") (pintype "passive"))
      (node (ref "C89") (pin "1") (pinfunction "1_1") (pintype "passive"))
      (node (ref "C90") (pin "1") (pinfunction "1_1") (pintype "passive"))
      (node (ref "C91") (pin "1") (pinfunction "1_1") (pintype "passive"))
      (node (ref "U11") (pin "6") (pinfunction "VLOGIC_6") (pintype "passive"))
      (node (ref "U12") (pin "6") (pinfunction "VLOGIC_6") (pintype "passive"))
      (node (ref "U13") (pin "6") (pinfunction "VLOGIC_6") (pintype "passive"))
      (node (ref "U14") (pin "6") (pinfunction "VLOGIC_6") (pintype "passive"))
      (node (ref "U15") (pin "6") (pinfunction "VLOGIC_6") (pintype "passive"))
      (node (ref "U16") (pin "6") (pinfunction "VLOGIC_6") (pintype "passive"))
      (node (ref "U17") (pin "6") (pinfunction "VLOGIC_6") (pintype "passive"))
      (node (ref "U18") (pin "6") (pinfunction "VLOGIC_6") (pintype "passive"))
      (node (ref "U19") (pin "6") (pinfunction "VLOGIC_6") (pintype "passive"))
      (node (ref "U20") (pin "6") (pinfunction "VLOGIC_6") (pintype "passive"))
      (node (ref "U21") (pin "6") (pinfunction "VLOGIC_6") (pintype "passive"))
      (node (ref "U22") (pin "6") (pinfunction "VLOGIC_6") (pintype "passive"))
      (node (ref "U23") (pin "6") (pinfunction "VLOGIC_6") (pintype "passive"))
      (node (ref "U24") (pin "6") (pinfunction "VLOGIC_6") (pintype "passive"))
      (node (ref "U25") (pin "6") (pinfunction "VLOGIC_6") (pintype "passive"))
      (node (ref "U26") (pin "6") (pinfunction "VLOGIC_6") (pintype "passive"))
    )
    (net (code "3") (name "/5.0V") (class "Default")
      (node (ref "C116") (pin "2") (pinfunction "2_2") (pintype "passive"))
      (node (ref "C117") (pin "2") (pinfunction "2_2") (pintype "passive"))
      (node (ref "C118") (pin "2") (pinfunction "2_2") (pintype "passive"))
      (node (ref "C119") (pin "2") (pinfunction "2_2") (pintype "passive"))
      (node (ref "C20") (pin "2") (pinfunction "2_2") (pintype "passive"))
      (node (ref "C21") (pin "2") (pinfunction "2_2") (pintype "passive"))
      (node (ref "C22") (pin "2") (pinfunction "2_2") (pintype "passive"))
      (node (ref "C23") (pin "2") (pinfunction "2_2") (pintype "passive"))
      (node (ref "C52") (pin "2") (pinfunction "2_2") (pintype "passive"))
      (node (ref "C53") (pin "2") (pinfunction "2_2") (pintype "passive"))
      (node (ref "C54") (pin "2") (pinfunction "2_2") (pintype "passive"))
      (node (ref "C55") (pin "2") (pinfunction "2_2") (pintype "passive"))
      (node (ref "C84") (pin "2") (pinfunction "2_2") (pintype "passive"))
      (node (ref "C85") (pin "2") (pinfunction "2_2") (pintype "passive"))
      (node (ref "C86") (pin "2") (pinfunction "2_2") (pintype "passive"))
      (node (ref "C87") (pin "2") (pinfunction "2_2") (pintype "passive"))
      (node (ref "D10") (pin "2") (pinfunction "A_2") (pintype "passive"))
      (node (ref "D11") (pin "2") (pinfunction "A_2") (pintype "passive"))
      (node (ref "D12") (pin "2") (pinfunction "A_2") (pintype "passive"))
      (node (ref "D13") (pin "2") (pinfunction "A_2") (pintype "passive"))
      (node (ref "D14") (pin "2") (pinfunction "A_2") (pintype "passive"))
      (node (ref "D15") (pin "2") (pinfunction "A_2") (pintype "passive"))
      (node (ref "D16") (pin "2") (pinfunction "A_2") (pintype "passive"))
      (node (ref "D17") (pin "2") (pinfunction "A_2") (pintype "passive"))
      (node (ref "D18") (pin "2") (pinfunction "A_2") (pintype "passive"))
      (node (ref "D19") (pin "2") (pinfunction "A_2") (pintype "passive"))
      (node (ref "D20") (pin "2") (pinfunction "A_2") (pintype "passive"))
      (node (ref "D21") (pin "2") (pinfunction "A_2") (pintype "passive"))
      (node (ref "D22") (pin "2") (pinfunction "A_2") (pintype "passive"))
      (node (ref "D23") (pin "2") (pinfunction "A_2") (pintype "passive"))
      (node (ref "D24") (pin "2") (pinfunction "A_2") (pintype "passive"))
      (node (ref "D25") (pin "2") (pinfunction "A_2") (pintype "passive"))
      (node (ref "U11") (pin "7") (pinfunction "VCC_7") (pintype "passive"))
      (node (ref "U12") (pin "7") (pinfunction "VCC_7") (pintype "passive"))
      (node (ref "U13") (pin "7") (pinfunction "VCC_7") (pintype "passive"))
      (node (ref "U14") (pin "7") (pinfunction "VCC_7") (pintype "passive"))
      (node (ref "U15") (pin "7") (pinfunction "VCC_7") (pintype "passive"))
      (node (ref "U16") (pin "7") (pinfunction "VCC_7") (pintype "passive"))
      (node (ref "U17") (pin "7") (pinfunction "VCC_7") (pintype "passive"))
      (node (ref "U18") (pin "7") (pinfunction "VCC_7") (pintype "passive"))
      (node (ref "U19") (pin "7") (pinfunction "VCC_7") (pintype "passive"))
      (node (ref "U20") (pin "7") (pinfunction "VCC_7") (pintype "passive"))
      (node (ref "U21") (pin "7") (pinfunction "VCC_7") (pintype "passive"))
      (node (ref "U22") (pin "7") (pinfunction "VCC_7") (pintype "passive"))
      (node (ref "U23") (pin "7") (pinfunction "VCC_7") (pintype "passive"))
      (node (ref "U24") (pin "7") (pinfunction "VCC_7") (pintype "passive"))
      (node (ref "U25") (pin "7") (pinfunction "VCC_7") (pintype "passive"))
      (node (ref "U26") (pin "7") (pinfunction "VCC_7") (pintype "passive"))
    )
    (net (code "4") (name "/12V") (class "Default")
      (node (ref "C101") (pin "2") (pinfunction "2_2") (pintype "passive"))
      (node (ref "C102") (pin "2") (pinfunction "2_2") (pintype "passive"))
      (node (ref "C106") (pin "2") (pinfunction "2_2") (pintype "passive"))
      (node (ref "C107") (pin "2") (pinfunction "2_2") (pintype "passive"))
      (node (ref "C111") (pin "2") (pinfunction "2_2") (pintype "passive"))
      (node (ref "C112") (pin "2") (pinfunction "2_2") (pintype "passive"))
      (node (ref "C128") (pin "2") (pinfunction "2_2") (pintype "passive"))
      (node (ref "C129") (pin "2") (pinfunction "2_2") (pintype "passive"))
      (node (ref "C133") (pin "2") (pinfunction "2_2") (pintype "passive"))
      (node (ref "C134") (pin "2") (pinfunction "2_2") (pintype "passive"))
      (node (ref "C138") (pin "2") (pinfunction "2_2") (pintype "passive"))
      (node (ref "C139") (pin "2") (pinfunction "2_2") (pintype "passive"))
      (node (ref "C143") (pin "2") (pinfunction "2_2") (pintype "passive"))
      (node (ref "C144") (pin "2") (pinfunction "2_2") (pintype "passive"))
      (node (ref "C32") (pin "2") (pinfunction "2_2") (pintype "passive"))
      (node (ref "C33") (pin "2") (pinfunction "2_2") (pintype "passive"))
      (node (ref "C348") (pin "2") (pinfunction "2_2") (pintype "passive"))
      (node (ref "C349") (pin "2") (pinfunction "2_2") (pintype "passive"))
      (node (ref "C353") (pin "2") (pinfunction "2_2") (pintype "passive"))
      (node (ref "C354") (pin "2") (pinfunction "2_2") (pintype "passive"))
      (node (ref "C358") (pin "2") (pinfunction "2_2") (pintype "passive"))
      (node (ref "C359") (pin "2") (pinfunction "2_2") (pintype "passive"))
      (node (ref "C363") (pin "2") (pinfunction "2_2") (pintype "passive"))
      (node (ref "C364") (pin "2") (pinfunction "2_2") (pintype "passive"))
      (node (ref "C368") (pin "2") (pinfunction "2_2") (pintype "passive"))
      (node (ref "C369") (pin "2") (pinfunction "2_2") (pintype "passive"))
      (node (ref "C37") (pin "2") (pinfunction "2_2") (pintype "passive"))
      (node (ref "C373") (pin "2") (pinfunction "2_2") (pintype "passive"))
      (node (ref "C374") (pin "2") (pinfunction "2_2") (pintype "passive"))
      (node (ref "C378") (pin "2") (pinfunction "2_2") (pintype "passive"))
      (node (ref "C379") (pin "2") (pinfunction "2_2") (pintype "passive"))
      (node (ref "C38") (pin "2") (pinfunction "2_2") (pintype "passive"))
      (node (ref "C383") (pin "2") (pinfunction "2_2") (pintype "passive"))
      (node (ref "C384") (pin "2") (pinfunction "2_2") (pintype "passive"))
      (node (ref "C391") (pin "2") (pinfunction "2_2") (pintype "passive"))
      (node (ref "C392") (pin "2") (pinfunction "2_2") (pintype "passive"))
      (node (ref "C402") (pin "2") (pinfunction "2_2") (pintype "passive"))
      (node (ref "C403") (pin "2") (pinfunction "2_2") (pintype "passive"))
      (node (ref "C404") (pin "2") (pinfunction "2_2") (pintype "passive"))
      (node (ref "C405") (pin "2") (pinfunction "2_2") (pintype "passive"))
      (node (ref "C406") (pin "2") (pinfunction "2_2") (pintype "passive"))
      (node (ref "C407") (pin "2") (pinfunction "2_2") (pintype "passive"))
      (node (ref "C42") (pin "2") (pinfunction "2_2") (pintype "passive"))
      (node (ref "C420") (pin "2") (pinfunction "2_2") (pintype "passive"))
      (node (ref "C421") (pin "2") (pinfunction "2_2") (pintype "passive"))
      (node (ref "C422") (pin "2") (pinfunction "2_2") (pintype "passive"))
      (node (ref "C423") (pin "2") (pinfunction "2_2") (pintype "passive"))
      (node (ref "C424") (pin "2") (pinfunction "2_2") (pintype "passive"))
      (node (ref "C425") (pin "2") (pinfunction "2_2") (pintype "passive"))
      (node (ref "C426") (pin "2") (pinfunction "2_2") (pintype "passive"))
      (node (ref "C427") (pin "2") (pinfunction "2_2") (pintype "passive"))
      (node (ref "C43") (pin "2") (pinfunction "2_2") (pintype "passive"))
      (node (ref "C47") (pin "2") (pinfunction "2_2") (pintype "passive"))
      (node (ref "C48") (pin "2") (pinfunction "2_2") (pintype "passive"))
      (node (ref "C64") (pin "2") (pinfunction "2_2") (pintype "passive"))
      (node (ref "C65") (pin "2") (pinfunction "2_2") (pintype "passive"))
      (node (ref "C69") (pin "2") (pinfunction "2_2") (pintype "passive"))
      (node (ref "C70") (pin "2") (pinfunction "2_2") (pintype "passive"))
      (node (ref "C74") (pin "2") (pinfunction "2_2") (pintype "passive"))
      (node (ref "C75") (pin "2") (pinfunction "2_2") (pintype "passive"))
      (node (ref "C79") (pin "2") (pinfunction "2_2") (pintype "passive"))
      (node (ref "C80") (pin "2") (pinfunction "2_2") (pintype "passive"))
      (node (ref "C96") (pin "2") (pinfunction "2_2") (pintype "passive"))
      (node (ref "C97") (pin "2") (pinfunction "2_2") (pintype "passive"))
      (node (ref "Q1") (pin "5") (pinfunction "D_5") (pintype "passive"))
      (node (ref "Q1") (pin "6") (pinfunction "D_6") (pintype "passive"))
      (node (ref "Q1") (pin "7") (pinfunction "D_7") (pintype "passive"))
      (node (ref "Q1") (pin "8") (pinfunction "D_8") (pintype "passive"))
      (node (ref "Q13") (pin "5") (pinfunction "D_5") (pintype "passive"))
      (node (ref "Q13") (pin "6") (pinfunction "D_6") (pintype "passive"))
      (node (ref "Q13") (pin "7") (pinfunction "D_7") (pintype "passive"))
      (node (ref "Q13") (pin "8") (pinfunction "D_8") (pintype "passive"))
      (node (ref "Q14") (pin "5") (pinfunction "D_5") (pintype "passive"))
      (node (ref "Q14") (pin "6") (pinfunction "D_6") (pintype "passive"))
      (node (ref "Q14") (pin "7") (pinfunction "D_7") (pintype "passive"))
      (node (ref "Q14") (pin "8") (pinfunction "D_8") (pintype "passive"))
      (node (ref "Q15") (pin "5") (pinfunction "D_5") (pintype "passive"))
      (node (ref "Q15") (pin "6") (pinfunction "D_6") (pintype "passive"))
      (node (ref "Q15") (pin "7") (pinfunction "D_7") (pintype "passive"))
      (node (ref "Q15") (pin "8") (pinfunction "D_8") (pintype "passive"))
      (node (ref "Q16") (pin "5") (pinfunction "D_5") (pintype "passive"))
      (node (ref "Q16") (pin "6") (pinfunction "D_6") (pintype "passive"))
      (node (ref "Q16") (pin "7") (pinfunction "D_7") (pintype "passive"))
      (node (ref "Q16") (pin "8") (pinfunction "D_8") (pintype "passive"))
      (node (ref "Q2") (pin "5") (pinfunction "D_5") (pintype "passive"))
      (node (ref "Q2") (pin "6") (pinfunction "D_6") (pintype "passive"))
      (node (ref "Q2") (pin "7") (pinfunction "D_7") (pintype "passive"))
      (node (ref "Q2") (pin "8") (pinfunction "D_8") (pintype "passive"))
      (node (ref "Q25") (pin "5") (pinfunction "D_5") (pintype "passive"))
      (node (ref "Q25") (pin "6") (pinfunction "D_6") (pintype "passive"))
      (node (ref "Q25") (pin "7") (pinfunction "D_7") (pintype "passive"))
      (node (ref "Q25") (pin "8") (pinfunction "D_8") (pintype "passive"))
      (node (ref "Q26") (pin "5") (pinfunction "D_5") (pintype "passive"))
      (node (ref "Q26") (pin "6") (pinfunction "D_6") (pintype "passive"))
      (node (ref "Q26") (pin "7") (pinfunction "D_7") (pintype "passive"))
      (node (ref "Q26") (pin "8") (pinfunction "D_8") (pintype "passive"))
      (node (ref "Q27") (pin "5") (pinfunction "D_5") (pintype "passive"))
      (node (ref "Q27") (pin "6") (pinfunction "D_6") (pintype "passive"))
      (node (ref "Q27") (pin "7") (pinfunction "D_7") (pintype "passive"))
      (node (ref "Q27") (pin "8") (pinfunction "D_8") (pintype "passive"))
      (node (ref "Q28") (pin "5") (pinfunction "D_5") (pintype "passive"))
      (node (ref "Q28") (pin "6") (pinfunction "D_6") (pintype "passive"))
      (node (ref "Q28") (pin "7") (pinfunction "D_7") (pintype "passive"))
      (node (ref "Q28") (pin "8") (pinfunction "D_8") (pintype "passive"))
      (node (ref "Q3") (pin "5") (pinfunction "D_5") (pintype "passive"))
      (node (ref "Q3") (pin "6") (pinfunction "D_6") (pintype "passive"))
      (node (ref "Q3") (pin "7") (pinfunction "D_7") (pintype "passive"))
      (node (ref "Q3") (pin "8") (pinfunction "D_8") (pintype "passive"))
      (node (ref "Q37") (pin "5") (pinfunction "D_5") (pintype "passive"))
      (node (ref "Q37") (pin "6") (pinfunction "D_6") (pintype "passive"))
      (node (ref "Q37") (pin "7") (pinfunction "D_7") (pintype "passive"))
      (node (ref "Q37") (pin "8") (pinfunction "D_8") (pintype "passive"))
      (node (ref "Q38") (pin "5") (pinfunction "D_5") (pintype "passive"))
      (node (ref "Q38") (pin "6") (pinfunction "D_6") (pintype "passive"))
      (node (ref "Q38") (pin "7") (pinfunction "D_7") (pintype "passive"))
      (node (ref "Q38") (pin "8") (pinfunction "D_8") (pintype "passive"))
      (node (ref "Q39") (pin "5") (pinfunction "D_5") (pintype "passive"))
      (node (ref "Q39") (pin "6") (pinfunction "D_6") (pintype "passive"))
      (node (ref "Q39") (pin "7") (pinfunction "D_7") (pintype "passive"))
      (node (ref "Q39") (pin "8") (pinfunction "D_8") (pintype "passive"))
      (node (ref "Q4") (pin "5") (pinfunction "D_5") (pintype "passive"))
      (node (ref "Q4") (pin "6") (pinfunction "D_6") (pintype "passive"))
      (node (ref "Q4") (pin "7") (pinfunction "D_7") (pintype "passive"))
      (node (ref "Q4") (pin "8") (pinfunction "D_8") (pintype "passive"))
      (node (ref "Q40") (pin "5") (pinfunction "D_5") (pintype "passive"))
      (node (ref "Q40") (pin "6") (pinfunction "D_6") (pintype "passive"))
      (node (ref "Q40") (pin "7") (pinfunction "D_7") (pintype "passive"))
      (node (ref "Q40") (pin "8") (pinfunction "D_8") (pintype "passive"))
    )
    (net (code "5") (name "/BOOT1") (class "Default")
      (node (ref "C28") (pin "1") (pinfunction "1_1") (pintype "passive"))
      (node (ref "D10") (pin "1") (pinfunction "C_1") (pintype "passive"))
      (node (ref "U11") (pin "8") (pinfunction "BOOST_8") (pintype "passive"))
    )
    (net (code "6") (name "/BOOT2") (class "Default")
      (node (ref "C60") (pin "1") (pinfunction "1_1") (pintype "passive"))
      (node (ref "D14") (pin "1") (pinfunction "C_1") (pintype "passive"))
      (node (ref "U15") (pin "8") (pinfunction "BOOST_8") (pintype "passive"))
    )
    (net (code "7") (name "/BOOT3") (class "Default")
      (node (ref "C92") (pin "1") (pinfunction "1_1") (pintype "passive"))
      (node (ref "D18") (pin "1") (pinfunction "C_1") (pintype "passive"))
      (node (ref "U19") (pin "8") (pinfunction "BOOST_8") (pintype "passive"))
    )
    (net (code "8") (name "/BOOT4") (class "Default")
      (node (ref "C124") (pin "1") (pinfunction "1_1") (pintype "passive"))
      (node (ref "D22") (pin "1") (pinfunction "C_1") (pintype "passive"))
      (node (ref "U23") (pin "8") (pinfunction "BOOST_8") (pintype "passive"))
    )
    (net (code "9") (name "/BOOT5") (class "Default")
      (node (ref "C29") (pin "1") (pinfunction "1_1") (pintype "passive"))
      (node (ref "D11") (pin "1") (pinfunction "C_1") (pintype "passive"))
      (node (ref "U12") (pin "8") (pinfunction "BOOST_8") (pintype "passive"))
    )
    (net (code "10") (name "/BOOT6") (class "Default")
      (node (ref "C61") (pin "1") (pinfunction "1_1") (pintype "passive"))
      (node (ref "D15") (pin "1") (pinfunction "C_1") (pintype "passive"))
      (node (ref "U16") (pin "8") (pinfunction "BOOST_8") (pintype "passive"))
    )
    (net (code "11") (name "/BOOT7") (class "Default")
      (node (ref "C93") (pin "1") (pinfunction "1_1") (pintype "passive"))
      (node (ref "D19") (pin "1") (pinfunction "C_1") (pintype "passive"))
      (node (ref "U20") (pin "8") (pinfunction "BOOST_8") (pintype "passive"))
    )
    (net (code "12") (name "/BOOT8") (class "Default")
      (node (ref "C125") (pin "1") (pinfunction "1_1") (pintype "passive"))
      (node (ref "D23") (pin "1") (pinfunction "C_1") (pintype "passive"))
      (node (ref "U24") (pin "8") (pinfunction "BOOST_8") (pintype "passive"))
    )
    (net (code "13") (name "/BOOT9") (class "Default")
      (node (ref "C30") (pin "1") (pinfunction "1_1") (pintype "passive"))
      (node (ref "D12") (pin "1") (pinfunction "C_1") (pintype "passive"))
      (node (ref "U13") (pin "8") (pinfunction "BOOST_8") (pintype "passive"))
    )
    (net (code "14") (name "/BOOT10") (class "Default")
      (node (ref "C62") (pin "1") (pinfunction "1_1") (pintype "passive"))
      (node (ref "D16") (pin "1") (pinfunction "C_1") (pintype "passive"))
      (node (ref "U17") (pin "8") (pinfunction "BOOST_8") (pintype "passive"))
    )
    (net (code "15") (name "/BOOT11") (class "Default")
      (node (ref "C94") (pin "1") (pinfunction "1_1") (pintype "passive"))
      (node (ref "D20") (pin "1") (pinfunction "C_1") (pintype "passive"))
      (node (ref "U21") (pin "8") (pinfunction "BOOST_8") (pintype "passive"))
    )
    (net (code "16") (name "/BOOT12") (class "Default")
      (node (ref "C126") (pin "1") (pinfunction "1_1") (pintype "passive"))
      (node (ref "D24") (pin "1") (pinfunction "C_1") (pintype "passive"))
      (node (ref "U25") (pin "8") (pinfunction "BOOST_8") (pintype "passive"))
    )
    (net (code "17") (name "/BOOT13") (class "Default")
      (node (ref "C31") (pin "1") (pinfunction "1_1") (pintype "passive"))
      (node (ref "D13") (pin "1") (pinfunction "C_1") (pintype "passive"))
      (node (ref "U14") (pin "8") (pinfunction "BOOST_8") (pintype "passive"))
    )
    (net (code "18") (name "/BOOT14") (class "Default")
      (node (ref "C63") (pin "1") (pinfunction "1_1") (pintype "passive"))
      (node (ref "D17") (pin "1") (pinfunction "C_1") (pintype "passive"))
      (node (ref "U18") (pin "8") (pinfunction "BOOST_8") (pintype "passive"))
    )
    (net (code "19") (name "/BOOT15") (class "Default")
      (node (ref "C95") (pin "1") (pinfunction "1_1") (pintype "passive"))
      (node (ref "D21") (pin "1") (pinfunction "C_1") (pintype "passive"))
      (node (ref "U22") (pin "8") (pinfunction "BOOST_8") (pintype "passive"))
    )
    (net (code "20") (name "/BOOT16") (class "Default")
      (node (ref "C127") (pin "1") (pinfunction "1_1") (pintype "passive"))
      (node (ref "D25") (pin "1") (pinfunction "C_1") (pintype "passive"))
      (node (ref "U26") (pin "8") (pinfunction "BOOST_8") (pintype "passive"))
    )
    (net (code "21") (name "/HO1") (class "Default")
      (node (ref "Q1") (pin "4") (pinfunction "G_4") (pintype "passive"))
      (node (ref "U11") (pin "1") (pinfunction "TG_1") (pintype "passive"))
    )
    (net (code "22") (name "/HO2") (class "Default")
      (node (ref "Q13") (pin "4") (pinfunction "G_4") (pintype "passive"))
      (node (ref "U15") (pin "1") (pinfunction "TG_1") (pintype "passive"))
    )
    (net (code "23") (name "/HO3") (class "Default")
      (node (ref "Q25") (pin "4") (pinfunction "G_4") (pintype "passive"))
      (node (ref "U19") (pin "1") (pinfunction "TG_1") (pintype "passive"))
    )
    (net (code "24") (name "/HO4") (class "Default")
      (node (ref "Q37") (pin "4") (pinfunction "G_4") (pintype "passive"))
      (node (ref "U23") (pin "1") (pinfunction "TG_1") (pintype "passive"))
    )
    (net (code "25") (name "/HO5") (class "Default")
      (node (ref "Q2") (pin "4") (pinfunction "G_4") (pintype "passive"))
      (node (ref "U12") (pin "1") (pinfunction "TG_1") (pintype "passive"))
    )
    (net (code "26") (name "/HO6") (class "Default")
      (node (ref "Q14") (pin "4") (pinfunction "G_4") (pintype "passive"))
      (node (ref "U16") (pin "1") (pinfunction "TG_1") (pintype "passive"))
    )
    (net (code "27") (name "/HO7") (class "Default")
      (node (ref "Q26") (pin "4") (pinfunction "G_4") (pintype "passive"))
      (node (ref "U20") (pin "1") (pinfunction "TG_1") (pintype "passive"))
    )
    (net (code "28") (name "/HO8") (class "Default")
      (node (ref "Q38") (pin "4") (pinfunction "G_4") (pintype "passive"))
      (node (ref "U24") (pin "1") (pinfunction "TG_1") (pintype "passive"))
    )
    (net (code "29") (name "/HO9") (class "Default")
      (node (ref "Q3") (pin "4") (pinfunction "G_4") (pintype "passive"))
      (node (ref "U13") (pin "1") (pinfunction "TG_1") (pintype "passive"))
    )
    (net (code "30") (name "/HO10") (class "Default")
      (node (ref "Q15") (pin "4") (pinfunction "G_4") (pintype "passive"))
      (node (ref "U17") (pin "1") (pinfunction "TG_1") (pintype "passive"))
    )
    (net (code "31") (name "/HO11") (class "Default")
      (node (ref "Q27") (pin "4") (pinfunction "G_4") (pintype "passive"))
      (node (ref "U21") (pin "1") (pinfunction "TG_1") (pintype "passive"))
    )
    (net (code "32") (name "/HO12") (class "Default")
      (node (ref "Q39") (pin "4") (pinfunction "G_4") (pintype "passive"))
      (node (ref "U25") (pin "1") (pinfunction "TG_1") (pintype "passive"))
    )
    (net (code "33") (name "/HO13") (class "Default")
      (node (ref "Q4") (pin "4") (pinfunction "G_4") (pintype "passive"))
      (node (ref "U14") (pin "1") (pinfunction "TG_1") (pintype "passive"))
    )
    (net (code "34") (name "/HO14") (class "Default")
      (node (ref "Q16") (pin "4") (pinfunction "G_4") (pintype "passive"))
      (node (ref "U18") (pin "1") (pinfunction "TG_1") (pintype "passive"))
    )
    (net (code "35") (name "/HO15") (class "Default")
      (node (ref "Q28") (pin "4") (pinfunction "G_4") (pintype "passive"))
      (node (ref "U22") (pin "1") (pinfunction "TG_1") (pintype "passive"))
    )
    (net (code "36") (name "/HO16") (class "Default")
      (node (ref "Q40") (pin "4") (pinfunction "G_4") (pintype "passive"))
      (node (ref "U26") (pin "1") (pinfunction "TG_1") (pintype "passive"))
    )
    (net (code "37") (name "/LO1") (class "Default")
      (node (ref "Q5") (pin "4") (pinfunction "G_4") (pintype "passive"))
      (node (ref "Q6") (pin "4") (pinfunction "G_4") (pintype "passive"))
      (node (ref "U11") (pin "3") (pinfunction "BG_3") (pintype "passive"))
    )
    (net (code "38") (name "/LO2") (class "Default")
      (node (ref "Q17") (pin "4") (pinfunction "G_4") (pintype "passive"))
      (node (ref "Q18") (pin "4") (pinfunction "G_4") (pintype "passive"))
      (node (ref "U15") (pin "3") (pinfunction "BG_3") (pintype "passive"))
    )
    (net (code "39") (name "/LO3") (class "Default")
      (node (ref "Q29") (pin "4") (pinfunction "G_4") (pintype "passive"))
      (node (ref "Q30") (pin "4") (pinfunction "G_4") (pintype "passive"))
      (node (ref "U19") (pin "3") (pinfunction "BG_3") (pintype "passive"))
    )
    (net (code "40") (name "/LO4") (class "Default")
      (node (ref "Q41") (pin "4") (pinfunction "G_4") (pintype "passive"))
      (node (ref "Q42") (pin "4") (pinfunction "G_4") (pintype "passive"))
      (node (ref "U23") (pin "3") (pinfunction "BG_3") (pintype "passive"))
    )
    (net (code "41") (name "/LO5") (class "Default")
      (node (ref "Q7") (pin "4") (pinfunction "G_4") (pintype "passive"))
      (node (ref "Q8") (pin "4") (pinfunction "G_4") (pintype "passive"))
      (node (ref "U12") (pin "3") (pinfunction "BG_3") (pintype "passive"))
    )
    (net (code "42") (name "/LO6") (class "Default")
      (node (ref "Q19") (pin "4") (pinfunction "G_4") (pintype "passive"))
      (node (ref "Q20") (pin "4") (pinfunction "G_4") (pintype "passive"))
      (node (ref "U16") (pin "3") (pinfunction "BG_3") (pintype "passive"))
    )
    (net (code "43") (name "/LO7") (class "Default")
      (node (ref "Q31") (pin "4") (pinfunction "G_4") (pintype "passive"))
      (node (ref "Q32") (pin "4") (pinfunction "G_4") (pintype "passive"))
      (node (ref "U20") (pin "3") (pinfunction "BG_3") (pintype "passive"))
    )
    (net (code "44") (name "/LO8") (class "Default")
      (node (ref "Q43") (pin "4") (pinfunction "G_4") (pintype "passive"))
      (node (ref "Q44") (pin "4") (pinfunction "G_4") (pintype "passive"))
      (node (ref "U24") (pin "3") (pinfunction "BG_3") (pintype "passive"))
    )
    (net (code "45") (name "/LO9") (class "Default")
      (node (ref "Q10") (pin "4") (pinfunction "G_4") (pintype "passive"))
      (node (ref "Q9") (pin "4") (pinfunction "G_4") (pintype "passive"))
      (node (ref "U13") (pin "3") (pinfunction "BG_3") (pintype "passive"))
    )
    (net (code "46") (name "/LO10") (class "Default")
      (node (ref "Q21") (pin "4") (pinfunction "G_4") (pintype "passive"))
      (node (ref "Q22") (pin "4") (pinfunction "G_4") (pintype "passive"))
      (node (ref "U17") (pin "3") (pinfunction "BG_3") (pintype "passive"))
    )
    (net (code "47") (name "/LO11") (class "Default")
      (node (ref "Q33") (pin "4") (pinfunction "G_4") (pintype "passive"))
      (node (ref "Q34") (pin "4") (pinfunction "G_4") (pintype "passive"))
      (node (ref "U21") (pin "3") (pinfunction "BG_3") (pintype "passive"))
    )
    (net (code "48") (name "/LO12") (class "Default")
      (node (ref "Q45") (pin "4") (pinfunction "G_4") (pintype "passive"))
      (node (ref "Q46") (pin "4") (pinfunction "G_4") (pintype "passive"))
      (node (ref "U25") (pin "3") (pinfunction "BG_3") (pintype "passive"))
    )
    (net (code "49") (name "/LO13") (class "Default")
      (node (ref "Q11") (pin "4") (pinfunction "G_4") (pintype "passive"))
      (node (ref "Q12") (pin "4") (pinfunction "G_4") (pintype "passive"))
      (node (ref "U14") (pin "3") (pinfunction "BG_3") (pintype "passive"))
    )
    (net (code "50") (name "/LO14") (class "Default")
      (node (ref "Q23") (pin "4") (pinfunction "G_4") (pintype "passive"))
      (node (ref "Q24") (pin "4") (pinfunction "G_4") (pintype "passive"))
      (node (ref "U18") (pin "3") (pinfunction "BG_3") (pintype "passive"))
    )
    (net (code "51") (name "/LO15") (class "Default")
      (node (ref "Q35") (pin "4") (pinfunction "G_4") (pintype "passive"))
      (node (ref "Q36") (pin "4") (pinfunction "G_4") (pintype "passive"))
      (node (ref "U22") (pin "3") (pinfunction "BG_3") (pintype "passive"))
    )
    (net (code "52") (name "/LO16") (class "Default")
      (node (ref "Q47") (pin "4") (pinfunction "G_4") (pintype "passive"))
      (node (ref "Q48") (pin "4") (pinfunction "G_4") (pintype "passive"))
      (node (ref "U26") (pin "3") (pinfunction "BG_3") (pintype "passive"))
    )
    (net (code "53") (name "/PWM1H") (class "Default")
      (node (ref "U12") (pin "5") (pinfunction "IN_5") (pintype "passive"))
      (node (ref "U14") (pin "5") (pinfunction "IN_5") (pintype "passive"))
    )
    (net (code "54") (name "/PWM1L") (class "Default")
      (node (ref "U11") (pin "5") (pinfunction "IN_5") (pintype "passive"))
      (node (ref "U13") (pin "5") (pinfunction "IN_5") (pintype "passive"))
    )
    (net (code "55") (name "/PWM2H") (class "Default")
      (node (ref "U16") (pin "5") (pinfunction "IN_5") (pintype "passive"))
      (node (ref "U18") (pin "5") (pinfunction "IN_5") (pintype "passive"))
    )
    (net (code "56") (name "/PWM2L") (class "Default")
      (node (ref "U15") (pin "5") (pinfunction "IN_5") (pintype "passive"))
      (node (ref "U17") (pin "5") (pinfunction "IN_5") (pintype "passive"))
    )
    (net (code "57") (name "/PWM3H") (class "Default")
      (node (ref "U20") (pin "5") (pinfunction "IN_5") (pintype "passive"))
      (node (ref "U22") (pin "5") (pinfunction "IN_5") (pintype "passive"))
    )
    (net (code "58") (name "/PWM3L") (class "Default")
      (node (ref "U19") (pin "5") (pinfunction "IN_5") (pintype "passive"))
      (node (ref "U21") (pin "5") (pinfunction "IN_5") (pintype "passive"))
    )
    (net (code "59") (name "/PWM4H") (class "Default")
      (node (ref "U24") (pin "5") (pinfunction "IN_5") (pintype "passive"))
      (node (ref "U26") (pin "5") (pinfunction "IN_5") (pintype "passive"))
    )
    (net (code "60") (name "/PWM4L") (class "Default")
      (node (ref "U23") (pin "5") (pinfunction "IN_5") (pintype "passive"))
      (node (ref "U25") (pin "5") (pinfunction "IN_5") (pintype "passive"))
    )
    (net (code "61") (name "/SWN1") (class "Default")
      (node (ref "C28") (pin "2") (pinfunction "2_2") (pintype "passive"))
      (node (ref "L1") (pin "1") (pinfunction "1_1") (pintype "passive"))
      (node (ref "Q1") (pin "1") (pinfunction "S_1") (pintype "passive"))
      (node (ref "Q1") (pin "2") (pinfunction "S_2") (pintype "passive"))
      (node (ref "Q1") (pin "3") (pinfunction "S_3") (pintype "passive"))
      (node (ref "Q5") (pin "5") (pinfunction "D_5") (pintype "passive"))
      (node (ref "Q5") (pin "6") (pinfunction "D_6") (pintype "passive"))
      (node (ref "Q5") (pin "7") (pinfunction "D_7") (pintype "passive"))
      (node (ref "Q5") (pin "8") (pinfunction "D_8") (pintype "passive"))
      (node (ref "Q6") (pin "5") (pinfunction "D_5") (pintype "passive"))
      (node (ref "Q6") (pin "6") (pinfunction "D_6") (pintype "passive"))
      (node (ref "Q6") (pin "7") (pinfunction "D_7") (pintype "passive"))
      (node (ref "Q6") (pin "8") (pinfunction "D_8") (pintype "passive"))
      (node (ref "U11") (pin "2") (pinfunction "TS_2") (pintype "passive"))
    )
    (net (code "62") (name "/SWN2") (class "Default")
      (node (ref "C60") (pin "2") (pinfunction "2_2") (pintype "passive"))
      (node (ref "L5") (pin "1") (pinfunction "1_1") (pintype "passive"))
      (node (ref "Q13") (pin "1") (pinfunction "S_1") (pintype "passive"))
      (node (ref "Q13") (pin "2") (pinfunction "S_2") (pintype "passive"))
      (node (ref "Q13") (pin "3") (pinfunction "S_3") (pintype "passive"))
      (node (ref "Q17") (pin "5") (pinfunction "D_5") (pintype "passive"))
      (node (ref "Q17") (pin "6") (pinfunction "D_6") (pintype "passive"))
      (node (ref "Q17") (pin "7") (pinfunction "D_7") (pintype "passive"))
      (node (ref "Q17") (pin "8") (pinfunction "D_8") (pintype "passive"))
      (node (ref "Q18") (pin "5") (pinfunction "D_5") (pintype "passive"))
      (node (ref "Q18") (pin "6") (pinfunction "D_6") (pintype "passive"))
      (node (ref "Q18") (pin "7") (pinfunction "D_7") (pintype "passive"))
      (node (ref "Q18") (pin "8") (pinfunction "D_8") (pintype "passive"))
      (node (ref "U15") (pin "2") (pinfunction "TS_2") (pintype "passive"))
    )
    (net (code "63") (name "/SWN3") (class "Default")
      (node (ref "C92") (pin "2") (pinfunction "2_2") (pintype "passive"))
      (node (ref "L9") (pin "1") (pinfunction "1_1") (pintype "passive"))
      (node (ref "Q25") (pin "1") (pinfunction "S_1") (pintype "passive"))
      (node (ref "Q25") (pin "2") (pinfunction "S_2") (pintype "passive"))
      (node (ref "Q25") (pin "3") (pinfunction "S_3") (pintype "passive"))
      (node (ref "Q29") (pin "5") (pinfunction "D_5") (pintype "passive"))
      (node (ref "Q29") (pin "6") (pinfunction "D_6") (pintype "passive"))
      (node (ref "Q29") (pin "7") (pinfunction "D_7") (pintype "passive"))
      (node (ref "Q29") (pin "8") (pinfunction "D_8") (pintype "passive"))
      (node (ref "Q30") (pin "5") (pinfunction "D_5") (pintype "passive"))
      (node (ref "Q30") (pin "6") (pinfunction "D_6") (pintype "passive"))
      (node (ref "Q30") (pin "7") (pinfunction "D_7") (pintype "passive"))
      (node (ref "Q30") (pin "8") (pinfunction "D_8") (pintype "passive"))
      (node (ref "U19") (pin "2") (pinfunction "TS_2") (pintype "passive"))
    )
    (net (code "64") (name "/SWN4") (class "Default")
      (node (ref "C124") (pin "2") (pinfunction "2_2") (pintype "passive"))
      (node (ref "L13") (pin "1") (pinfunction "1_1") (pintype "passive"))
      (node (ref "Q37") (pin "1") (pinfunction "S_1") (pintype "passive"))
      (node (ref "Q37") (pin "2") (pinfunction "S_2") (pintype "passive"))
      (node (ref "Q37") (pin "3") (pinfunction "S_3") (pintype "passive"))
      (node (ref "Q41") (pin "5") (pinfunction "D_5") (pintype "passive"))
      (node (ref "Q41") (pin "6") (pinfunction "D_6") (pintype "passive"))
      (node (ref "Q41") (pin "7") (pinfunction "D_7") (pintype "passive"))
      (node (ref "Q41") (pin "8") (pinfunction "D_8") (pintype "passive"))
      (node (ref "Q42") (pin "5") (pinfunction "D_5") (pintype "passive"))
      (node (ref "Q42") (pin "6") (pinfunction "D_6") (pintype "passive"))
      (node (ref "Q42") (pin "7") (pinfunction "D_7") (pintype "passive"))
      (node (ref "Q42") (pin "8") (pinfunction "D_8") (pintype "passive"))
      (node (ref "U23") (pin "2") (pinfunction "TS_2") (pintype "passive"))
    )
    (net (code "65") (name "/SWN5") (class "Default")
      (node (ref "C29") (pin "2") (pinfunction "2_2") (pintype "passive"))
      (node (ref "L2") (pin "1") (pinfunction "1_1") (pintype "passive"))
      (node (ref "Q2") (pin "1") (pinfunction "S_1") (pintype "passive"))
      (node (ref "Q2") (pin "2") (pinfunction "S_2") (pintype "passive"))
      (node (ref "Q2") (pin "3") (pinfunction "S_3") (pintype "passive"))
      (node (ref "Q7") (pin "5") (pinfunction "D_5") (pintype "passive"))
      (node (ref "Q7") (pin "6") (pinfunction "D_6") (pintype "passive"))
      (node (ref "Q7") (pin "7") (pinfunction "D_7") (pintype "passive"))
      (node (ref "Q7") (pin "8") (pinfunction "D_8") (pintype "passive"))
      (node (ref "Q8") (pin "5") (pinfunction "D_5") (pintype "passive"))
      (node (ref "Q8") (pin "6") (pinfunction "D_6") (pintype "passive"))
      (node (ref "Q8") (pin "7") (pinfunction "D_7") (pintype "passive"))
      (node (ref "Q8") (pin "8") (pinfunction "D_8") (pintype "passive"))
      (node (ref "U12") (pin "2") (pinfunction "TS_2") (pintype "passive"))
    )
    (net (code "66") (name "/SWN6") (class "Default")
      (node (ref "C61") (pin "2") (pinfunction "2_2") (pintype "passive"))
      (node (ref "L6") (pin "1") (pinfunction "1_1") (pintype "passive"))
      (node (ref "Q14") (pin "1") (pinfunction "S_1") (pintype "passive"))
      (node (ref "Q14") (pin "2") (pinfunction "S_2") (pintype "passive"))
      (node (ref "Q14") (pin "3") (pinfunction "S_3") (pintype "passive"))
      (node (ref "Q19") (pin "5") (pinfunction "D_5") (pintype "passive"))
      (node (ref "Q19") (pin "6") (pinfunction "D_6") (pintype "passive"))
      (node (ref "Q19") (pin "7") (pinfunction "D_7") (pintype "passive"))
      (node (ref "Q19") (pin "8") (pinfunction "D_8") (pintype "passive"))
      (node (ref "Q20") (pin "5") (pinfunction "D_5") (pintype "passive"))
      (node (ref "Q20") (pin "6") (pinfunction "D_6") (pintype "passive"))
      (node (ref "Q20") (pin "7") (pinfunction "D_7") (pintype "passive"))
      (node (ref "Q20") (pin "8") (pinfunction "D_8") (pintype "passive"))
      (node (ref "U16") (pin "2") (pinfunction "TS_2") (pintype "passive"))
    )
    (net (code "67") (name "/SWN7") (class "Default")
      (node (ref "C93") (pin "2") (pinfunction "2_2") (pintype "passive"))
      (node (ref "L10") (pin "1") (pinfunction "1_1") (pintype "passive"))
      (node (ref "Q26") (pin "1") (pinfunction "S_1") (pintype "passive"))
      (node (ref "Q26") (pin "2") (pinfunction "S_2") (pintype "passive"))
      (node (ref "Q26") (pin "3") (pinfunction "S_3") (pintype "passive"))
      (node (ref "Q31") (pin "5") (pinfunction "D_5") (pintype "passive"))
      (node (ref "Q31") (pin "6") (pinfunction "D_6") (pintype "passive"))
      (node (ref "Q31") (pin "7") (pinfunction "D_7") (pintype "passive"))
      (node (ref "Q31") (pin "8") (pinfunction "D_8") (pintype "passive"))
      (node (ref "Q32") (pin "5") (pinfunction "D_5") (pintype "passive"))
      (node (ref "Q32") (pin "6") (pinfunction "D_6") (pintype "passive"))
      (node (ref "Q32") (pin "7") (pinfunction "D_7") (pintype "passive"))
      (node (ref "Q32") (pin "8") (pinfunction "D_8") (pintype "passive"))
      (node (ref "U20") (pin "2") (pinfunction "TS_2") (pintype "passive"))
    )
    (net (code "68") (name "/SWN8") (class "Default")
      (node (ref "C125") (pin "2") (pinfunction "2_2") (pintype "passive"))
      (node (ref "L14") (pin "1") (pinfunction "1_1") (pintype "passive"))
      (node (ref "Q38") (pin "1") (pinfunction "S_1") (pintype "passive"))
      (node (ref "Q38") (pin "2") (pinfunction "S_2") (pintype "passive"))
      (node (ref "Q38") (pin "3") (pinfunction "S_3") (pintype "passive"))
      (node (ref "Q43") (pin "5") (pinfunction "D_5") (pintype "passive"))
      (node (ref "Q43") (pin "6") (pinfunction "D_6") (pintype "passive"))
      (node (ref "Q43") (pin "7") (pinfunction "D_7") (pintype "passive"))
      (node (ref "Q43") (pin "8") (pinfunction "D_8") (pintype "passive"))
      (node (ref "Q44") (pin "5") (pinfunction "D_5") (pintype "passive"))
      (node (ref "Q44") (pin "6") (pinfunction "D_6") (pintype "passive"))
      (node (ref "Q44") (pin "7") (pinfunction "D_7") (pintype "passive"))
      (node (ref "Q44") (pin "8") (pinfunction "D_8") (pintype "passive"))
      (node (ref "U24") (pin "2") (pinfunction "TS_2") (pintype "passive"))
    )
    (net (code "69") (name "/SWN9") (class "Default")
      (node (ref "C30") (pin "2") (pinfunction "2_2") (pintype "passive"))
      (node (ref "L3") (pin "1") (pinfunction "1_1") (pintype "passive"))
      (node (ref "Q10") (pin "5") (pinfunction "D_5") (pintype "passive"))
      (node (ref "Q10") (pin "6") (pinfunction "D_6") (pintype "passive"))
      (node (ref "Q10") (pin "7") (pinfunction "D_7") (pintype "passive"))
      (node (ref "Q10") (pin "8") (pinfunction "D_8") (pintype "passive"))
      (node (ref "Q3") (pin "1") (pinfunction "S_1") (pintype "passive"))
      (node (ref "Q3") (pin "2") (pinfunction "S_2") (pintype "passive"))
      (node (ref "Q3") (pin "3") (pinfunction "S_3") (pintype "passive"))
      (node (ref "Q9") (pin "5") (pinfunction "D_5") (pintype "passive"))
      (node (ref "Q9") (pin "6") (pinfunction "D_6") (pintype "passive"))
      (node (ref "Q9") (pin "7") (pinfunction "D_7") (pintype "passive"))
      (node (ref "Q9") (pin "8") (pinfunction "D_8") (pintype "passive"))
      (node (ref "U13") (pin "2") (pinfunction "TS_2") (pintype "passive"))
    )
    (net (code "70") (name "/SWN10") (class "Default")
      (node (ref "C62") (pin "2") (pinfunction "2_2") (pintype "passive"))
      (node (ref "L7") (pin "1") (pinfunction "1_1") (pintype "passive"))
      (node (ref "Q15") (pin "1") (pinfunction "S_1") (pintype "passive"))
      (node (ref "Q15") (pin "2") (pinfunction "S_2") (pintype "passive"))
      (node (ref "Q15") (pin "3") (pinfunction "S_3") (pintype "passive"))
      (node (ref "Q21") (pin "5") (pinfunction "D_5") (pintype "passive"))
      (node (ref "Q21") (pin "6") (pinfunction "D_6") (pintype "passive"))
      (node (ref "Q21") (pin "7") (pinfunction "D_7") (pintype "passive"))
      (node (ref "Q21") (pin "8") (pinfunction "D_8") (pintype "passive"))
      (node (ref "Q22") (pin "5") (pinfunction "D_5") (pintype "passive"))
      (node (ref "Q22") (pin "6") (pinfunction "D_6") (pintype "passive"))
      (node (ref "Q22") (pin "7") (pinfunction "D_7") (pintype "passive"))
      (node (ref "Q22") (pin "8") (pinfunction "D_8") (pintype "passive"))
      (node (ref "U17") (pin "2") (pinfunction "TS_2") (pintype "passive"))
    )
    (net (code "71") (name "/SWN11") (class "Default")
      (node (ref "C94") (pin "2") (pinfunction "2_2") (pintype "passive"))
      (node (ref "L11") (pin "1") (pinfunction "1_1") (pintype "passive"))
      (node (ref "Q27") (pin "1") (pinfunction "S_1") (pintype "passive"))
      (node (ref "Q27") (pin "2") (pinfunction "S_2") (pintype "passive"))
      (node (ref "Q27") (pin "3") (pinfunction "S_3") (pintype "passive"))
      (node (ref "Q33") (pin "5") (pinfunction "D_5") (pintype "passive"))
      (node (ref "Q33") (pin "6") (pinfunction "D_6") (pintype "passive"))
      (node (ref "Q33") (pin "7") (pinfunction "D_7") (pintype "passive"))
      (node (ref "Q33") (pin "8") (pinfunction "D_8") (pintype "passive"))
      (node (ref "Q34") (pin "5") (pinfunction "D_5") (pintype "passive"))
      (node (ref "Q34") (pin "6") (pinfunction "D_6") (pintype "passive"))
      (node (ref "Q34") (pin "7") (pinfunction "D_7") (pintype "passive"))
      (node (ref "Q34") (pin "8") (pinfunction "D_8") (pintype "passive"))
      (node (ref "U21") (pin "2") (pinfunction "TS_2") (pintype "passive"))
    )
    (net (code "72") (name "/SWN12") (class "Default")
      (node (ref "C126") (pin "2") (pinfunction "2_2") (pintype "passive"))
      (node (ref "L15") (pin "1") (pinfunction "1_1") (pintype "passive"))
      (node (ref "Q39") (pin "1") (pinfunction "S_1") (pintype "passive"))
      (node (ref "Q39") (pin "2") (pinfunction "S_2") (pintype "passive"))
      (node (ref "Q39") (pin "3") (pinfunction "S_3") (pintype "passive"))
      (node (ref "Q45") (pin "5") (pinfunction "D_5") (pintype "passive"))
      (node (ref "Q45") (pin "6") (pinfunction "D_6") (pintype "passive"))
      (node (ref "Q45") (pin "7") (pinfunction "D_7") (pintype "passive"))
      (node (ref "Q45") (pin "8") (pinfunction "D_8") (pintype "passive"))
      (node (ref "Q46") (pin "5") (pinfunction "D_5") (pintype "passive"))
      (node (ref "Q46") (pin "6") (pinfunction "D_6") (pintype "passive"))
      (node (ref "Q46") (pin "7") (pinfunction "D_7") (pintype "passive"))
      (node (ref "Q46") (pin "8") (pinfunction "D_8") (pintype "passive"))
      (node (ref "U25") (pin "2") (pinfunction "TS_2") (pintype "passive"))
    )
    (net (code "73") (name "/SWN13") (class "Default")
      (node (ref "C31") (pin "2") (pinfunction "2_2") (pintype "passive"))
      (node (ref "L4") (pin "1") (pinfunction "1_1") (pintype "passive"))
      (node (ref "Q11") (pin "5") (pinfunction "D_5") (pintype "passive"))
      (node (ref "Q11") (pin "6") (pinfunction "D_6") (pintype "passive"))
      (node (ref "Q11") (pin "7") (pinfunction "D_7") (pintype "passive"))
      (node (ref "Q11") (pin "8") (pinfunction "D_8") (pintype "passive"))
      (node (ref "Q12") (pin "5") (pinfunction "D_5") (pintype "passive"))
      (node (ref "Q12") (pin "6") (pinfunction "D_6") (pintype "passive"))
      (node (ref "Q12") (pin "7") (pinfunction "D_7") (pintype "passive"))
      (node (ref "Q12") (pin "8") (pinfunction "D_8") (pintype "passive"))
      (node (ref "Q4") (pin "1") (pinfunction "S_1") (pintype "passive"))
      (node (ref "Q4") (pin "2") (pinfunction "S_2") (pintype "passive"))
      (node (ref "Q4") (pin "3") (pinfunction "S_3") (pintype "passive"))
      (node (ref "U14") (pin "2") (pinfunction "TS_2") (pintype "passive"))
    )
    (net (code "74") (name "/SWN14") (class "Default")
      (node (ref "C63") (pin "2") (pinfunction "2_2") (pintype "passive"))
      (node (ref "L8") (pin "1") (pinfunction "1_1") (pintype "passive"))
      (node (ref "Q16") (pin "1") (pinfunction "S_1") (pintype "passive"))
      (node (ref "Q16") (pin "2") (pinfunction "S_2") (pintype "passive"))
      (node (ref "Q16") (pin "3") (pinfunction "S_3") (pintype "passive"))
      (node (ref "Q23") (pin "5") (pinfunction "D_5") (pintype "passive"))
      (node (ref "Q23") (pin "6") (pinfunction "D_6") (pintype "passive"))
      (node (ref "Q23") (pin "7") (pinfunction "D_7") (pintype "passive"))
      (node (ref "Q23") (pin "8") (pinfunction "D_8") (pintype "passive"))
      (node (ref "Q24") (pin "5") (pinfunction "D_5") (pintype "passive"))
      (node (ref "Q24") (pin "6") (pinfunction "D_6") (pintype "passive"))
      (node (ref "Q24") (pin "7") (pinfunction "D_7") (pintype "passive"))
      (node (ref "Q24") (pin "8") (pinfunction "D_8") (pintype "passive"))
      (node (ref "U18") (pin "2") (pinfunction "TS_2") (pintype "passive"))
    )
    (net (code "75") (name "/SWN15") (class "Default")
      (node (ref "C95") (pin "2") (pinfunction "2_2") (pintype "passive"))
      (node (ref "L12") (pin "1") (pinfunction "1_1") (pintype "passive"))
      (node (ref "Q28") (pin "1") (pinfunction "S_1") (pintype "passive"))
      (node (ref "Q28") (pin "2") (pinfunction "S_2") (pintype "passive"))
      (node (ref "Q28") (pin "3") (pinfunction "S_3") (pintype "passive"))
      (node (ref "Q35") (pin "5") (pinfunction "D_5") (pintype "passive"))
      (node (ref "Q35") (pin "6") (pinfunction "D_6") (pintype "passive"))
      (node (ref "Q35") (pin "7") (pinfunction "D_7") (pintype "passive"))
      (node (ref "Q35") (pin "8") (pinfunction "D_8") (pintype "passive"))
      (node (ref "Q36") (pin "5") (pinfunction "D_5") (pintype "passive"))
      (node (ref "Q36") (pin "6") (pinfunction "D_6") (pintype "passive"))
      (node (ref "Q36") (pin "7") (pinfunction "D_7") (pintype "passive"))
      (node (ref "Q36") (pin "8") (pinfunction "D_8") (pintype "passive"))
      (node (ref "U22") (pin "2") (pinfunction "TS_2") (pintype "passive"))
    )
    (net (code "76") (name "/SWN16") (class "Default")
      (node (ref "C127") (pin "2") (pinfunction "2_2") (pintype "passive"))
      (node (ref "L16") (pin "1") (pinfunction "1_1") (pintype "passive"))
      (node (ref "Q40") (pin "1") (pinfunction "S_1") (pintype "passive"))
      (node (ref "Q40") (pin "2") (pinfunction "S_2") (pintype "passive"))
      (node (ref "Q40") (pin "3") (pinfunction "S_3") (pintype "passive"))
      (node (ref "Q47") (pin "5") (pinfunction "D_5") (pintype "passive"))
      (node (ref "Q47") (pin "6") (pinfunction "D_6") (pintype "passive"))
      (node (ref "Q47") (pin "7") (pinfunction "D_7") (pintype "passive"))
      (node (ref "Q47") (pin "8") (pinfunction "D_8") (pintype "passive"))
      (node (ref "Q48") (pin "5") (pinfunction "D_5") (pintype "passive"))
      (node (ref "Q48") (pin "6") (pinfunction "D_6") (pintype "passive"))
      (node (ref "Q48") (pin "7") (pinfunction "D_7") (pintype "passive"))
      (node (ref "Q48") (pin "8") (pinfunction "D_8") (pintype "passive"))
      (node (ref "U26") (pin "2") (pinfunction "TS_2") (pintype "passive"))
    )
    (net (code "77") (name "GND") (class "Default")
      (node (ref "C100") (pin "1") (pinfunction "1_1") (pintype "passive"))
      (node (ref "C101") (pin "1") (pinfunction "1_1") (pintype "passive"))
      (node (ref "C102") (pin "1") (pinfunction "1_1") (pintype "passive"))
      (node (ref "C103") (pin "1") (pinfunction "1_1") (pintype "passive"))
      (node (ref "C104") (pin "1") (pinfunction "1_1") (pintype "passive"))
      (node (ref "C105") (pin "1") (pinfunction "1_1") (pintype "passive"))
      (node (ref "C106") (pin "1") (pinfunction "1_1") (pintype "passive"))
      (node (ref "C107") (pin "1") (pinfunction "1_1") (pintype "passive"))
      (node (ref "C108") (pin "1") (pinfunction "1_1") (pintype "passive"))
      (node (ref "C109") (pin "1") (pinfunction "1_1") (pintype "passive"))
      (node (ref "C110") (pin "1") (pinfunction "1_1") (pintype "passive"))
      (node (ref "C111") (pin "1") (pinfunction "1_1") (pintype "passive"))
      (node (ref "C112") (pin "1") (pinfunction "1_1") (pintype "passive"))
      (node (ref "C113") (pin "1") (pinfunction "1_1") (pintype "passive"))
      (node (ref "C114") (pin "1") (pinfunction "1_1") (pintype "passive"))
      (node (ref "C115") (pin "1") (pinfunction "1_1") (pintype "passive"))
      (node (ref "C116") (pin "1") (pinfunction "1_1") (pintype "passive"))
      (node (ref "C117") (pin "1") (pinfunction "1_1") (pintype "passive"))
      (node (ref "C118") (pin "1") (pinfunction "1_1") (pintype "passive"))
      (node (ref "C119") (pin "1") (pinfunction "1_1") (pintype "passive"))
      (node (ref "C120") (pin "2") (pinfunction "2_2") (pintype "passive"))
      (node (ref "C121") (pin "2") (pinfunction "2_2") (pintype "passive"))
      (node (ref "C122") (pin "2") (pinfunction "2_2") (pintype "passive"))
      (node (ref "C123") (pin "2") (pinfunction "2_2") (pintype "passive"))
      (node (ref "C128") (pin "1") (pinfunction "1_1") (pintype "passive"))
      (node (ref "C129") (pin "1") (pinfunction "1_1") (pintype "passive"))
      (node (ref "C130") (pin "1") (pinfunction "1_1") (pintype "passive"))
      (node (ref "C131") (pin "1") (pinfunction "1_1") (pintype "passive"))
      (node (ref "C132") (pin "1") (pinfunction "1_1") (pintype "passive"))
      (node (ref "C133") (pin "1") (pinfunction "1_1") (pintype "passive"))
      (node (ref "C134") (pin "1") (pinfunction "1_1") (pintype "passive"))
      (node (ref "C135") (pin "1") (pinfunction "1_1") (pintype "passive"))
      (node (ref "C136") (pin "1") (pinfunction "1_1") (pintype "passive"))
      (node (ref "C137") (pin "1") (pinfunction "1_1") (pintype "passive"))
      (node (ref "C138") (pin "1") (pinfunction "1_1") (pintype "passive"))
      (node (ref "C139") (pin "1") (pinfunction "1_1") (pintype "passive"))
      (node (ref "C140") (pin "1") (pinfunction "1_1") (pintype "passive"))
      (node (ref "C141") (pin "1") (pinfunction "1_1") (pintype "passive"))
      (node (ref "C142") (pin "1") (pinfunction "1_1") (pintype "passive"))
      (node (ref "C143") (pin "1") (pinfunction "1_1") (pintype "passive"))
      (node (ref "C144") (pin "1") (pinfunction "1_1") (pintype "passive"))
      (node (ref "C145") (pin "1") (pinfunction "1_1") (pintype "passive"))
      (node (ref "C146") (pin "1") (pinfunction "1_1") (pintype "passive"))
      (node (ref "C147") (pin "1") (pinfunction "1_1") (pintype "passive"))
      (node (ref "C20") (pin "1") (pinfunction "1_1") (pintype "passive"))
      (node (ref "C21") (pin "1") (pinfunction "1_1") (pintype "passive"))
      (node (ref "C22") (pin "1") (pinfunction "1_1") (pintype "passive"))
      (node (ref "C23") (pin "1") (pinfunction "1_1") (pintype "passive"))
      (node (ref "C236") (pin "1") (pinfunction "1_1") (pintype "passive"))
      (node (ref "C24") (pin "2") (pinfunction "2_2") (pintype "passive"))
      (node (ref "C25") (pin "2") (pinfunction "2_2") (pintype "passive"))
      (node (ref "C26") (pin "2") (pinfunction "2_2") (pintype "passive"))
      (node (ref "C27") (pin "2") (pinfunction "2_2") (pintype "passive"))
      (node (ref "C32") (pin "1") (pinfunction "1_1") (pintype "passive"))
      (node (ref "C33") (pin "1") (pinfunction "1_1") (pintype "passive"))
      (node (ref "C34") (pin "1") (pinfunction "1_1") (pintype "passive"))
      (node (ref "C348") (pin "1") (pinfunction "1_1") (pintype "passive"))
      (node (ref "C349") (pin "1") (pinfunction "1_1") (pintype "passive"))
      (node (ref "C35") (pin "1") (pinfunction "1_1") (pintype "passive"))
      (node (ref "C350") (pin "1") (pinfunction "1_1") (pintype "passive"))
      (node (ref "C351") (pin "1") (pinfunction "1_1") (pintype "passive"))
      (node (ref "C352") (pin "1") (pinfunction "1_1") (pintype "passive"))
      (node (ref "C353") (pin "1") (pinfunction "1_1") (pintype "passive"))
      (node (ref "C354") (pin "1") (pinfunction "1_1") (pintype "passive"))
      (node (ref "C355") (pin "1") (pinfunction "1_1") (pintype "passive"))
      (node (ref "C356") (pin "1") (pinfunction "1_1") (pintype "passive"))
      (node (ref "C357") (pin "1") (pinfunction "1_1") (pintype "passive"))
      (node (ref "C358") (pin "1") (pinfunction "1_1") (pintype "passive"))
      (node (ref "C359") (pin "1") (pinfunction "1_1") (pintype "passive"))
      (node (ref "C360") (pin "1") (pinfunction "1_1") (pintype "passive"))
      (node (ref "C361") (pin "1") (pinfunction "1_1") (pintype "passive"))
      (node (ref "C362") (pin "1") (pinfunction "1_1") (pintype "passive"))
      (node (ref "C363") (pin "1") (pinfunction "1_1") (pintype "passive"))
      (node (ref "C364") (pin "1") (pinfunction "1_1") (pintype "passive"))
      (node (ref "C365") (pin "1") (pinfunction "1_1") (pintype "passive"))
      (node (ref "C366") (pin "1") (pinfunction "1_1") (pintype "passive"))
      (node (ref "C367") (pin "1") (pinfunction "1_1") (pintype "passive"))
      (node (ref "C368") (pin "1") (pinfunction "1_1") (pintype "passive"))
      (node (ref "C369") (pin "1") (pinfunction "1_1") (pintype "passive"))
      (node (ref "C37") (pin "1") (pinfunction "1_1") (pintype "passive"))
      (node (ref "C370") (pin "1") (pinfunction "1_1") (pintype "passive"))
      (node (ref "C371") (pin "1") (pinfunction "1_1") (pintype "passive"))
      (node (ref "C372") (pin "1") (pinfunction "1_1") (pintype "passive"))
      (node (ref "C373") (pin "1") (pinfunction "1_1") (pintype "passive"))
      (node (ref "C374") (pin "1") (pinfunction "1_1") (pintype "passive"))
      (node (ref "C375") (pin "1") (pinfunction "1_1") (pintype "passive"))
      (node (ref "C376") (pin "1") (pinfunction "1_1") (pintype "passive"))
      (node (ref "C377") (pin "1") (pinfunction "1_1") (pintype "passive"))
      (node (ref "C378") (pin "1") (pinfunction "1_1") (pintype "passive"))
      (node (ref "C379") (pin "1") (pinfunction "1_1") (pintype "passive"))
      (node (ref "C38") (pin "1") (pinfunction "1_1") (pintype "passive"))
      (node (ref "C380") (pin "1") (pinfunction "1_1") (pintype "passive"))
      (node (ref "C381") (pin "1") (pinfunction "1_1") (pintype "passive"))
      (node (ref "C382") (pin "1") (pinfunction "1_1") (pintype "passive"))
      (node (ref "C383") (pin "1") (pinfunction "1_1") (pintype "passive"))
      (node (ref "C384") (pin "1") (pinfunction "1_1") (pintype "passive"))
      (node (ref "C385") (pin "1") (pinfunction "1_1") (pintype "passive"))
      (node (ref "C386") (pin "1") (pinfunction "1_1") (pintype "passive"))
      (node (ref "C387") (pin "1") (pinfunction "1_1") (pintype "passive"))
      (node (ref "C388") (pin "1") (pinfunction "1_1") (pintype "passive"))
      (node (ref "C389") (pin "1") (pinfunction "1_1") (pintype "passive"))
      (node (ref "C39") (pin "1") (pinfunction "1_1") (pintype "passive"))
      (node (ref "C390") (pin "1") (pinfunction "1_1") (pintype "passive"))
      (node (ref "C391") (pin "1") (pinfunction "1_1") (pintype "passive"))
      (node (ref "C392") (pin "1") (pinfunction "1_1") (pintype "passive"))
      (node (ref "C393") (pin "1") (pinfunction "1_1") (pintype "passive"))
      (node (ref "C394") (pin "1") (pinfunction "1_1") (pintype "passive"))
      (node (ref "C395") (pin "1") (pinfunction "1_1") (pintype "passive"))
      (node (ref "C396") (pin "1") (pinfunction "1_1") (pintype "passive"))
      (node (ref "C397") (pin "1") (pinfunction "1_1") (pintype "passive"))
      (node (ref "C398") (pin "1") (pinfunction "1_1") (pintype "passive"))
      (node (ref "C399") (pin "1") (pinfunction "1_1") (pintype "passive"))
      (node (ref "C40") (pin "1") (pinfunction "1_1") (pintype "passive"))
      (node (ref "C400") (pin "1") (pinfunction "1_1") (pintype "passive"))
      (node (ref "C401") (pin "1") (pinfunction "1_1") (pintype "passive"))
      (node (ref "C402") (pin "1") (pinfunction "1_1") (pintype "passive"))
      (node (ref "C403") (pin "1") (pinfunction "1_1") (pintype "passive"))
      (node (ref "C404") (pin "1") (pinfunction "1_1") (pintype "passive"))
      (node (ref "C405") (pin "1") (pinfunction "1_1") (pintype "passive"))
      (node (ref "C406") (pin "1") (pinfunction "1_1") (pintype "passive"))
      (node (ref "C407") (pin "1") (pinfunction "1_1") (pintype "passive"))
      (node (ref "C408") (pin "1") (pinfunction "1_1") (pintype "passive"))
      (node (ref "C409") (pin "1") (pinfunction "1_1") (pintype "passive"))
      (node (ref "C41") (pin "1") (pinfunction "1_1") (pintype "passive"))
      (node (ref "C410") (pin "1") (pinfunction "1_1") (pintype "passive"))
      (node (ref "C411") (pin "1") (pinfunction "1_1") (pintype "passive"))
      (node (ref "C412") (pin "1") (pinfunction "1_1") (pintype "passive"))
      (node (ref "C413") (pin "1") (pinfunction "1_1") (pintype "passive"))
      (node (ref "C414") (pin "1") (pinfunction "1_1") (pintype "passive"))
      (node (ref "C415") (pin "1") (pinfunction "1_1") (pintype "passive"))
      (node (ref "C416") (pin "1") (pinfunction "1_1") (pintype "passive"))
      (node (ref "C417") (pin "1") (pinfunction "1_1") (pintype "passive"))
      (node (ref "C418") (pin "1") (pinfunction "1_1") (pintype "passive"))
      (node (ref "C419") (pin "1") (pinfunction "1_1") (pintype "passive"))
      (node (ref "C42") (pin "1") (pinfunction "1_1") (pintype "passive"))
      (node (ref "C420") (pin "1") (pinfunction "1_1") (pintype "passive"))
      (node (ref "C421") (pin "1") (pinfunction "1_1") (pintype "passive"))
      (node (ref "C422") (pin "1") (pinfunction "1_1") (pintype "passive"))
      (node (ref "C423") (pin "1") (pinfunction "1_1") (pintype "passive"))
      (node (ref "C424") (pin "1") (pinfunction "1_1") (pintype "passive"))
      (node (ref "C425") (pin "1") (pinfunction "1_1") (pintype "passive"))
      (node (ref "C426") (pin "1") (pinfunction "1_1") (pintype "passive"))
      (node (ref "C427") (pin "1") (pinfunction "1_1") (pintype "passive"))
      (node (ref "C43") (pin "1") (pinfunction "1_1") (pintype "passive"))
      (node (ref "C44") (pin "1") (pinfunction "1_1") (pintype "passive"))
      (node (ref "C45") (pin "1") (pinfunction "1_1") (pintype "passive"))
      (node (ref "C46") (pin "1") (pinfunction "1_1") (pintype "passive"))
      (node (ref "C47") (pin "1") (pinfunction "1_1") (pintype "passive"))
      (node (ref "C48") (pin "1") (pinfunction "1_1") (pintype "passive"))
      (node (ref "C49") (pin "1") (pinfunction "1_1") (pintype "passive"))
      (node (ref "C50") (pin "1") (pinfunction "1_1") (pintype "passive"))
      (node (ref "C51") (pin "1") (pinfunction "1_1") (pintype "passive"))
      (node (ref "C52") (pin "1") (pinfunction "1_1") (pintype "passive"))
      (node (ref "C53") (pin "1") (pinfunction "1_1") (pintype "passive"))
      (node (ref "C54") (pin "1") (pinfunction "1_1") (pintype "passive"))
      (node (ref "C55") (pin "1") (pinfunction "1_1") (pintype "passive"))
      (node (ref "C56") (pin "2") (pinfunction "2_2") (pintype "passive"))
      (node (ref "C57") (pin "2") (pinfunction "2_2") (pintype "passive"))
      (node (ref "C58") (pin "2") (pinfunction "2_2") (pintype "passive"))
      (node (ref "C59") (pin "2") (pinfunction "2_2") (pintype "passive"))
      (node (ref "C64") (pin "1") (pinfunction "1_1") (pintype "passive"))
      (node (ref "C65") (pin "1") (pinfunction "1_1") (pintype "passive"))
      (node (ref "C66") (pin "1") (pinfunction "1_1") (pintype "passive"))
      (node (ref "C67") (pin "1") (pinfunction "1_1") (pintype "passive"))
      (node (ref "C68") (pin "1") (pinfunction "1_1") (pintype "passive"))
      (node (ref "C69") (pin "1") (pinfunction "1_1") (pintype "passive"))
      (node (ref "C70") (pin "1") (pinfunction "1_1") (pintype "passive"))
      (node (ref "C71") (pin "1") (pinfunction "1_1") (pintype "passive"))
      (node (ref "C72") (pin "1") (pinfunction "1_1") (pintype "passive"))
      (node (ref "C73") (pin "1") (pinfunction "1_1") (pintype "passive"))
      (node (ref "C74") (pin "1") (pinfunction "1_1") (pintype "passive"))
      (node (ref "C75") (pin "1") (pinfunction "1_1") (pintype "passive"))
      (node (ref "C76") (pin "1") (pinfunction "1_1") (pintype "passive"))
      (node (ref "C77") (pin "1") (pinfunction "1_1") (pintype "passive"))
      (node (ref "C78") (pin "1") (pinfunction "1_1") (pintype "passive"))
      (node (ref "C79") (pin "1") (pinfunction "1_1") (pintype "passive"))
      (node (ref "C80") (pin "1") (pinfunction "1_1") (pintype "passive"))
      (node (ref "C81") (pin "1") (pinfunction "1_1") (pintype "passive"))
      (node (ref "C82") (pin "1") (pinfunction "1_1") (pintype "passive"))
      (node (ref "C83") (pin "1") (pinfunction "1_1") (pintype "passive"))
      (node (ref "C84") (pin "1") (pinfunction "1_1") (pintype "passive"))
      (node (ref "C85") (pin "1") (pinfunction "1_1") (pintype "passive"))
      (node (ref "C86") (pin "1") (pinfunction "1_1") (pintype "passive"))
      (node (ref "C87") (pin "1") (pinfunction "1_1") (pintype "passive"))
      (node (ref "C88") (pin "2") (pinfunction "2_2") (pintype "passive"))
      (node (ref "C89") (pin "2") (pinfunction "2_2") (pintype "passive"))
      (node (ref "C90") (pin "2") (pinfunction "2_2") (pintype "passive"))
      (node (ref "C91") (pin "2") (pinfunction "2_2") (pintype "passive"))
      (node (ref "C96") (pin "1") (pinfunction "1_1") (pintype "passive"))
      (node (ref "C97") (pin "1") (pinfunction "1_1") (pintype "passive"))
      (node (ref "C98") (pin "1") (pinfunction "1_1") (pintype "passive"))
      (node (ref "C99") (pin "1") (pinfunction "1_1") (pintype "passive"))
      (node (ref "Q10") (pin "1") (pinfunction "S_1") (pintype "passive"))
      (node (ref "Q10") (pin "2") (pinfunction "S_2") (pintype "passive"))
      (node (ref "Q10") (pin "3") (pinfunction "S_3") (pintype "passive"))
      (node (ref "Q11") (pin "1") (pinfunction "S_1") (pintype "passive"))
      (node (ref "Q11") (pin "2") (pinfunction "S_2") (pintype "passive"))
      (node (ref "Q11") (pin "3") (pinfunction "S_3") (pintype "passive"))
      (node (ref "Q12") (pin "1") (pinfunction "S_1") (pintype "passive"))
      (node (ref "Q12") (pin "2") (pinfunction "S_2") (pintype "passive"))
      (node (ref "Q12") (pin "3") (pinfunction "S_3") (pintype "passive"))
      (node (ref "Q17") (pin "1") (pinfunction "S_1") (pintype "passive"))
      (node (ref "Q17") (pin "2") (pinfunction "S_2") (pintype "passive"))
      (node (ref "Q17") (pin "3") (pinfunction "S_3") (pintype "passive"))
      (node (ref "Q18") (pin "1") (pinfunction "S_1") (pintype "passive"))
      (node (ref "Q18") (pin "2") (pinfunction "S_2") (pintype "passive"))
      (node (ref "Q18") (pin "3") (pinfunction "S_3") (pintype "passive"))
      (node (ref "Q19") (pin "1") (pinfunction "S_1") (pintype "passive"))
      (node (ref "Q19") (pin "2") (pinfunction "S_2") (pintype "passive"))
      (node (ref "Q19") (pin "3") (pinfunction "S_3") (pintype "passive"))
      (node (ref "Q20") (pin "1") (pinfunction "S_1") (pintype "passive"))
      (node (ref "Q20") (pin "2") (pinfunction "S_2") (pintype "passive"))
      (node (ref "Q20") (pin "3") (pinfunction "S_3") (pintype "passive"))
      (node (ref "Q21") (pin "1") (pinfunction "S_1") (pintype "passive"))
      (node (ref "Q21") (pin "2") (pinfunction "S_2") (pintype "passive"))
      (node (ref "Q21") (pin "3") (pinfunction "S_3") (pintype "passive"))
      (node (ref "Q22") (pin "1") (pinfunction "S_1") (pintype "passive"))
      (node (ref "Q22") (pin "2") (pinfunction "S_2") (pintype "passive"))
      (node (ref "Q22") (pin "3") (pinfunction "S_3") (pintype "passive"))
      (node (ref "Q23") (pin "1") (pinfunction "S_1") (pintype "passive"))
      (node (ref "Q23") (pin "2") (pinfunction "S_2") (pintype "passive"))
      (node (ref "Q23") (pin "3") (pinfunction "S_3") (pintype "passive"))
      (node (ref "Q24") (pin "1") (pinfunction "S_1") (pintype "passive"))
      (node (ref "Q24") (pin "2") (pinfunction "S_2") (pintype "passive"))
      (node (ref "Q24") (pin "3") (pinfunction "S_3") (pintype "passive"))
      (node (ref "Q29") (pin "1") (pinfunction "S_1") (pintype "passive"))
      (node (ref "Q29") (pin "2") (pinfunction "S_2") (pintype "passive"))
      (node (ref "Q29") (pin "3") (pinfunction "S_3") (pintype "passive"))
      (node (ref "Q30") (pin "1") (pinfunction "S_1") (pintype "passive"))
      (node (ref "Q30") (pin "2") (pinfunction "S_2") (pintype "passive"))
      (node (ref "Q30") (pin "3") (pinfunction "S_3") (pintype "passive"))
      (node (ref "Q31") (pin "1") (pinfunction "S_1") (pintype "passive"))
      (node (ref "Q31") (pin "2") (pinfunction "S_2") (pintype "passive"))
      (node (ref "Q31") (pin "3") (pinfunction "S_3") (pintype "passive"))
      (node (ref "Q32") (pin "1") (pinfunction "S_1") (pintype "passive"))
      (node (ref "Q32") (pin "2") (pinfunction "S_2") (pintype "passive"))
      (node (ref "Q32") (pin "3") (pinfunction "S_3") (pintype "passive"))
      (node (ref "Q33") (pin "1") (pinfunction "S_1") (pintype "passive"))
      (node (ref "Q33") (pin "2") (pinfunction "S_2") (pintype "passive"))
      (node (ref "Q33") (pin "3") (pinfunction "S_3") (pintype "passive"))
      (node (ref "Q34") (pin "1") (pinfunction "S_1") (pintype "passive"))
      (node (ref "Q34") (pin "2") (pinfunction "S_2") (pintype "passive"))
      (node (ref "Q34") (pin "3") (pinfunction "S_3") (pintype "passive"))
      (node (ref "Q35") (pin "1") (pinfunction "S_1") (pintype "passive"))
      (node (ref "Q35") (pin "2") (pinfunction "S_2") (pintype "passive"))
      (node (ref "Q35") (pin "3") (pinfunction "S_3") (pintype "passive"))
      (node (ref "Q36") (pin "1") (pinfunction "S_1") (pintype "passive"))
      (node (ref "Q36") (pin "2") (pinfunction "S_2") (pintype "passive"))
      (node (ref "Q36") (pin "3") (pinfunction "S_3") (pintype "passive"))
      (node (ref "Q41") (pin "1") (pinfunction "S_1") (pintype "passive"))
      (node (ref "Q41") (pin "2") (pinfunction "S_2") (pintype "passive"))
      (node (ref "Q41") (pin "3") (pinfunction "S_3") (pintype "passive"))
      (node (ref "Q42") (pin "1") (pinfunction "S_1") (pintype "passive"))
      (node (ref "Q42") (pin "2") (pinfunction "S_2") (pintype "passive"))
      (node (ref "Q42") (pin "3") (pinfunction "S_3") (pintype "passive"))
      (node (ref "Q43") (pin "1") (pinfunction "S_1") (pintype "passive"))
      (node (ref "Q43") (pin "2") (pinfunction "S_2") (pintype "passive"))
      (node (ref "Q43") (pin "3") (pinfunction "S_3") (pintype "passive"))
      (node (ref "Q44") (pin "1") (pinfunction "S_1") (pintype "passive"))
      (node (ref "Q44") (pin "2") (pinfunction "S_2") (pintype "passive"))
      (node (ref "Q44") (pin "3") (pinfunction "S_3") (pintype "passive"))
      (node (ref "Q45") (pin "1") (pinfunction "S_1") (pintype "passive"))
      (node (ref "Q45") (pin "2") (pinfunction "S_2") (pintype "passive"))
      (node (ref "Q45") (pin "3") (pinfunction "S_3") (pintype "passive"))
      (node (ref "Q46") (pin "1") (pinfunction "S_1") (pintype "passive"))
      (node (ref "Q46") (pin "2") (pinfunction "S_2") (pintype "passive"))
      (node (ref "Q46") (pin "3") (pinfunction "S_3") (pintype "passive"))
      (node (ref "Q47") (pin "1") (pinfunction "S_1") (pintype "passive"))
      (node (ref "Q47") (pin "2") (pinfunction "S_2") (pintype "passive"))
      (node (ref "Q47") (pin "3") (pinfunction "S_3") (pintype "passive"))
      (node (ref "Q48") (pin "1") (pinfunction "S_1") (pintype "passive"))
      (node (ref "Q48") (pin "2") (pinfunction "S_2") (pintype "passive"))
      (node (ref "Q48") (pin "3") (pinfunction "S_3") (pintype "passive"))
      (node (ref "Q5") (pin "1") (pinfunction "S_1") (pintype "passive"))
      (node (ref "Q5") (pin "2") (pinfunction "S_2") (pintype "passive"))
      (node (ref "Q5") (pin "3") (pinfunction "S_3") (pintype "passive"))
      (node (ref "Q6") (pin "1") (pinfunction "S_1") (pintype "passive"))
      (node (ref "Q6") (pin "2") (pinfunction "S_2") (pintype "passive"))
      (node (ref "Q6") (pin "3") (pinfunction "S_3") (pintype "passive"))
      (node (ref "Q7") (pin "1") (pinfunction "S_1") (pintype "passive"))
      (node (ref "Q7") (pin "2") (pinfunction "S_2") (pintype "passive"))
      (node (ref "Q7") (pin "3") (pinfunction "S_3") (pintype "passive"))
      (node (ref "Q8") (pin "1") (pinfunction "S_1") (pintype "passive"))
      (node (ref "Q8") (pin "2") (pinfunction "S_2") (pintype "passive"))
      (node (ref "Q8") (pin "3") (pinfunction "S_3") (pintype "passive"))
      (node (ref "Q9") (pin "1") (pinfunction "S_1") (pintype "passive"))
      (node (ref "Q9") (pin "2") (pinfunction "S_2") (pintype "passive"))
      (node (ref "Q9") (pin "3") (pinfunction "S_3") (pintype "passive"))
      (node (ref "U11") (pin "4") (pinfunction "GND_4") (pintype "passive"))
      (node (ref "U11") (pin "9") (pinfunction "EP_9") (pintype "passive"))
      (node (ref "U12") (pin "4") (pinfunction "GND_4") (pintype "passive"))
      (node (ref "U12") (pin "9") (pinfunction "EP_9") (pintype "passive"))
      (node (ref "U13") (pin "4") (pinfunction "GND_4") (pintype "passive"))
      (node (ref "U13") (pin "9") (pinfunction "EP_9") (pintype "passive"))
      (node (ref "U14") (pin "4") (pinfunction "GND_4") (pintype "passive"))
      (node (ref "U14") (pin "9") (pinfunction "EP_9") (pintype "passive"))
      (node (ref "U15") (pin "4") (pinfunction "GND_4") (pintype "passive"))
      (node (ref "U15") (pin "9") (pinfunction "EP_9") (pintype "passive"))
      (node (ref "U16") (pin "4") (pinfunction "GND_4") (pintype "passive"))
      (node (ref "U16") (pin "9") (pinfunction "EP_9") (pintype "passive"))
      (node (ref "U17") (pin "4") (pinfunction "GND_4") (pintype "passive"))
      (node (ref "U17") (pin "9") (pinfunction "EP_9") (pintype "passive"))
      (node (ref "U18") (pin "4") (pinfunction "GND_4") (pintype "passive"))
      (node (ref "U18") (pin "9") (pinfunction "EP_9") (pintype "passive"))
      (node (ref "U19") (pin "4") (pinfunction "GND_4") (pintype "passive"))
      (node (ref "U19") (pin "9") (pinfunction "EP_9") (pintype "passive"))
      (node (ref "U20") (pin "4") (pinfunction "GND_4") (pintype "passive"))
      (node (ref "U20") (pin "9") (pinfunction "EP_9") (pintype "passive"))
      (node (ref "U21") (pin "4") (pinfunction "GND_4") (pintype "passive"))
      (node (ref "U21") (pin "9") (pinfunction "EP_9") (pintype "passive"))
      (node (ref "U22") (pin "4") (pinfunction "GND_4") (pintype "passive"))
      (node (ref "U22") (pin "9") (pinfunction "EP_9") (pintype "passive"))
      (node (ref "U23") (pin "4") (pinfunction "GND_4") (pintype "passive"))
      (node (ref "U23") (pin "9") (pinfunction "EP_9") (pintype "passive"))
      (node (ref "U24") (pin "4") (pinfunction "GND_4") (pintype "passive"))
      (node (ref "U24") (pin "9") (pinfunction "EP_9") (pintype "passive"))
      (node (ref "U25") (pin "4") (pinfunction "GND_4") (pintype "passive"))
      (node (ref "U25") (pin "9") (pinfunction "EP_9") (pintype "passive"))
      (node (ref "U26") (pin "4") (pinfunction "GND_4") (pintype "passive"))
      (node (ref "U26") (pin "9") (pinfunction "EP_9") (pintype "passive"))
    )
  )
)
